# bfc.net
KiCad netlist of a schematic drawn in EAGLE
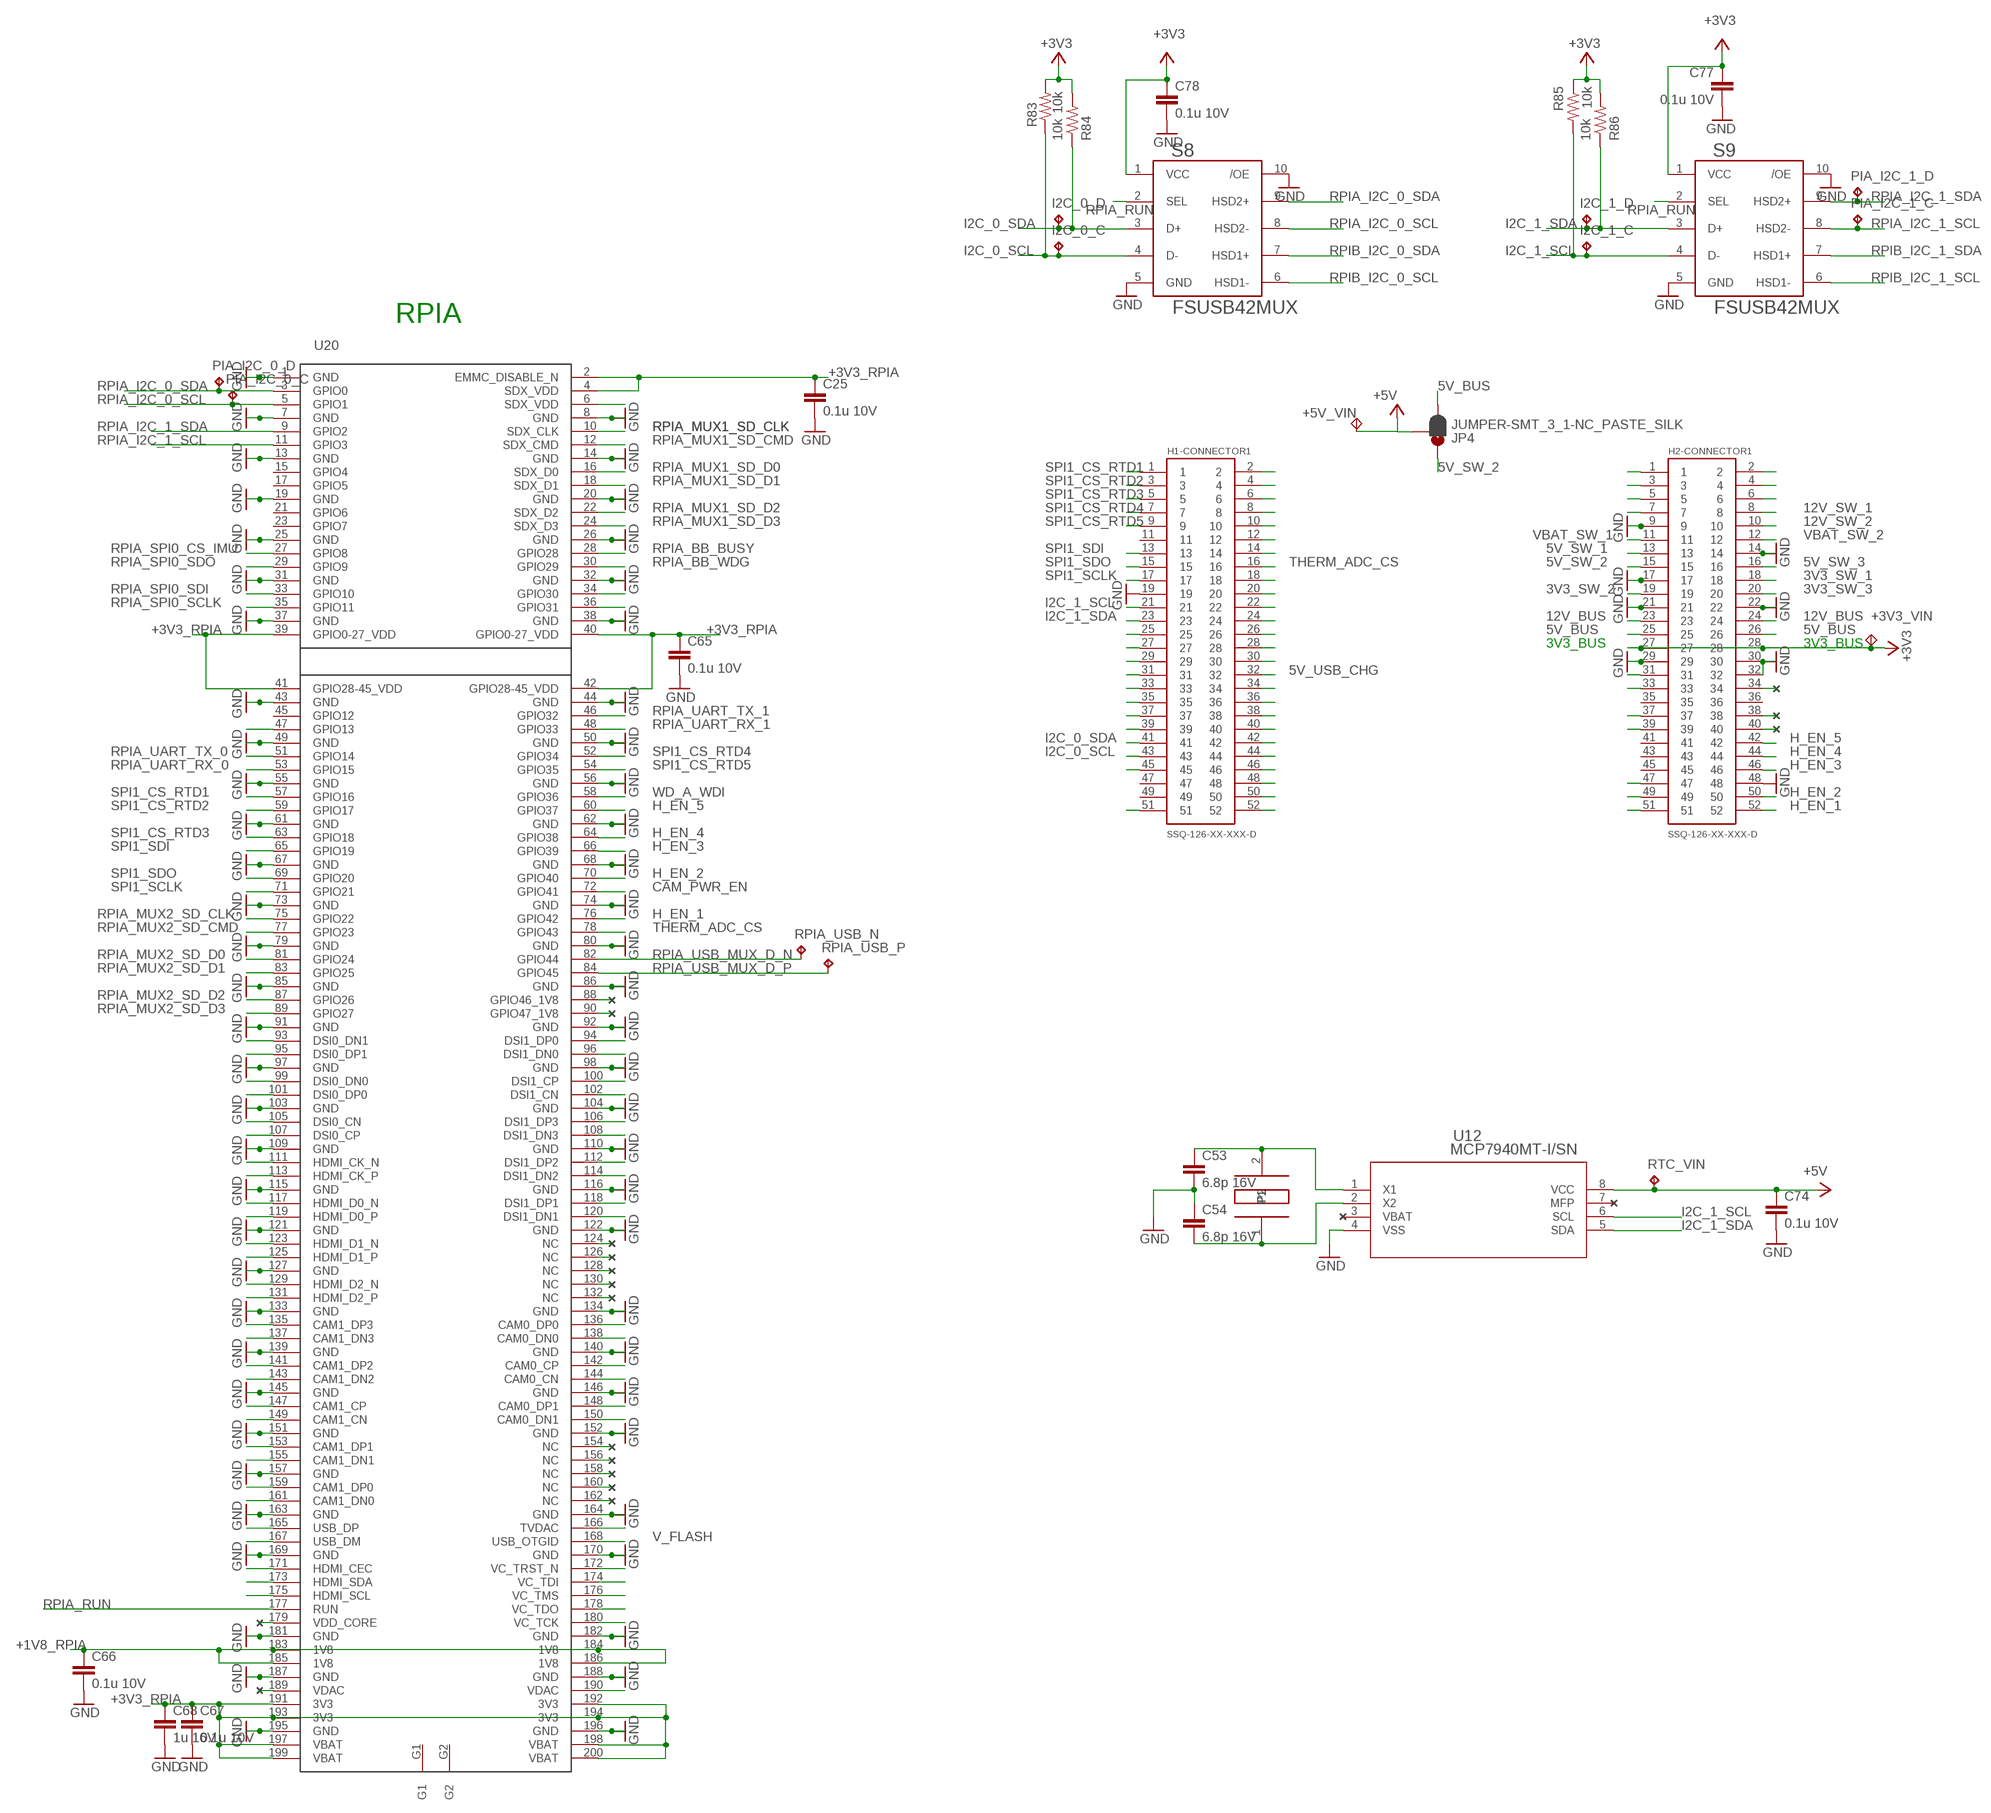
[diagram p0: schematic, sheet 1, part 1 of 2]
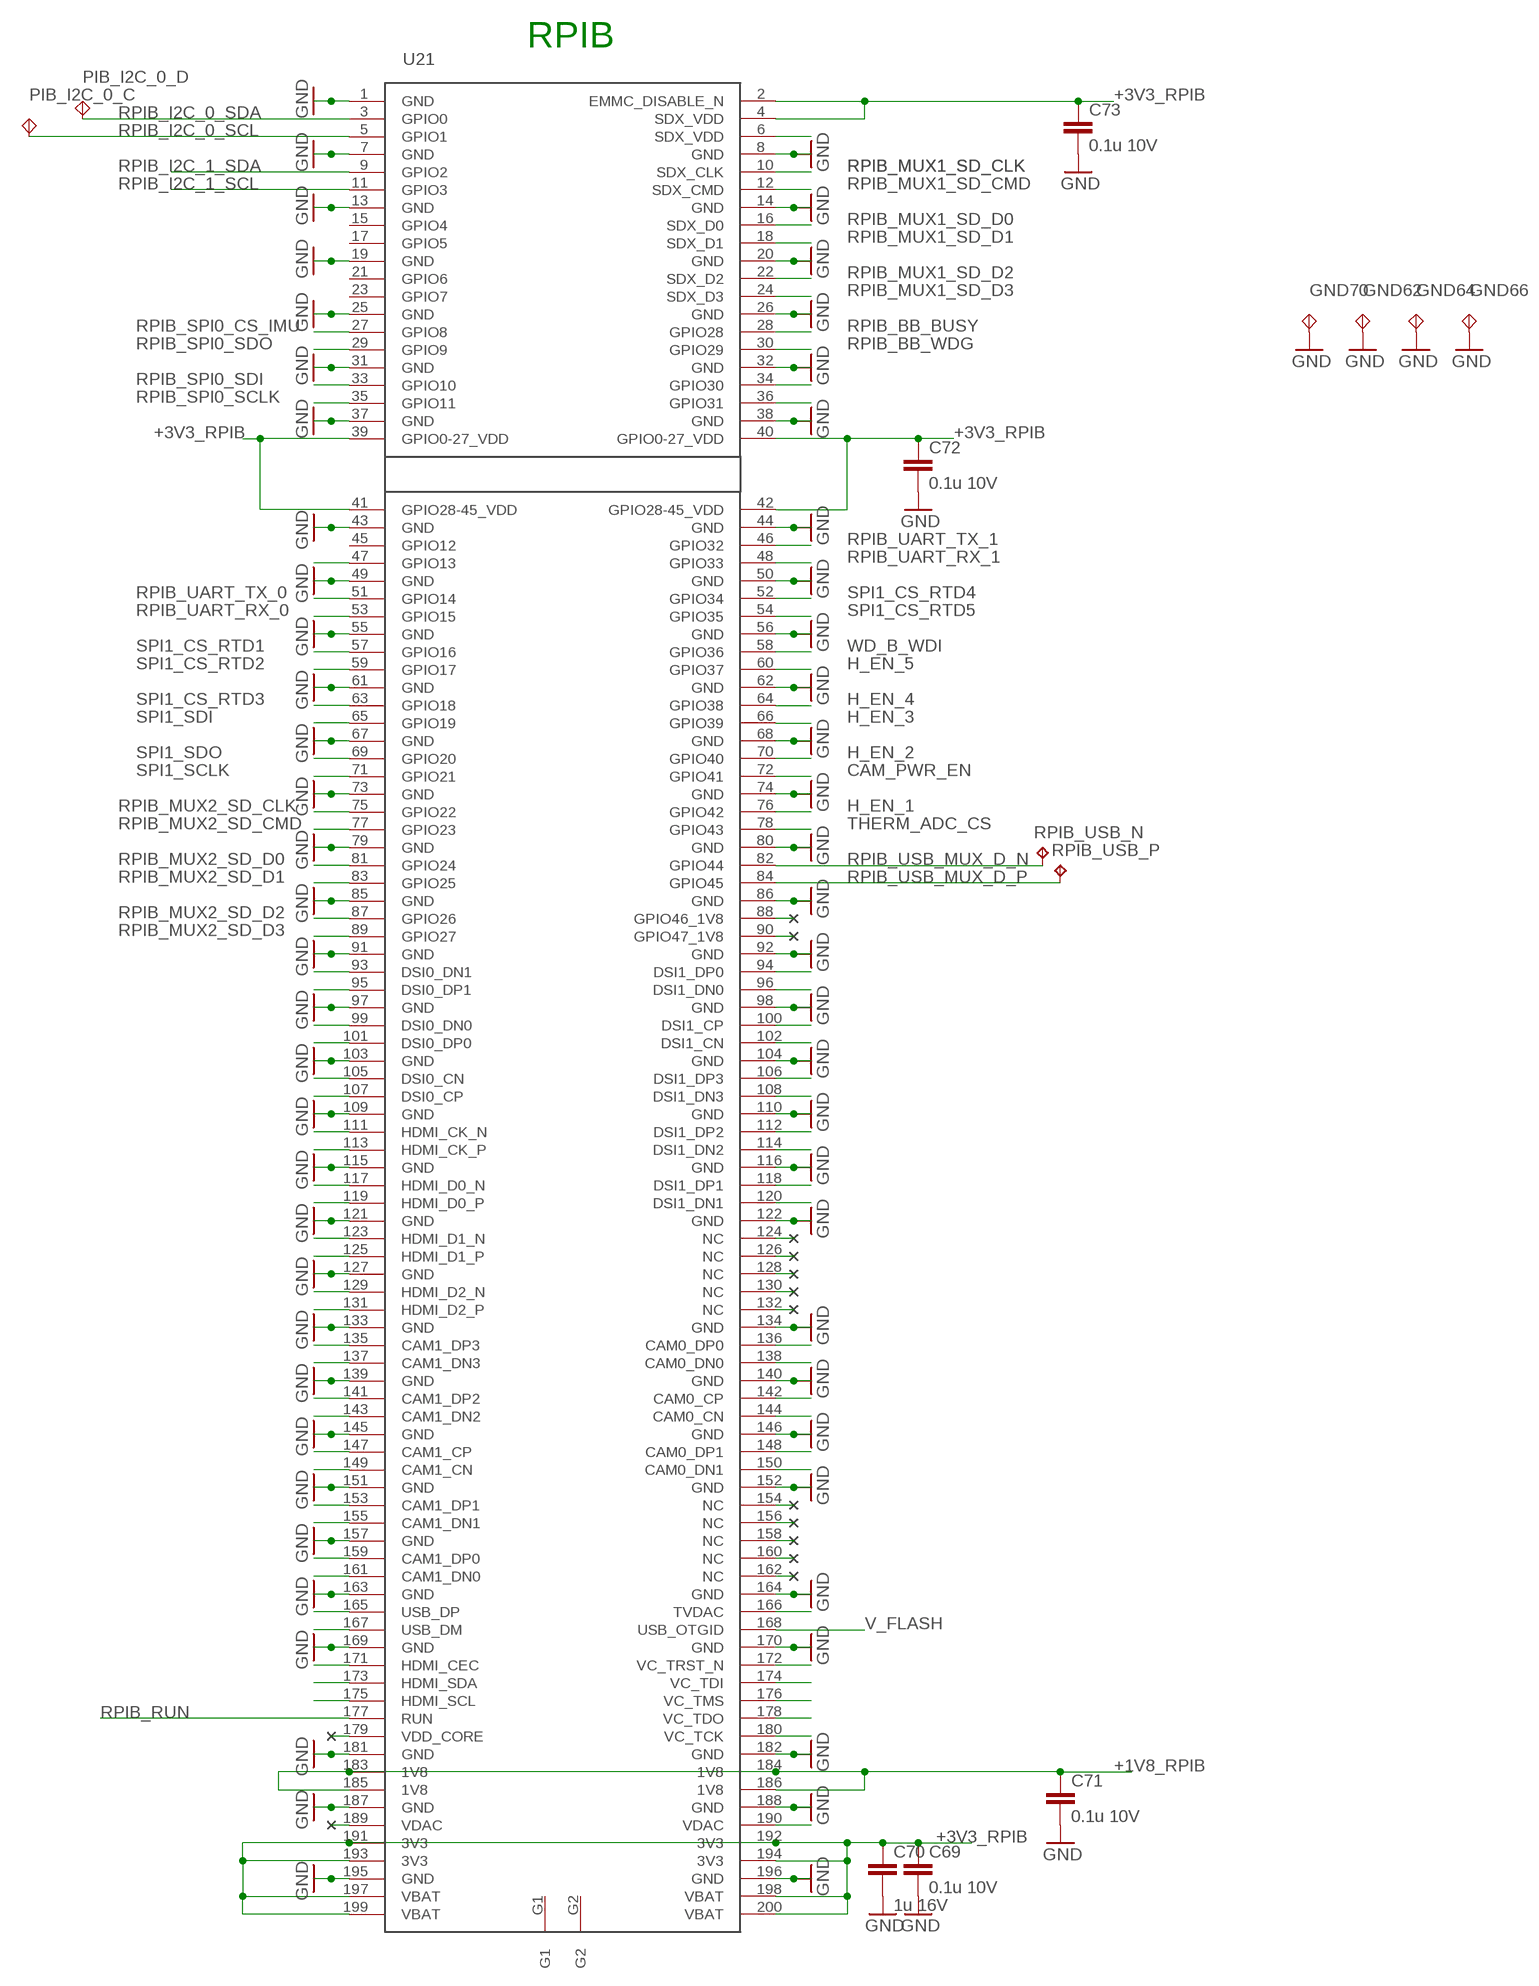
[diagram p1: schematic, sheet 1, part 2 of 2]
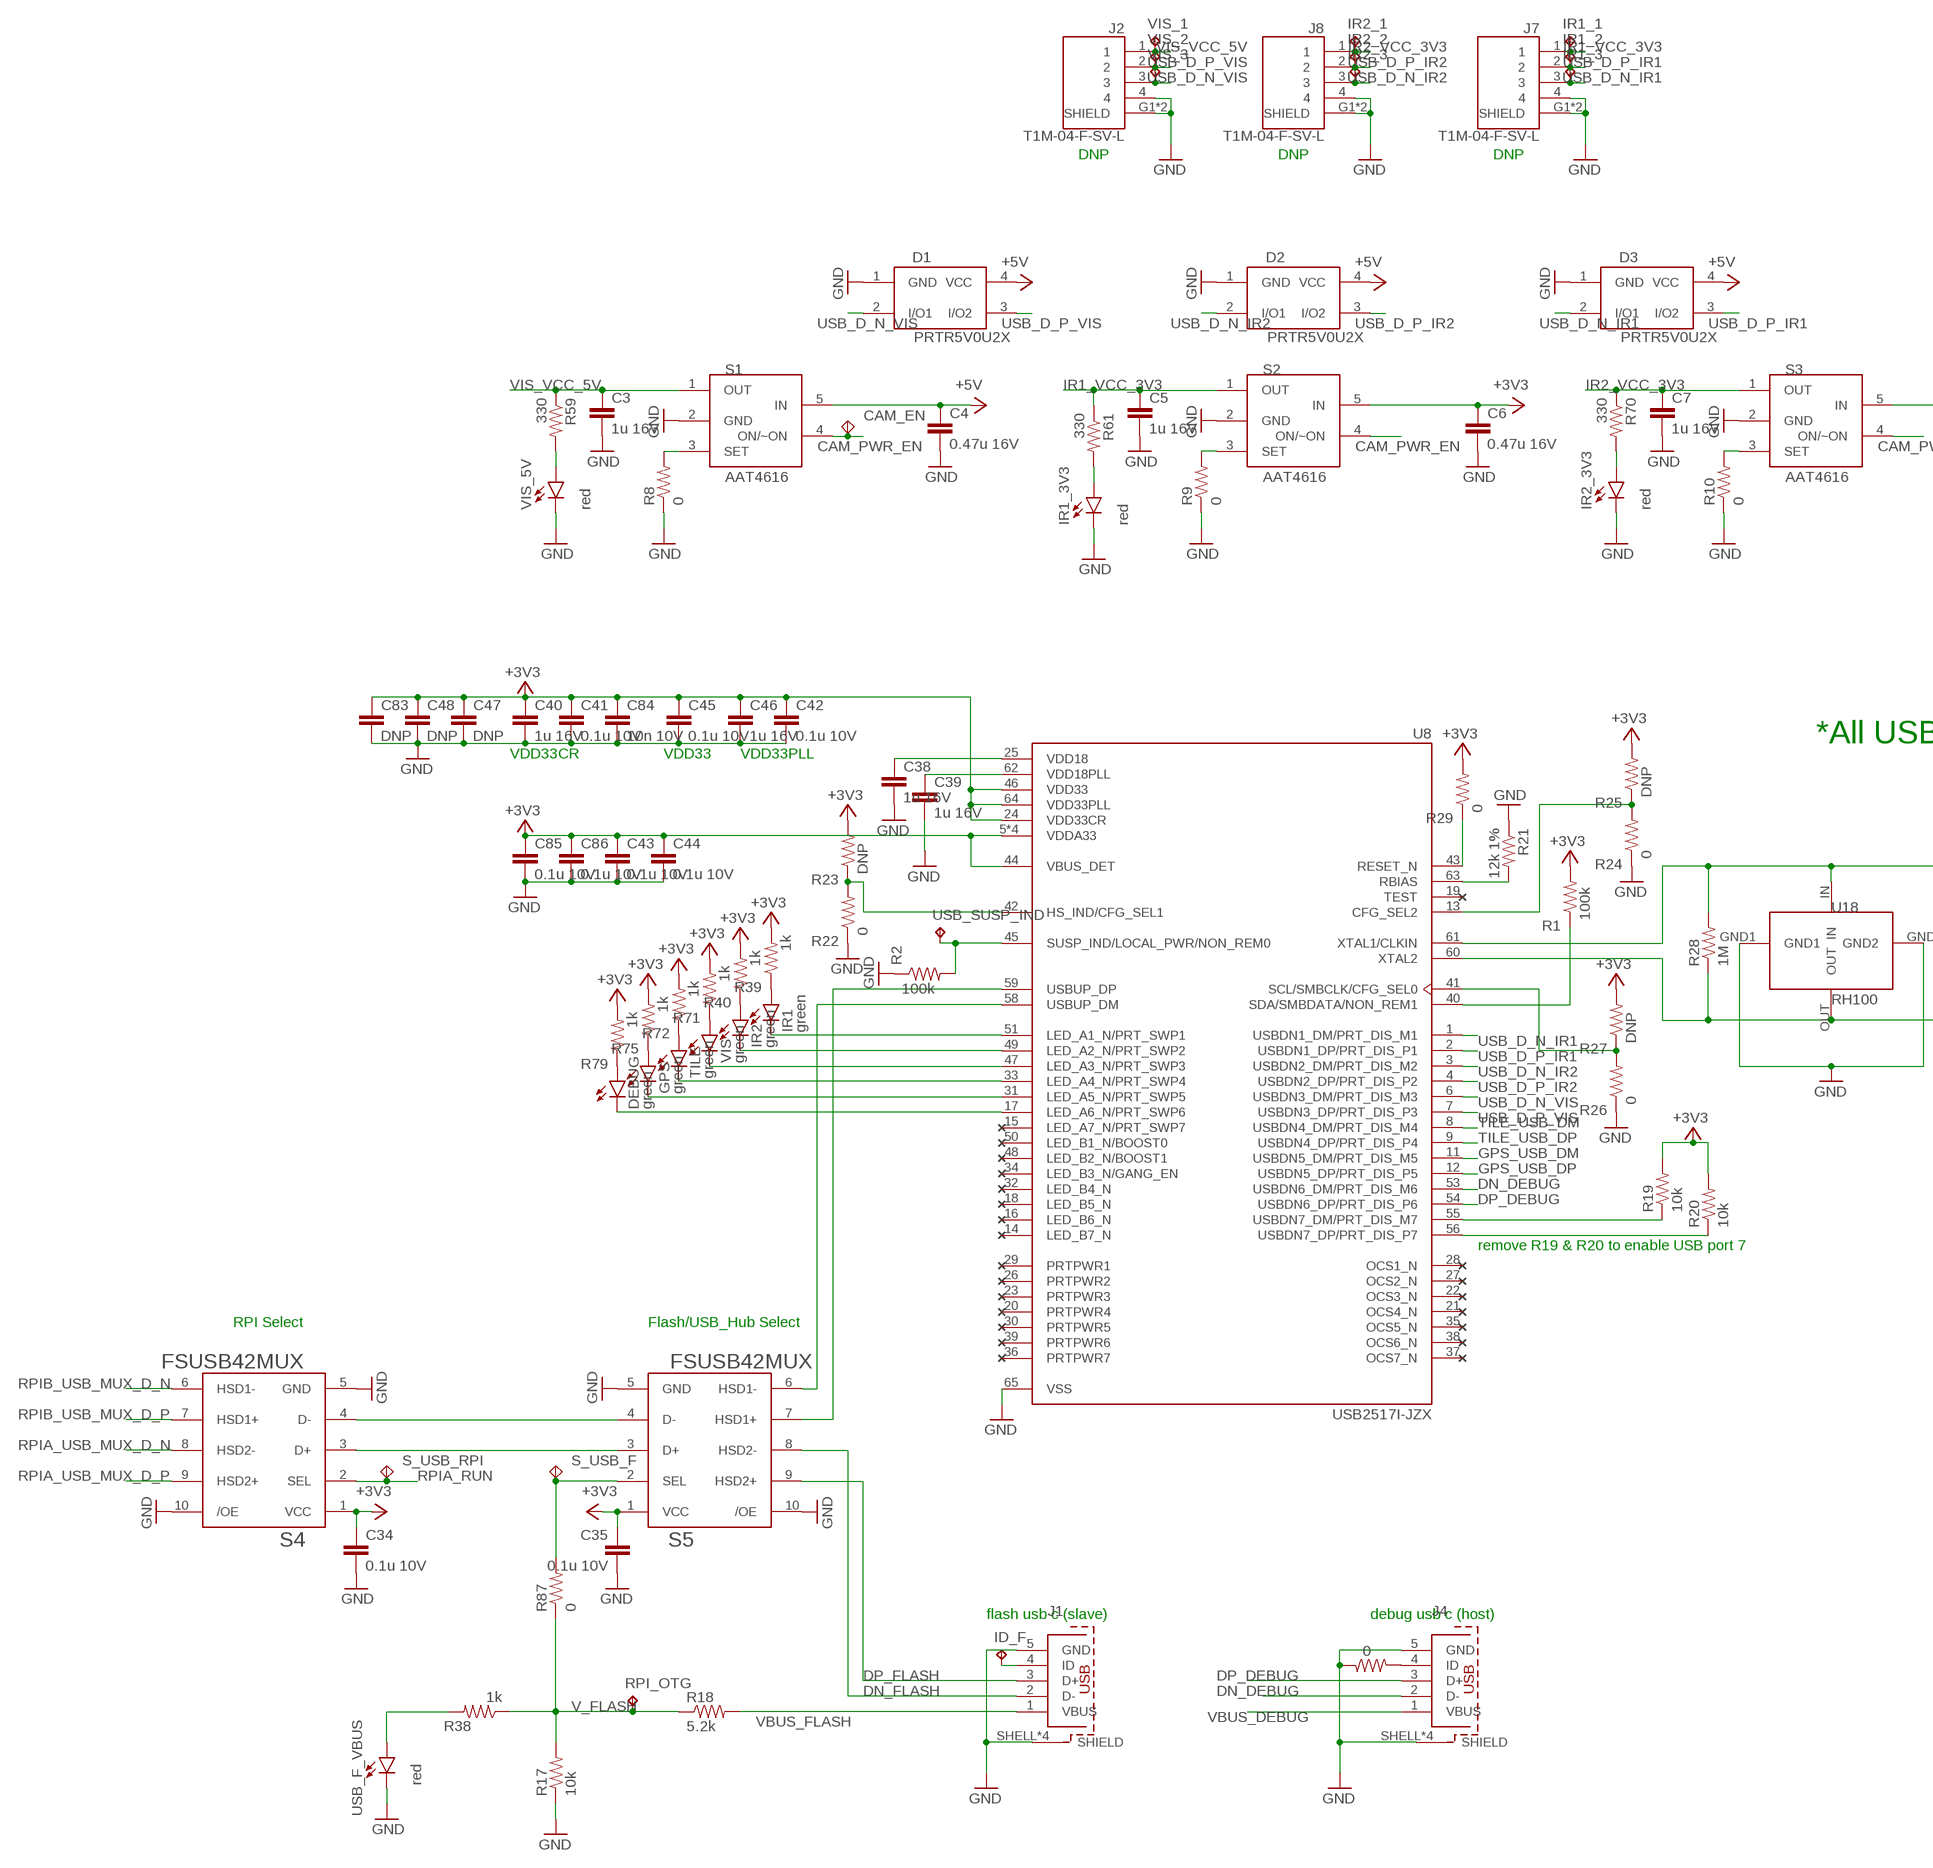
[diagram p2: schematic, sheet 2, part 1 of 2]
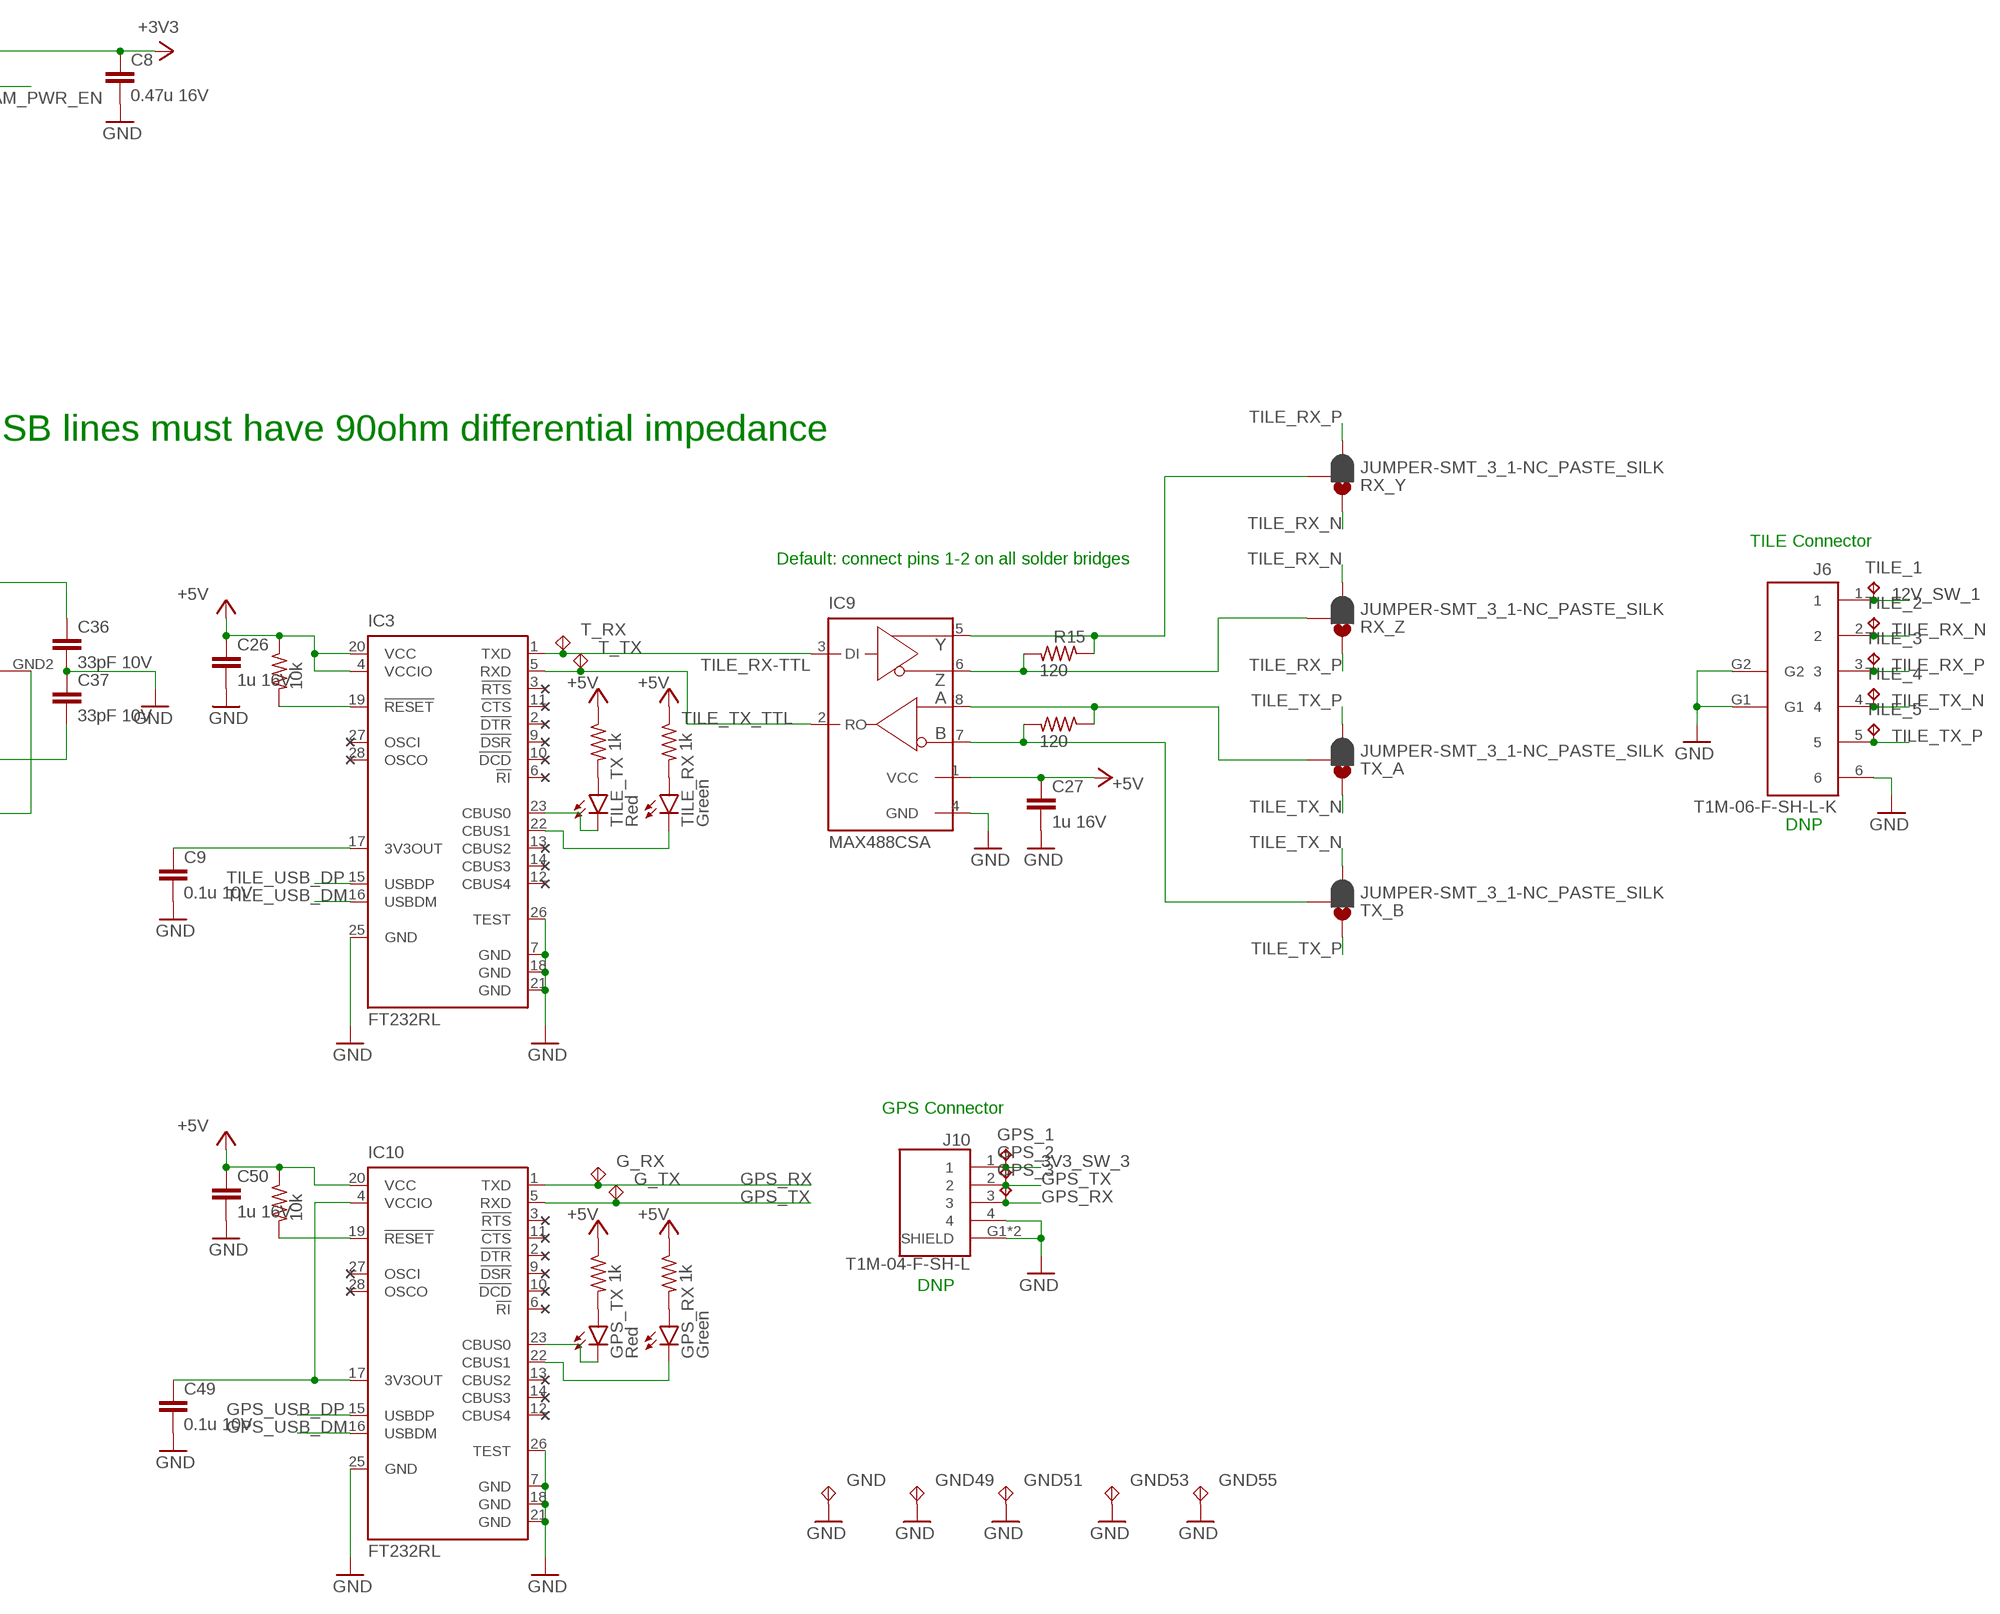
[diagram p3: schematic, sheet 2, part 2 of 2]
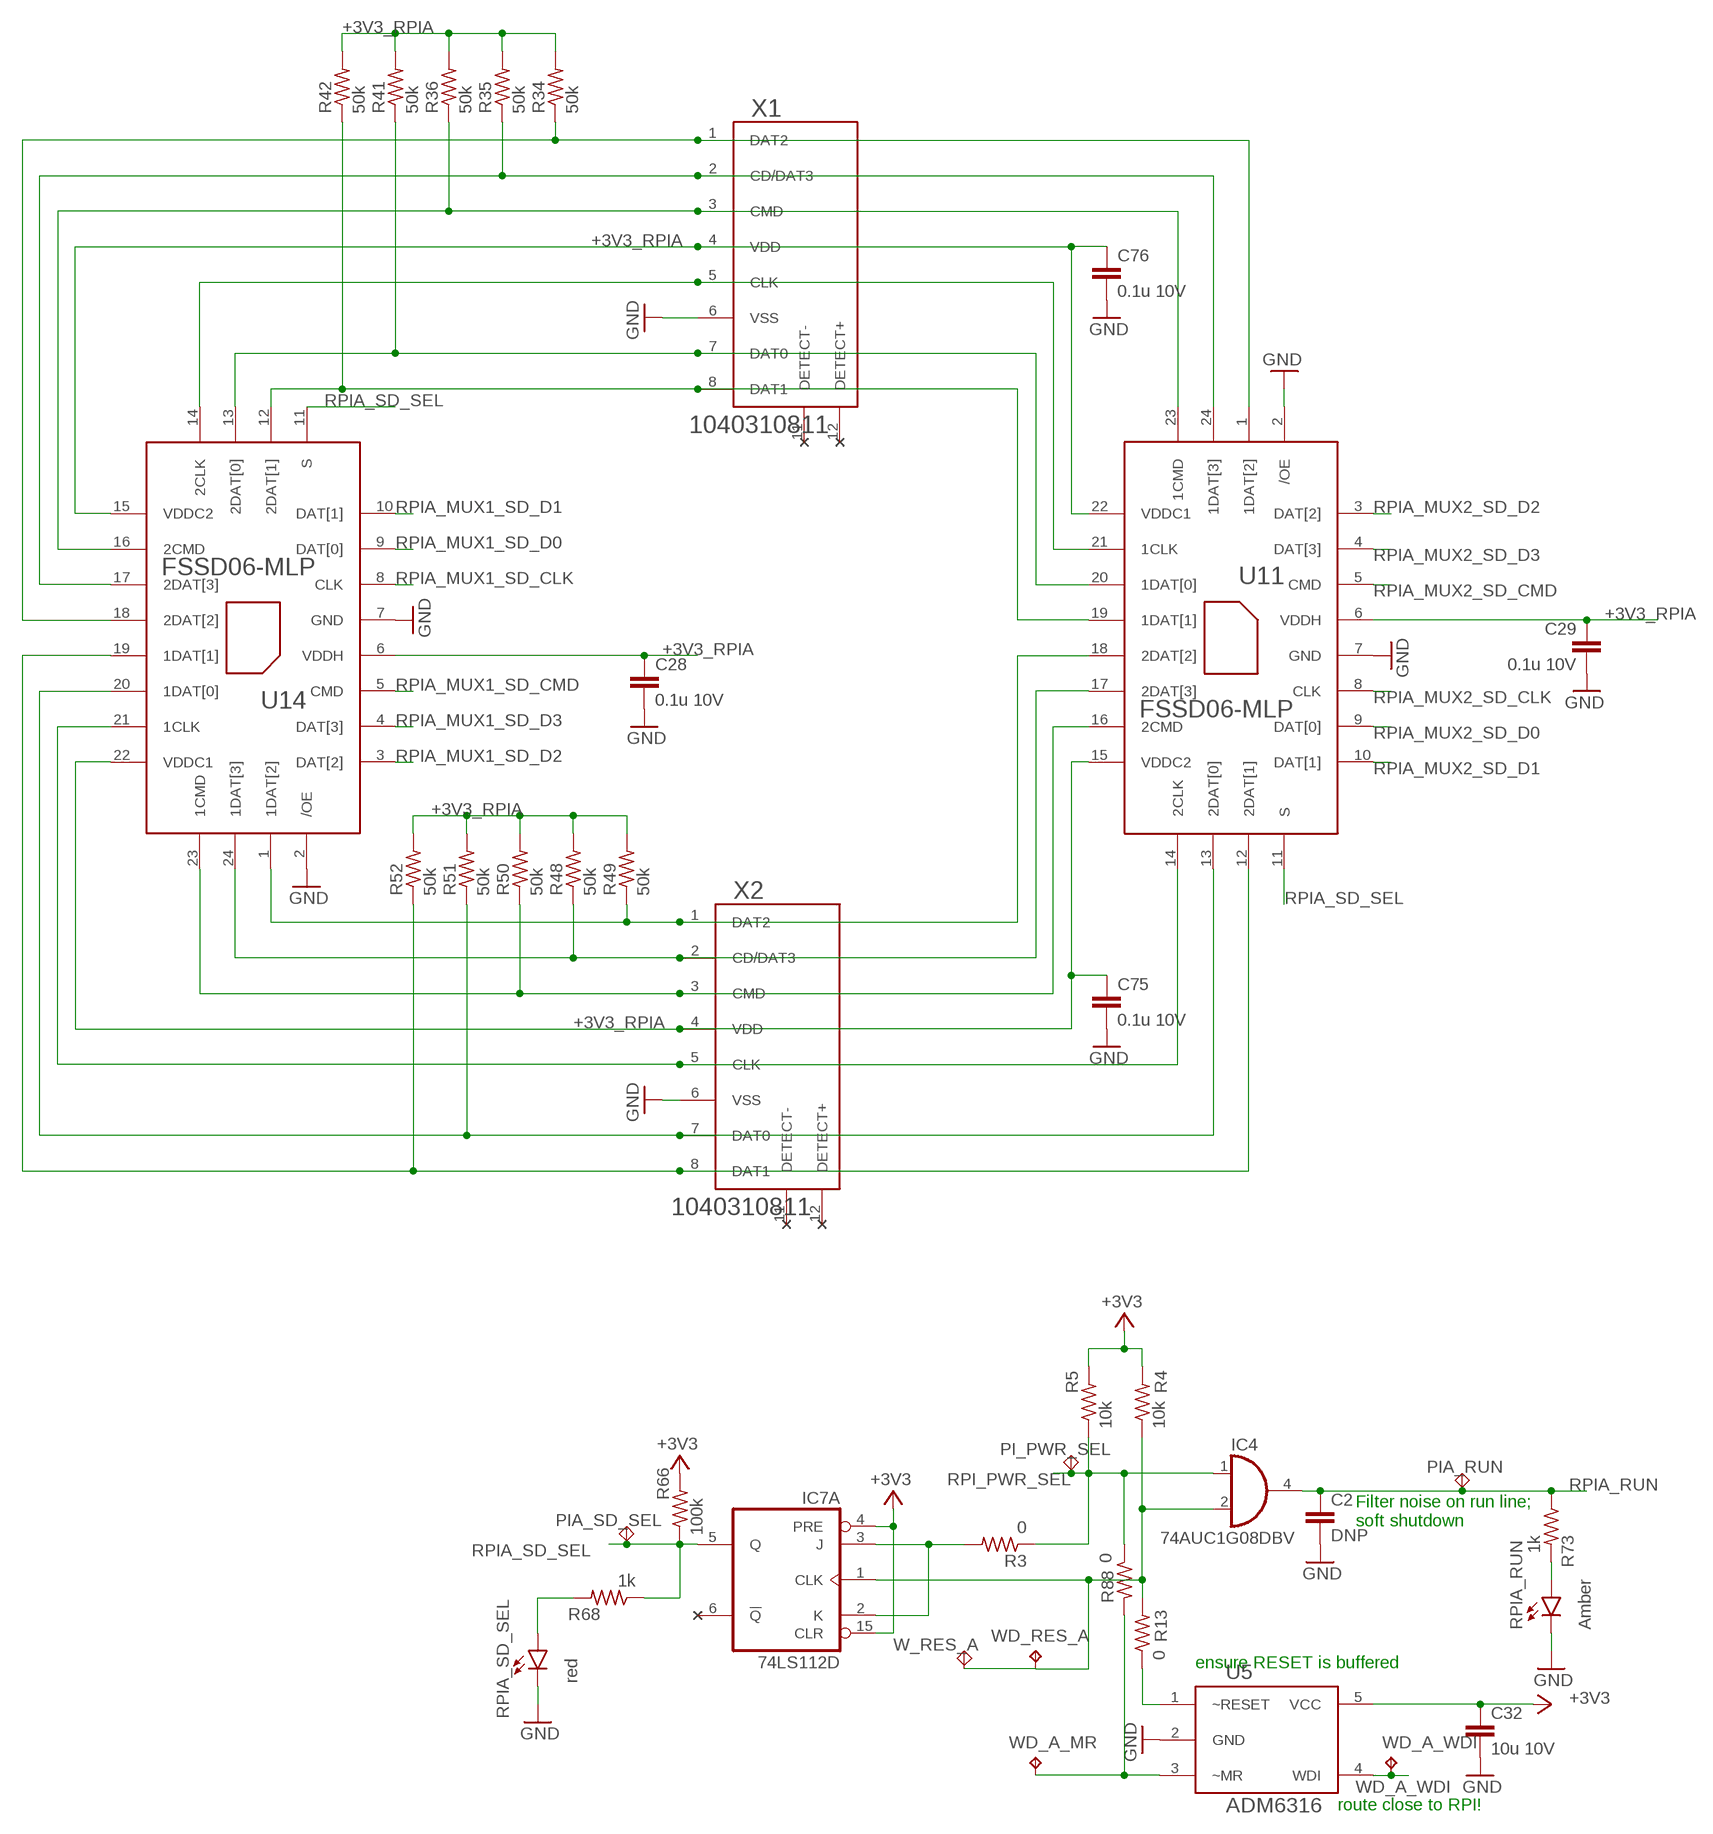
[diagram p4: schematic, sheet 3, part 1 of 2]
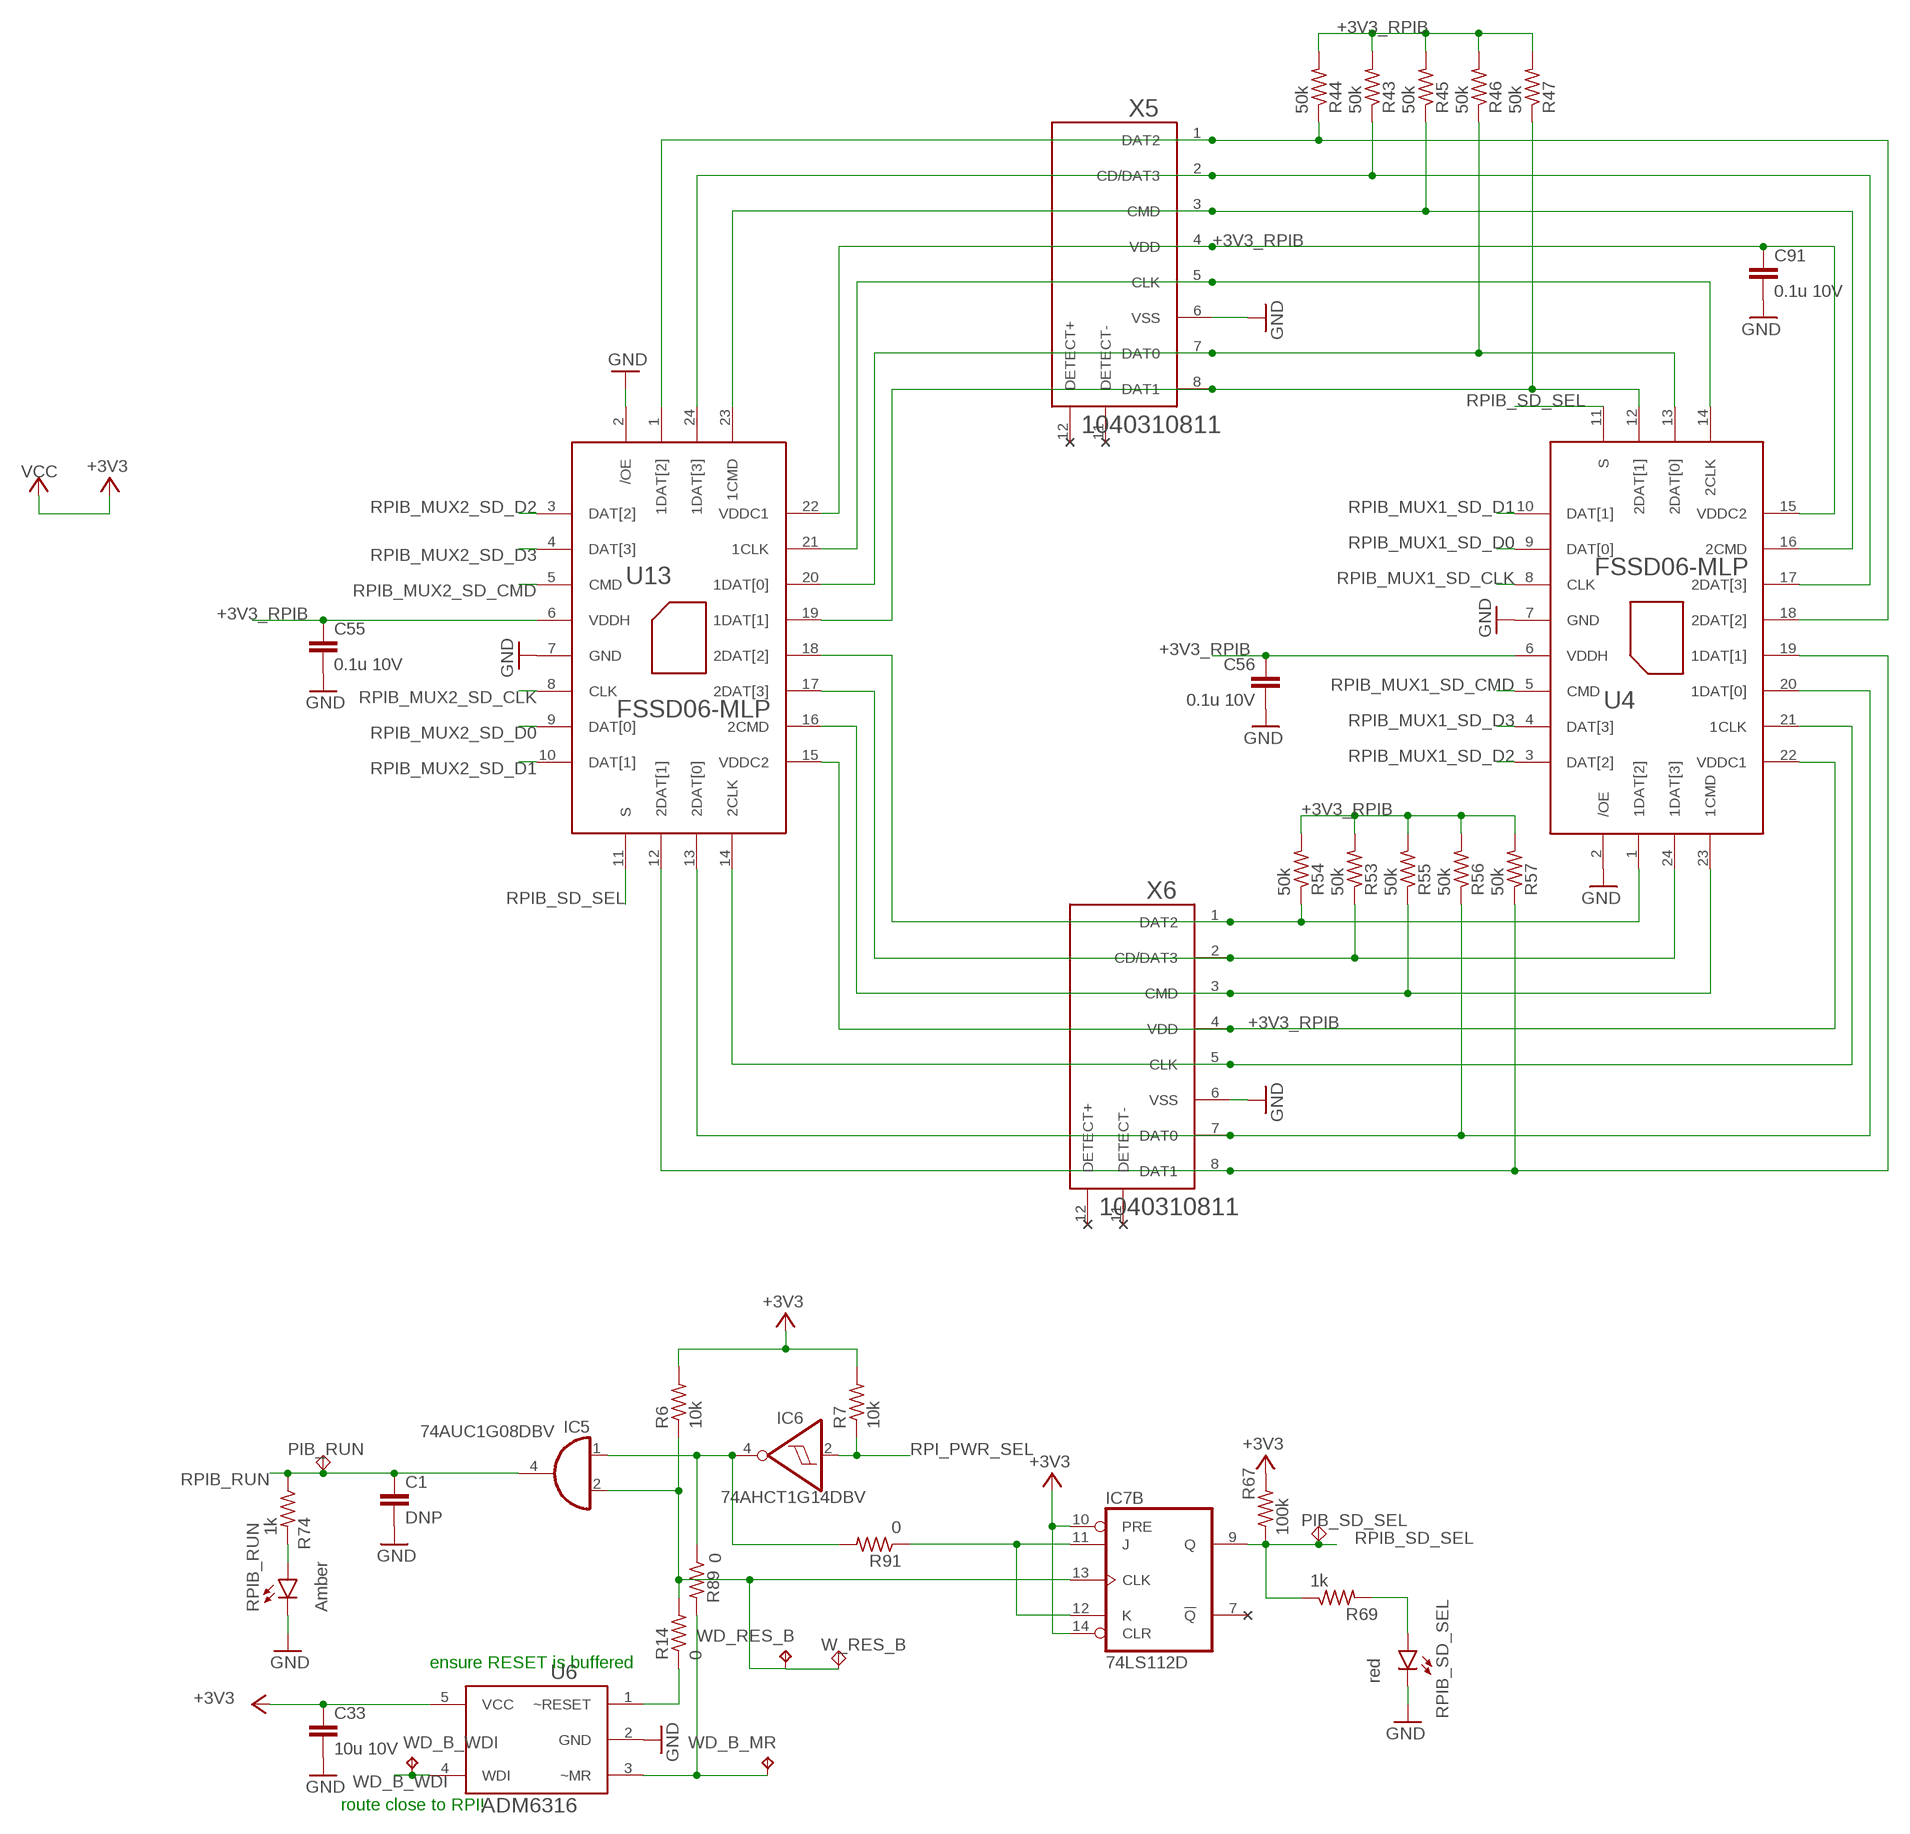
[diagram p5: schematic, sheet 3, part 2 of 2]
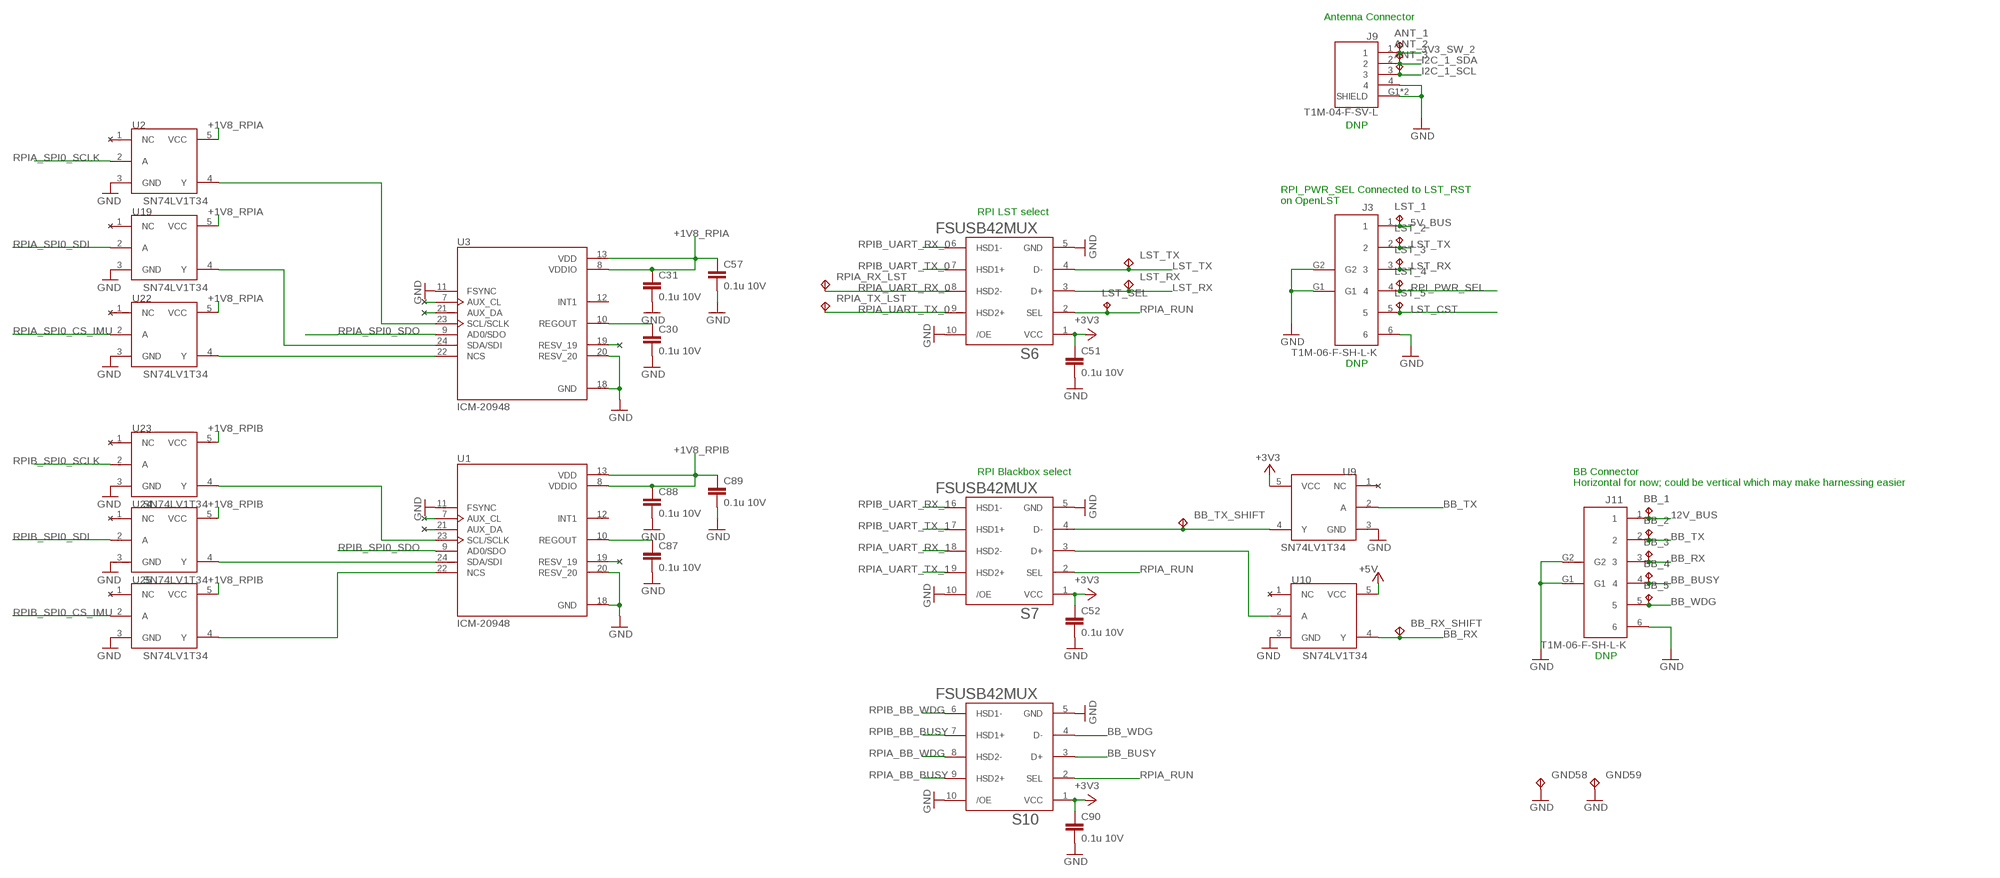
[diagram p6: schematic, sheet 4]
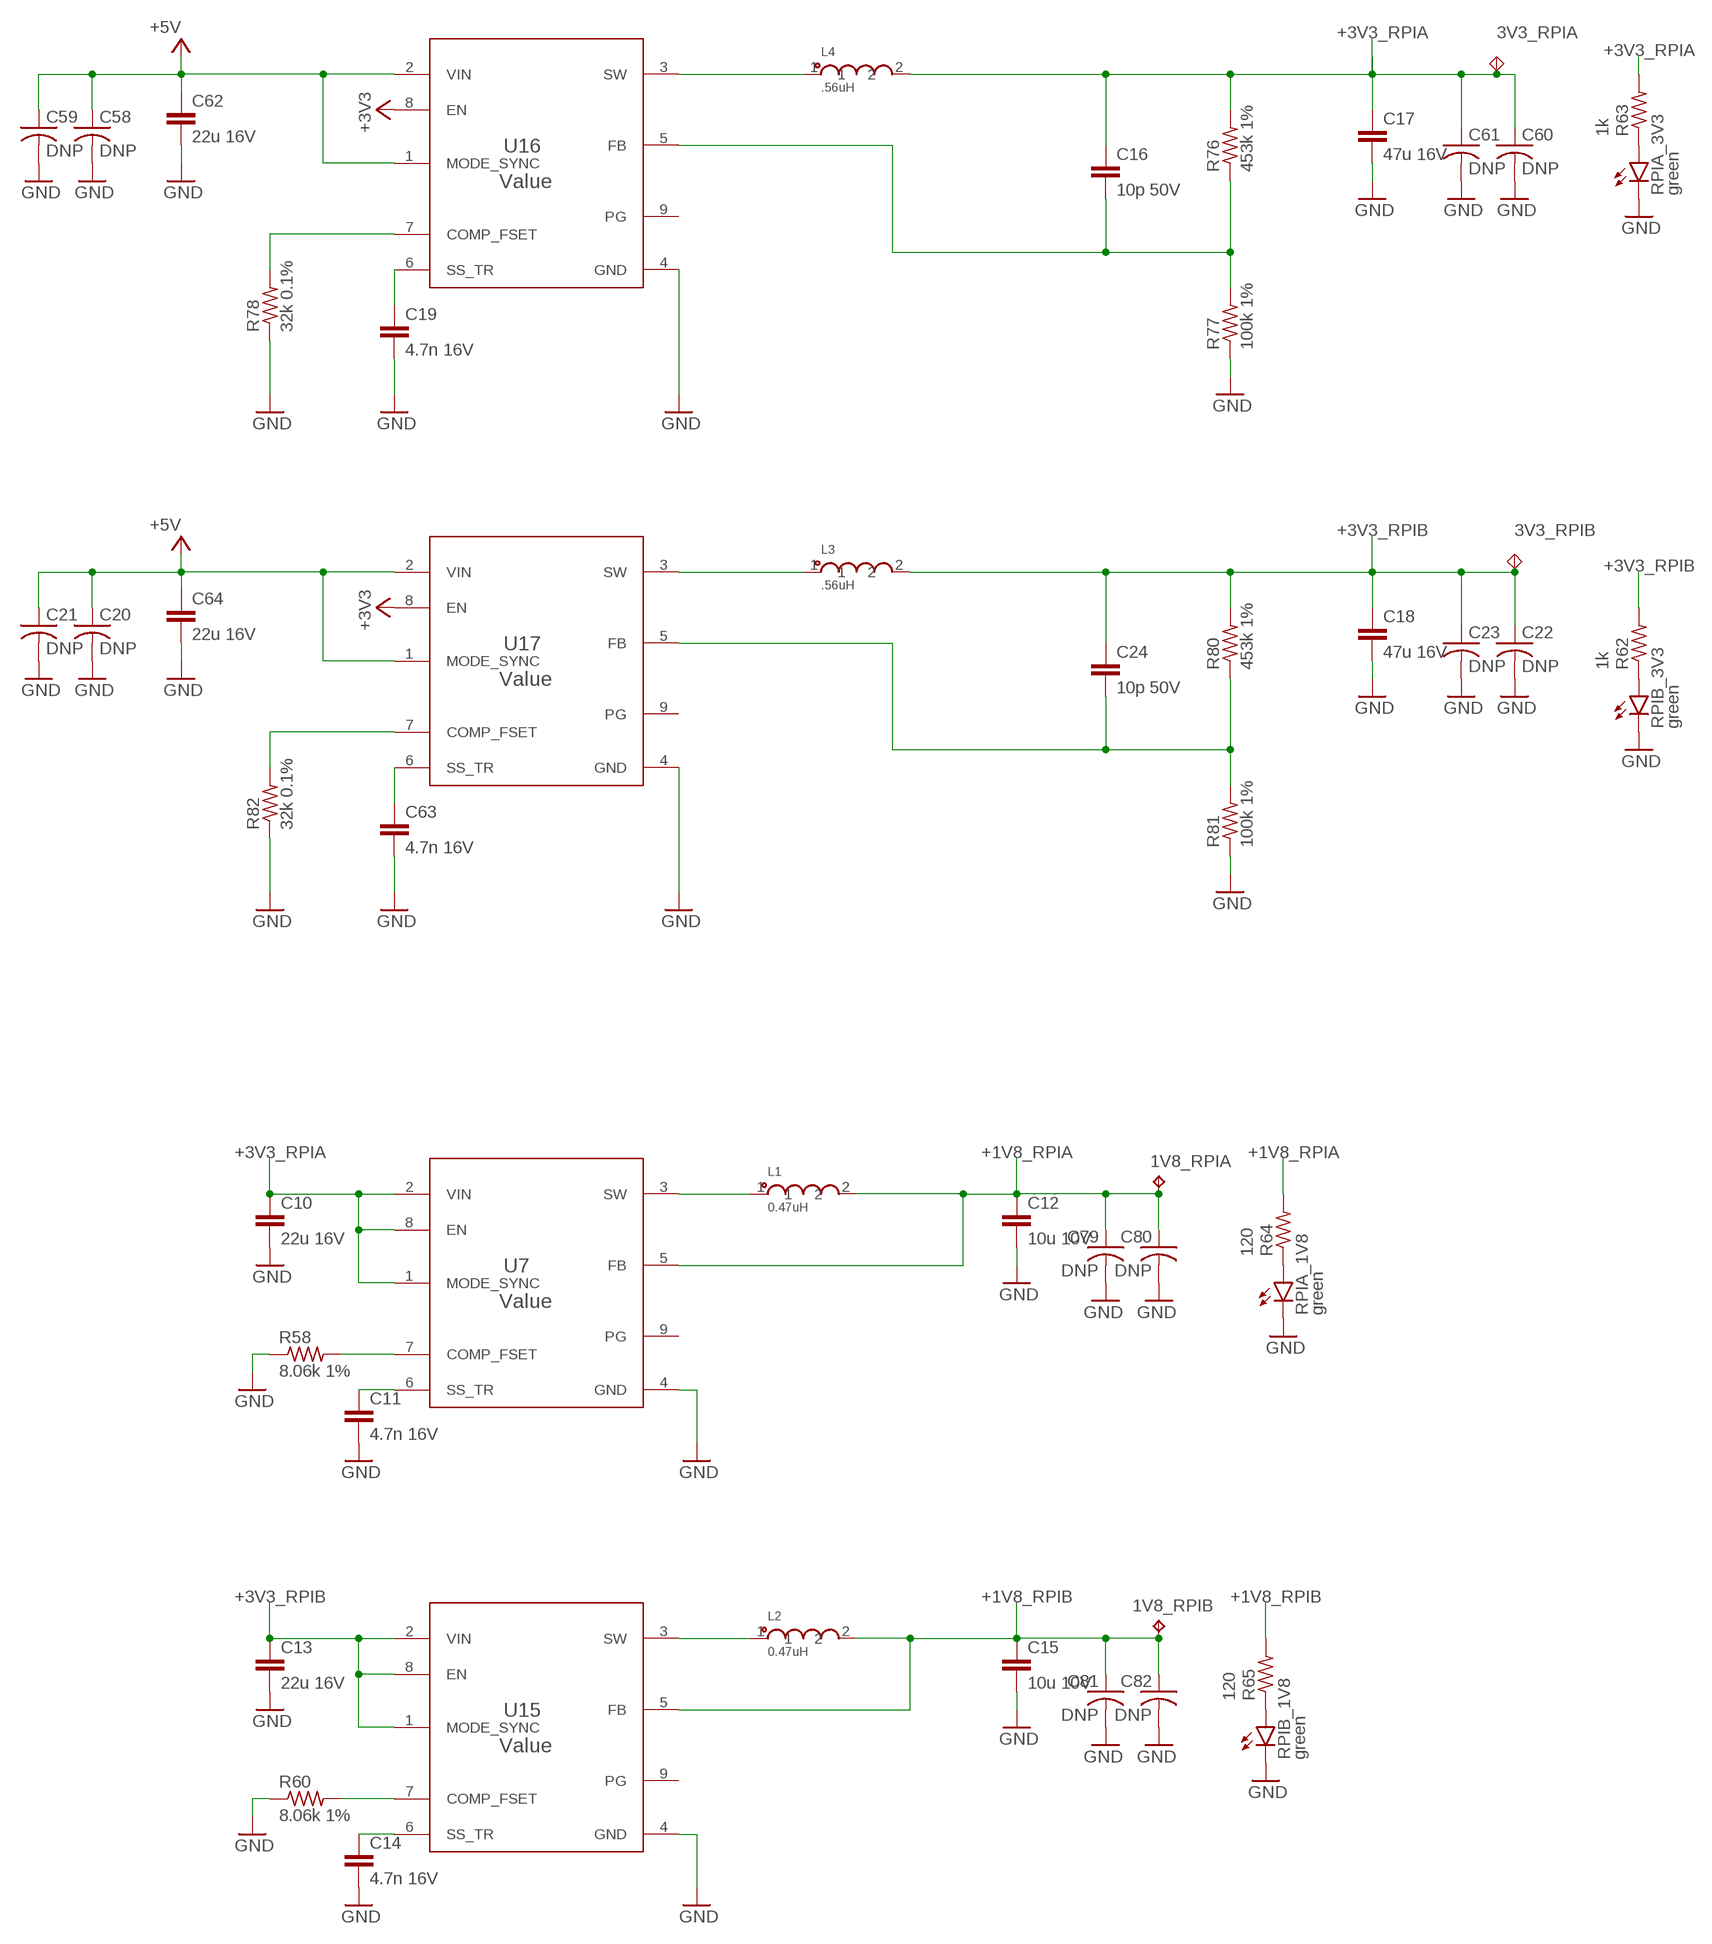
[diagram p7: schematic, sheet 5]

(export (version "E")
  (design (tool "Eeschema 10.0.6"))
  (components
    (comp (ref "C3")
      (value "1u 16V")
      (footprint "eagle-import:C0603")
      (libsource (lib "eagle-import") (part "C-EUC0603"))
    )
    (comp (ref "C4")
      (value "0.47u 16V")
      (footprint "eagle-import:C0603")
      (libsource (lib "eagle-import") (part "C-EUC0603"))
    )
    (comp (ref "C5")
      (value "1u 16V")
      (footprint "eagle-import:C0603")
      (libsource (lib "eagle-import") (part "C-EUC0603"))
    )
    (comp (ref "C6")
      (value "0.47u 16V")
      (footprint "eagle-import:C0603")
      (libsource (lib "eagle-import") (part "C-EUC0603"))
    )
    (comp (ref "C7")
      (value "1u 16V")
      (footprint "eagle-import:C0603")
      (libsource (lib "eagle-import") (part "C-EUC0603"))
    )
    (comp (ref "C8")
      (value "0.47u 16V")
      (footprint "eagle-import:C0603")
      (libsource (lib "eagle-import") (part "C-EUC0603"))
    )
    (comp (ref "C9")
      (value "0.1u 10V")
      (footprint "eagle-import:C0603")
      (libsource (lib "eagle-import") (part "C-EUC0603"))
    )
    (comp (ref "C26")
      (value "1u 16V")
      (footprint "eagle-import:C0603")
      (libsource (lib "eagle-import") (part "C-EUC0603"))
    )
    (comp (ref "C27")
      (value "1u 16V")
      (footprint "eagle-import:C0603")
      (libsource (lib "eagle-import") (part "C-EUC0603"))
    )
    (comp (ref "C34")
      (value "0.1u 10V")
      (footprint "eagle-import:C0603")
      (libsource (lib "eagle-import") (part "C-EUC0603"))
    )
    (comp (ref "C35")
      (value "0.1u 10V")
      (footprint "eagle-import:C0603")
      (libsource (lib "eagle-import") (part "C-EUC0603"))
    )
    (comp (ref "C36")
      (value "33pF 10V")
      (footprint "eagle-import:C0603")
      (libsource (lib "eagle-import") (part "C-EUC0603"))
    )
    (comp (ref "C37")
      (value "33pF 10V")
      (footprint "eagle-import:C0603")
      (libsource (lib "eagle-import") (part "C-EUC0603"))
    )
    (comp (ref "C38")
      (value "1u 16V")
      (footprint "eagle-import:C0603")
      (libsource (lib "eagle-import") (part "C-EUC0603"))
    )
    (comp (ref "C39")
      (value "1u 16V")
      (footprint "eagle-import:C0603")
      (libsource (lib "eagle-import") (part "C-EUC0603"))
    )
    (comp (ref "C40")
      (value "1u 16V")
      (footprint "eagle-import:C0603")
      (libsource (lib "eagle-import") (part "C-EUC0603"))
    )
    (comp (ref "C41")
      (value "0.1u 10V")
      (footprint "eagle-import:C0603")
      (libsource (lib "eagle-import") (part "C-EUC0603"))
    )
    (comp (ref "C42")
      (value "0.1u 10V")
      (footprint "eagle-import:C0603")
      (libsource (lib "eagle-import") (part "C-EUC0603"))
    )
    (comp (ref "C43")
      (value "0.1u 10V")
      (footprint "eagle-import:C0603")
      (libsource (lib "eagle-import") (part "C-EUC0603"))
    )
    (comp (ref "C44")
      (value "0.1u 10V")
      (footprint "eagle-import:C0603")
      (libsource (lib "eagle-import") (part "C-EUC0603"))
    )
    (comp (ref "C45")
      (value "0.1u 10V")
      (footprint "eagle-import:C0603")
      (libsource (lib "eagle-import") (part "C-EUC0603"))
    )
    (comp (ref "C46")
      (value "1u 16V")
      (footprint "eagle-import:C0603")
      (libsource (lib "eagle-import") (part "C-EUC0603"))
    )
    (comp (ref "C47")
      (value "DNP")
      (footprint "eagle-import:C0603")
      (libsource (lib "eagle-import") (part "C-EUC0603"))
    )
    (comp (ref "C48")
      (value "DNP")
      (footprint "eagle-import:C0603")
      (libsource (lib "eagle-import") (part "C-EUC0603"))
    )
    (comp (ref "C49")
      (value "0.1u 10V")
      (footprint "eagle-import:C0603")
      (libsource (lib "eagle-import") (part "C-EUC0603"))
    )
    (comp (ref "C50")
      (value "1u 16V")
      (footprint "eagle-import:C0603")
      (libsource (lib "eagle-import") (part "C-EUC0603"))
    )
    (comp (ref "C83")
      (value "DNP")
      (footprint "eagle-import:C0603")
      (libsource (lib "eagle-import") (part "C-EUC0603"))
    )
    (comp (ref "C84")
      (value "10n 10V")
      (footprint "eagle-import:C0603")
      (libsource (lib "eagle-import") (part "C-EUC0603"))
    )
    (comp (ref "C85")
      (value "0.1u 10V")
      (footprint "eagle-import:C0603")
      (libsource (lib "eagle-import") (part "C-EUC0603"))
    )
    (comp (ref "C86")
      (value "0.1u 10V")
      (footprint "eagle-import:C0603")
      (libsource (lib "eagle-import") (part "C-EUC0603"))
    )
    (comp (ref "CAM_EN")
      (value "TP_HRWN")
      (footprint "eagle-import:TP_HRWN")
      (fields (field (name "MPN") "S2751-46R"))
      (libsource (lib "eagle-import") (part "TP_HRWN"))
    )
    (comp (ref "D1")
      (value "PRTR5V0U2X")
      (footprint "eagle-import:PRTR5V0U2X")
      (fields (field (name "MPN") "PRTR5V0U2X,215"))
      (libsource (lib "eagle-import") (part "PRTR5V0U2X"))
    )
    (comp (ref "D2")
      (value "PRTR5V0U2X")
      (footprint "eagle-import:PRTR5V0U2X")
      (fields (field (name "MPN") "PRTR5V0U2X,215"))
      (libsource (lib "eagle-import") (part "PRTR5V0U2X"))
    )
    (comp (ref "D3")
      (value "PRTR5V0U2X")
      (footprint "eagle-import:PRTR5V0U2X")
      (fields (field (name "MPN") "PRTR5V0U2X,215"))
      (libsource (lib "eagle-import") (part "PRTR5V0U2X"))
    )
    (comp (ref "DEBUG")
      (value "green")
      (footprint "eagle-import:SML0603")
      (fields (field (name "MPN") "LG L29K-F2J1-24-Z"))
      (libsource (lib "eagle-import") (part "LEDSML0603"))
    )
    (comp (ref "GND")
      (value "TP_HRWN")
      (footprint "eagle-import:TP_HRWN")
      (fields (field (name "MPN") "S2751-46R"))
      (libsource (lib "eagle-import") (part "TP_HRWN"))
    )
    (comp (ref "GND49")
      (value "TP_HRWN")
      (footprint "eagle-import:TP_HRWN")
      (fields (field (name "MPN") "S2751-46R"))
      (libsource (lib "eagle-import") (part "TP_HRWN"))
    )
    (comp (ref "GND51")
      (value "TP_HRWN")
      (footprint "eagle-import:TP_HRWN")
      (fields (field (name "MPN") "S2751-46R"))
      (libsource (lib "eagle-import") (part "TP_HRWN"))
    )
    (comp (ref "GND53")
      (value "TP_HRWN")
      (footprint "eagle-import:TP_HRWN")
      (fields (field (name "MPN") "S2751-46R"))
      (libsource (lib "eagle-import") (part "TP_HRWN"))
    )
    (comp (ref "GND55")
      (value "TP_HRWN")
      (footprint "eagle-import:TP_HRWN")
      (fields (field (name "MPN") "S2751-46R"))
      (libsource (lib "eagle-import") (part "TP_HRWN"))
    )
    (comp (ref "GPS")
      (value "green")
      (footprint "eagle-import:SML0603")
      (fields (field (name "MPN") "LG L29K-F2J1-24-Z"))
      (libsource (lib "eagle-import") (part "LEDSML0603"))
    )
    (comp (ref "GPS_1")
      (value "TPTP15SQ")
      (footprint "eagle-import:TP15SQ")
      (libsource (lib "eagle-import") (part "TPTP15SQ"))
    )
    (comp (ref "GPS_2")
      (value "TPTP15SQ")
      (footprint "eagle-import:TP15SQ")
      (libsource (lib "eagle-import") (part "TPTP15SQ"))
    )
    (comp (ref "GPS_3")
      (value "TPTP15SQ")
      (footprint "eagle-import:TP15SQ")
      (libsource (lib "eagle-import") (part "TPTP15SQ"))
    )
    (comp (ref "GPS_RX")
      (value "Green")
      (footprint "eagle-import:SML0603")
      (fields (field (name "MPN") "150060VS75000"))
      (libsource (lib "eagle-import") (part "LEDSML0603"))
    )
    (comp (ref "GPS_TX")
      (value "Red")
      (footprint "eagle-import:SML0603")
      (fields (field (name "MPN") "LTST-C190CKT"))
      (libsource (lib "eagle-import") (part "LEDSML0603"))
    )
    (comp (ref "G_RX")
      (value "TP_HRWN")
      (footprint "eagle-import:TP_HRWN")
      (fields (field (name "MPN") "S2751-46R"))
      (libsource (lib "eagle-import") (part "TP_HRWN"))
    )
    (comp (ref "G_TX")
      (value "TP_HRWN")
      (footprint "eagle-import:TP_HRWN")
      (fields (field (name "MPN") "S2751-46R"))
      (libsource (lib "eagle-import") (part "TP_HRWN"))
    )
    (comp (ref "IC3")
      (value "FT232RL")
      (footprint "eagle-import:SSOP28")
      (libsource (lib "eagle-import") (part "FT232RL"))
    )
    (comp (ref "IC9")
      (value "MAX488CSA")
      (footprint "eagle-import:SO08")
      (fields (field (name "MF") "MAXIM") (field (name "MPN") "MAX488ESA+"))
      (libsource (lib "eagle-import") (part "MAX488CSA"))
    )
    (comp (ref "IC10")
      (value "FT232RL")
      (footprint "eagle-import:SSOP28")
      (libsource (lib "eagle-import") (part "FT232RL"))
    )
    (comp (ref "ID_F")
      (value "TPTP18SQ")
      (footprint "eagle-import:TP18SQ")
      (libsource (lib "eagle-import") (part "TPTP18SQ"))
    )
    (comp (ref "IR1")
      (value "green")
      (footprint "eagle-import:SML0603")
      (fields (field (name "MPN") "LG L29K-F2J1-24-Z"))
      (libsource (lib "eagle-import") (part "LEDSML0603"))
    )
    (comp (ref "IR1_1")
      (value "TPTP15SQ")
      (footprint "eagle-import:TP15SQ")
      (libsource (lib "eagle-import") (part "TPTP15SQ"))
    )
    (comp (ref "IR1_2")
      (value "TPTP15SQ")
      (footprint "eagle-import:TP15SQ")
      (libsource (lib "eagle-import") (part "TPTP15SQ"))
    )
    (comp (ref "IR1_3")
      (value "TPTP15SQ")
      (footprint "eagle-import:TP15SQ")
      (libsource (lib "eagle-import") (part "TPTP15SQ"))
    )
    (comp (ref "IR1_3V3")
      (value "red")
      (footprint "eagle-import:SML0603")
      (fields (field (name "MPN") "LTST-C190CKT"))
      (libsource (lib "eagle-import") (part "LEDSML0603"))
    )
    (comp (ref "IR2")
      (value "green")
      (footprint "eagle-import:SML0603")
      (fields (field (name "MPN") "LG L29K-F2J1-24-Z"))
      (libsource (lib "eagle-import") (part "LEDSML0603"))
    )
    (comp (ref "IR2_1")
      (value "TPTP15SQ")
      (footprint "eagle-import:TP15SQ")
      (libsource (lib "eagle-import") (part "TPTP15SQ"))
    )
    (comp (ref "IR2_2")
      (value "TPTP15SQ")
      (footprint "eagle-import:TP15SQ")
      (libsource (lib "eagle-import") (part "TPTP15SQ"))
    )
    (comp (ref "IR2_3")
      (value "TPTP15SQ")
      (footprint "eagle-import:TP15SQ")
      (libsource (lib "eagle-import") (part "TPTP15SQ"))
    )
    (comp (ref "IR2_3V3")
      (value "red")
      (footprint "eagle-import:SML0603")
      (fields (field (name "MPN") "LTST-C190CKT"))
      (libsource (lib "eagle-import") (part "LEDSML0603"))
    )
    (comp (ref "J1")
      (value "629105150521")
      (footprint "eagle-import:629105150521")
      (libsource (lib "eagle-import") (part "629105150521"))
    )
    (comp (ref "J2")
      (value "T1M-04-F-SV-L")
      (footprint "eagle-import:SAMTEC_T1M-04-F-SV-L")
      (fields (field (name "MF") "Samtec Inc."))
      (libsource (lib "eagle-import") (part "T1M-04-F-SV-L"))
    )
    (comp (ref "J4")
      (value "629105150521")
      (footprint "eagle-import:629105150521")
      (libsource (lib "eagle-import") (part "629105150521"))
    )
    (comp (ref "J6")
      (value "T1M-06-F-SH-L-K")
      (footprint "eagle-import:T1M-06-F-SH-L-K")
      (fields (field (name "MPN") "T1M-06-F-SH-L"))
      (libsource (lib "eagle-import") (part "T1M-06-F-SH-L-K"))
    )
    (comp (ref "J7")
      (value "T1M-04-F-SV-L")
      (footprint "eagle-import:SAMTEC_T1M-04-F-SV-L")
      (fields (field (name "MF") "Samtec Inc."))
      (libsource (lib "eagle-import") (part "T1M-04-F-SV-L"))
    )
    (comp (ref "J8")
      (value "T1M-04-F-SV-L")
      (footprint "eagle-import:SAMTEC_T1M-04-F-SV-L")
      (fields (field (name "MF") "Samtec Inc."))
      (libsource (lib "eagle-import") (part "T1M-04-F-SV-L"))
    )
    (comp (ref "J10")
      (value "T1M-04-F-SH-L")
      (footprint "eagle-import:SAMTEC_T1M-04-F-SH-L")
      (libsource (lib "eagle-import") (part "T1M-04-F-SH-L"))
    )
    (comp (ref "R1")
      (value "100k")
      (footprint "eagle-import:R0603")
      (libsource (lib "eagle-import") (part "R-US_R0603"))
    )
    (comp (ref "R2")
      (value "100k")
      (footprint "eagle-import:R0603")
      (libsource (lib "eagle-import") (part "R-US_R0603"))
    )
    (comp (ref "R8")
      (value "0")
      (footprint "eagle-import:R0603")
      (libsource (lib "eagle-import") (part "R-US_R0603"))
    )
    (comp (ref "R9")
      (value "0")
      (footprint "eagle-import:R0603")
      (libsource (lib "eagle-import") (part "R-US_R0603"))
    )
    (comp (ref "R10")
      (value "0")
      (footprint "eagle-import:R0603")
      (libsource (lib "eagle-import") (part "R-US_R0603"))
    )
    (comp (ref "R11")
      (value "10k")
      (footprint "eagle-import:R0603")
      (libsource (lib "eagle-import") (part "R-US_R0603"))
    )
    (comp (ref "R12")
      (value "1k")
      (footprint "eagle-import:R0603")
      (libsource (lib "eagle-import") (part "R-US_R0603"))
    )
    (comp (ref "R15")
      (value "120")
      (footprint "eagle-import:R0603")
      (libsource (lib "eagle-import") (part "R-US_R0603"))
    )
    (comp (ref "R16")
      (value "120")
      (footprint "eagle-import:R0603")
      (libsource (lib "eagle-import") (part "R-US_R0603"))
    )
    (comp (ref "R17")
      (value "10k")
      (footprint "eagle-import:R0603")
      (libsource (lib "eagle-import") (part "R-US_R0603"))
    )
    (comp (ref "R18")
      (value "5.2k")
      (footprint "eagle-import:R0805")
      (libsource (lib "eagle-import") (part "R-US_R0805"))
    )
    (comp (ref "R19")
      (value "10k")
      (footprint "eagle-import:R0603")
      (libsource (lib "eagle-import") (part "R-US_R0603"))
    )
    (comp (ref "R20")
      (value "10k")
      (footprint "eagle-import:R0603")
      (libsource (lib "eagle-import") (part "R-US_R0603"))
    )
    (comp (ref "R21")
      (value "12k 1%")
      (footprint "eagle-import:R0603")
      (libsource (lib "eagle-import") (part "R-US_R0603"))
    )
    (comp (ref "R22")
      (value "0")
      (footprint "eagle-import:R0805")
      (libsource (lib "eagle-import") (part "R-US_R0805"))
    )
    (comp (ref "R23")
      (value "DNP")
      (footprint "eagle-import:R0805")
      (libsource (lib "eagle-import") (part "R-US_R0805"))
    )
    (comp (ref "R24")
      (value "0")
      (footprint "eagle-import:R0603")
      (libsource (lib "eagle-import") (part "R-US_R0603"))
    )
    (comp (ref "R25")
      (value "DNP")
      (footprint "eagle-import:R0603")
      (libsource (lib "eagle-import") (part "R-US_R0603"))
    )
    (comp (ref "R26")
      (value "0")
      (footprint "eagle-import:R0603")
      (libsource (lib "eagle-import") (part "R-US_R0603"))
    )
    (comp (ref "R27")
      (value "DNP")
      (footprint "eagle-import:R0603")
      (libsource (lib "eagle-import") (part "R-US_R0603"))
    )
    (comp (ref "R28")
      (value "1M")
      (footprint "eagle-import:R0603")
      (libsource (lib "eagle-import") (part "R-US_R0603"))
    )
    (comp (ref "R29")
      (value "0")
      (footprint "eagle-import:R0805")
      (libsource (lib "eagle-import") (part "R-US_R0805"))
    )
    (comp (ref "R30")
      (value "1k")
      (footprint "eagle-import:R0603")
      (libsource (lib "eagle-import") (part "R-US_R0603"))
    )
    (comp (ref "R31")
      (value "10k")
      (footprint "eagle-import:R0603")
      (libsource (lib "eagle-import") (part "R-US_R0603"))
    )
    (comp (ref "R32")
      (value "1k")
      (footprint "eagle-import:R0603")
      (libsource (lib "eagle-import") (part "R-US_R0603"))
    )
    (comp (ref "R33")
      (value "1k")
      (footprint "eagle-import:R0603")
      (libsource (lib "eagle-import") (part "R-US_R0603"))
    )
    (comp (ref "R37")
      (value "0")
      (footprint "eagle-import:R0603")
      (libsource (lib "eagle-import") (part "R-US_R0603"))
    )
    (comp (ref "R38")
      (value "1k")
      (footprint "eagle-import:R0603")
      (libsource (lib "eagle-import") (part "R-US_R0603"))
    )
    (comp (ref "R39")
      (value "1k")
      (footprint "eagle-import:R0603")
      (libsource (lib "eagle-import") (part "R-US_R0603"))
    )
    (comp (ref "R40")
      (value "1k")
      (footprint "eagle-import:R0603")
      (libsource (lib "eagle-import") (part "R-US_R0603"))
    )
    (comp (ref "R59")
      (value "330")
      (footprint "eagle-import:R0603")
      (libsource (lib "eagle-import") (part "R-US_R0603"))
    )
    (comp (ref "R61")
      (value "330")
      (footprint "eagle-import:R0603")
      (libsource (lib "eagle-import") (part "R-US_R0603"))
    )
    (comp (ref "R70")
      (value "330")
      (footprint "eagle-import:R0603")
      (libsource (lib "eagle-import") (part "R-US_R0603"))
    )
    (comp (ref "R71")
      (value "1k")
      (footprint "eagle-import:R0603")
      (libsource (lib "eagle-import") (part "R-US_R0603"))
    )
    (comp (ref "R72")
      (value "1k")
      (footprint "eagle-import:R0603")
      (libsource (lib "eagle-import") (part "R-US_R0603"))
    )
    (comp (ref "R75")
      (value "1k")
      (footprint "eagle-import:R0603")
      (libsource (lib "eagle-import") (part "R-US_R0603"))
    )
    (comp (ref "R79")
      (value "1k")
      (footprint "eagle-import:R0603")
      (libsource (lib "eagle-import") (part "R-US_R0603"))
    )
    (comp (ref "R87")
      (value "0")
      (footprint "eagle-import:R0805")
      (libsource (lib "eagle-import") (part "R-US_R0805"))
    )
    (comp (ref "RPI_OTG")
      (value "TPB1,27")
      (footprint "eagle-import:B1,27")
      (libsource (lib "eagle-import") (part "TPB1,27"))
    )
    (comp (ref "RX_Y")
      (value "JUMPER-SMT_3_1-NC_PASTE_SILK")
      (footprint "eagle-import:SMT-JUMPER_3_1-NC_PASTE_SILK")
      (libsource (lib "eagle-import") (part "JUMPER-SMT_3_1-NC_PASTE_SILK"))
    )
    (comp (ref "RX_Z")
      (value "JUMPER-SMT_3_1-NC_PASTE_SILK")
      (footprint "eagle-import:SMT-JUMPER_3_1-NC_PASTE_SILK")
      (libsource (lib "eagle-import") (part "JUMPER-SMT_3_1-NC_PASTE_SILK"))
    )
    (comp (ref "S1")
      (value "AAT4616")
      (footprint "eagle-import:AAT4616")
      (fields (field (name "MPN") "AAT4616IGV-T1"))
      (libsource (lib "eagle-import") (part "AAT4616"))
    )
    (comp (ref "S2")
      (value "AAT4616")
      (footprint "eagle-import:AAT4616")
      (fields (field (name "MPN") "AAT4616IGV-T1"))
      (libsource (lib "eagle-import") (part "AAT4616"))
    )
    (comp (ref "S3")
      (value "AAT4616")
      (footprint "eagle-import:AAT4616")
      (fields (field (name "MPN") "AAT4616IGV-T1"))
      (libsource (lib "eagle-import") (part "AAT4616"))
    )
    (comp (ref "S4")
      (value "FSUSB42MUX")
      (footprint "eagle-import:FSUSB42MUX")
      (libsource (lib "eagle-import") (part "FSUSB42MUX"))
    )
    (comp (ref "S5")
      (value "FSUSB42MUX")
      (footprint "eagle-import:FSUSB42MUX")
      (libsource (lib "eagle-import") (part "FSUSB42MUX"))
    )
    (comp (ref "S_USB_F")
      (value "TP_HRWN")
      (footprint "eagle-import:TP_HRWN")
      (fields (field (name "MPN") "S2751-46R"))
      (libsource (lib "eagle-import") (part "TP_HRWN"))
    )
    (comp (ref "S_USB_RPI")
      (value "TP_HRWN")
      (footprint "eagle-import:TP_HRWN")
      (fields (field (name "MPN") "S2751-46R"))
      (libsource (lib "eagle-import") (part "TP_HRWN"))
    )
    (comp (ref "TILE")
      (value "green")
      (footprint "eagle-import:SML0603")
      (fields (field (name "MPN") "LG L29K-F2J1-24-Z"))
      (libsource (lib "eagle-import") (part "LEDSML0603"))
    )
    (comp (ref "TILE_1")
      (value "TPTP15SQ")
      (footprint "eagle-import:TP15SQ")
      (libsource (lib "eagle-import") (part "TPTP15SQ"))
    )
    (comp (ref "TILE_2")
      (value "TPTP15SQ")
      (footprint "eagle-import:TP15SQ")
      (libsource (lib "eagle-import") (part "TPTP15SQ"))
    )
    (comp (ref "TILE_3")
      (value "TPTP15SQ")
      (footprint "eagle-import:TP15SQ")
      (libsource (lib "eagle-import") (part "TPTP15SQ"))
    )
    (comp (ref "TILE_4")
      (value "TPTP15SQ")
      (footprint "eagle-import:TP15SQ")
      (libsource (lib "eagle-import") (part "TPTP15SQ"))
    )
    (comp (ref "TILE_5")
      (value "TPTP15SQ")
      (footprint "eagle-import:TP15SQ")
      (libsource (lib "eagle-import") (part "TPTP15SQ"))
    )
    (comp (ref "TILE_RX")
      (value "Green")
      (footprint "eagle-import:SML0603")
      (fields (field (name "MPN") "150060VS75000"))
      (libsource (lib "eagle-import") (part "LEDSML0603"))
    )
    (comp (ref "TILE_TX")
      (value "Red")
      (footprint "eagle-import:SML0603")
      (fields (field (name "MPN") "LTST-C190CKT"))
      (libsource (lib "eagle-import") (part "LEDSML0603"))
    )
    (comp (ref "TX_A")
      (value "JUMPER-SMT_3_1-NC_PASTE_SILK")
      (footprint "eagle-import:SMT-JUMPER_3_1-NC_PASTE_SILK")
      (libsource (lib "eagle-import") (part "JUMPER-SMT_3_1-NC_PASTE_SILK"))
    )
    (comp (ref "TX_B")
      (value "JUMPER-SMT_3_1-NC_PASTE_SILK")
      (footprint "eagle-import:SMT-JUMPER_3_1-NC_PASTE_SILK")
      (libsource (lib "eagle-import") (part "JUMPER-SMT_3_1-NC_PASTE_SILK"))
    )
    (comp (ref "T_RX")
      (value "TP_HRWN")
      (footprint "eagle-import:TP_HRWN")
      (fields (field (name "MPN") "S2751-46R"))
      (libsource (lib "eagle-import") (part "TP_HRWN"))
    )
    (comp (ref "T_TX")
      (value "TP_HRWN")
      (footprint "eagle-import:TP_HRWN")
      (fields (field (name "MPN") "S2751-46R"))
      (libsource (lib "eagle-import") (part "TP_HRWN"))
    )
    (comp (ref "U8")
      (value "USB2517I-JZX")
      (footprint "eagle-import:QFN50P900X900X100-65N")
      (fields (field (name "MF") "Microchip") (field (name "MPN") "USB2517I-JZX-TR"))
      (libsource (lib "eagle-import") (part "USB2517I-JZX"))
    )
    (comp (ref "U18")
      (value "RH100")
      (footprint "eagle-import:RH100")
      (fields (field (name "MPN") "RH100-24.000-20-3050-EXT-TR"))
      (libsource (lib "eagle-import") (part "RH100"))
    )
    (comp (ref "USB_F_VBUS")
      (value "red")
      (footprint "eagle-import:SML0603")
      (fields (field (name "MPN") "LTST-C190CKT"))
      (libsource (lib "eagle-import") (part "LEDSML0603"))
    )
    (comp (ref "USB_SUSP_IND")
      (value "TPTP18SQ")
      (footprint "eagle-import:TP18SQ")
      (libsource (lib "eagle-import") (part "TPTP18SQ"))
    )
    (comp (ref "VIS")
      (value "green")
      (footprint "eagle-import:SML0603")
      (fields (field (name "MPN") "LG L29K-F2J1-24-Z"))
      (libsource (lib "eagle-import") (part "LEDSML0603"))
    )
    (comp (ref "VIS_1")
      (value "TPTP15SQ")
      (footprint "eagle-import:TP15SQ")
      (libsource (lib "eagle-import") (part "TPTP15SQ"))
    )
    (comp (ref "VIS_2")
      (value "TPTP15SQ")
      (footprint "eagle-import:TP15SQ")
      (libsource (lib "eagle-import") (part "TPTP15SQ"))
    )
    (comp (ref "VIS_3")
      (value "TPTP15SQ")
      (footprint "eagle-import:TP15SQ")
      (libsource (lib "eagle-import") (part "TPTP15SQ"))
    )
    (comp (ref "VIS_5V")
      (value "red")
      (footprint "eagle-import:SML0603")
      (fields (field (name "MPN") "LTST-C190CKT"))
      (libsource (lib "eagle-import") (part "LEDSML0603"))
    )
    (comp (ref "ANT_1")
      (value "TPTP18SQ")
      (footprint "eagle-import:TP18SQ")
      (libsource (lib "eagle-import") (part "TPTP18SQ"))
    )
    (comp (ref "ANT_2")
      (value "TPTP18SQ")
      (footprint "eagle-import:TP18SQ")
      (libsource (lib "eagle-import") (part "TPTP18SQ"))
    )
    (comp (ref "ANT_3")
      (value "TPTP18SQ")
      (footprint "eagle-import:TP18SQ")
      (libsource (lib "eagle-import") (part "TPTP18SQ"))
    )
    (comp (ref "BB_1")
      (value "TPTP18SQ")
      (footprint "eagle-import:TP18SQ")
      (libsource (lib "eagle-import") (part "TPTP18SQ"))
    )
    (comp (ref "BB_2")
      (value "TPTP18SQ")
      (footprint "eagle-import:TP18SQ")
      (libsource (lib "eagle-import") (part "TPTP18SQ"))
    )
    (comp (ref "BB_3")
      (value "TPTP18SQ")
      (footprint "eagle-import:TP18SQ")
      (libsource (lib "eagle-import") (part "TPTP18SQ"))
    )
    (comp (ref "BB_4")
      (value "TPTP18SQ")
      (footprint "eagle-import:TP18SQ")
      (libsource (lib "eagle-import") (part "TPTP18SQ"))
    )
    (comp (ref "BB_5")
      (value "TPTP18SQ")
      (footprint "eagle-import:TP18SQ")
      (libsource (lib "eagle-import") (part "TPTP18SQ"))
    )
    (comp (ref "BB_RX_SHIFT")
      (value "TP_HRWN")
      (footprint "eagle-import:TP_HRWN")
      (fields (field (name "MPN") "S2751-46R"))
      (libsource (lib "eagle-import") (part "TP_HRWN"))
    )
    (comp (ref "BB_TX_SHIFT")
      (value "TP_HRWN")
      (footprint "eagle-import:TP_HRWN")
      (fields (field (name "MPN") "S2751-46R") (field (name "MPN_1") "S2751-46R"))
      (libsource (lib "eagle-import") (part "TP_HRWN"))
    )
    (comp (ref "C30")
      (value "0.1u 10V")
      (footprint "eagle-import:C0603")
      (libsource (lib "eagle-import") (part "C-EUC0603"))
    )
    (comp (ref "C31")
      (value "0.1u 10V")
      (footprint "eagle-import:C0603")
      (libsource (lib "eagle-import") (part "C-EUC0603"))
    )
    (comp (ref "C51")
      (value "0.1u 10V")
      (footprint "eagle-import:C0603")
      (libsource (lib "eagle-import") (part "C-EUC0603"))
    )
    (comp (ref "C52")
      (value "0.1u 10V")
      (footprint "eagle-import:C0603")
      (libsource (lib "eagle-import") (part "C-EUC0603"))
    )
    (comp (ref "C57")
      (value "0.1u 10V")
      (footprint "eagle-import:C0603")
      (libsource (lib "eagle-import") (part "C-EUC0603"))
    )
    (comp (ref "C87")
      (value "0.1u 10V")
      (footprint "eagle-import:C0603")
      (libsource (lib "eagle-import") (part "C-EUC0603"))
    )
    (comp (ref "C88")
      (value "0.1u 10V")
      (footprint "eagle-import:C0603")
      (libsource (lib "eagle-import") (part "C-EUC0603"))
    )
    (comp (ref "C89")
      (value "0.1u 10V")
      (footprint "eagle-import:C0603")
      (libsource (lib "eagle-import") (part "C-EUC0603"))
    )
    (comp (ref "C90")
      (value "0.1u 10V")
      (footprint "eagle-import:C0603")
      (libsource (lib "eagle-import") (part "C-EUC0603"))
    )
    (comp (ref "GND58")
      (value "TP_HRWN")
      (footprint "eagle-import:TP_HRWN")
      (fields (field (name "MPN") "S2751-46R") (field (name "MPN_1") "S2751-46R"))
      (libsource (lib "eagle-import") (part "TP_HRWN"))
    )
    (comp (ref "GND59")
      (value "TP_HRWN")
      (footprint "eagle-import:TP_HRWN")
      (fields (field (name "MPN") "S2751-46R") (field (name "MPN_1") "S2751-46R"))
      (libsource (lib "eagle-import") (part "TP_HRWN"))
    )
    (comp (ref "J3")
      (value "T1M-06-F-SH-L-K")
      (footprint "eagle-import:T1M-06-F-SH-L-K")
      (fields (field (name "MPN") "T1M-06-F-SH-L"))
      (libsource (lib "eagle-import") (part "T1M-06-F-SH-L-K"))
    )
    (comp (ref "J9")
      (value "T1M-04-F-SV-L")
      (footprint "eagle-import:SAMTEC_T1M-04-F-SV-L")
      (fields (field (name "MF") "Samtec Inc."))
      (libsource (lib "eagle-import") (part "T1M-04-F-SV-L"))
    )
    (comp (ref "J11")
      (value "T1M-06-F-SH-L-K")
      (footprint "eagle-import:T1M-06-F-SH-L-K")
      (fields (field (name "MPN") "T1M-06-F-SH-L"))
      (libsource (lib "eagle-import") (part "T1M-06-F-SH-L-K"))
    )
    (comp (ref "LST_1")
      (value "TPTP15SQ")
      (footprint "eagle-import:TP15SQ")
      (libsource (lib "eagle-import") (part "TPTP15SQ"))
    )
    (comp (ref "LST_2")
      (value "TPTP15SQ")
      (footprint "eagle-import:TP15SQ")
      (libsource (lib "eagle-import") (part "TPTP15SQ"))
    )
    (comp (ref "LST_3")
      (value "TPTP15SQ")
      (footprint "eagle-import:TP15SQ")
      (libsource (lib "eagle-import") (part "TPTP15SQ"))
    )
    (comp (ref "LST_4")
      (value "TPTP15SQ")
      (footprint "eagle-import:TP15SQ")
      (libsource (lib "eagle-import") (part "TPTP15SQ"))
    )
    (comp (ref "LST_5")
      (value "TPTP15SQ")
      (footprint "eagle-import:TP15SQ")
      (libsource (lib "eagle-import") (part "TPTP15SQ"))
    )
    (comp (ref "LST_RX")
      (value "TP_HRWN")
      (footprint "eagle-import:TP_HRWN")
      (fields (field (name "MPN") "S2751-46R") (field (name "MPN_1") "S2751-46R"))
      (libsource (lib "eagle-import") (part "TP_HRWN"))
    )
    (comp (ref "LST_SEL")
      (value "TPB1,27")
      (footprint "eagle-import:B1,27")
      (libsource (lib "eagle-import") (part "TPB1,27"))
    )
    (comp (ref "LST_TX")
      (value "TP_HRWN")
      (footprint "eagle-import:TP_HRWN")
      (fields (field (name "MPN") "S2751-46R") (field (name "MPN_1") "S2751-46R"))
      (libsource (lib "eagle-import") (part "TP_HRWN"))
    )
    (comp (ref "RPIA_RX_LST")
      (value "TP_HRWN")
      (footprint "eagle-import:TP_HRWN")
      (fields (field (name "MPN") "S2751-46R") (field (name "MPN_1") "S2751-46R"))
      (libsource (lib "eagle-import") (part "TP_HRWN"))
    )
    (comp (ref "RPIA_TX_LST")
      (value "TP_HRWN")
      (footprint "eagle-import:TP_HRWN")
      (fields (field (name "MPN") "S2751-46R") (field (name "MPN_1") "S2751-46R"))
      (libsource (lib "eagle-import") (part "TP_HRWN"))
    )
    (comp (ref "S6")
      (value "FSUSB42MUX")
      (footprint "eagle-import:FSUSB42MUX")
      (libsource (lib "eagle-import") (part "FSUSB42MUX"))
    )
    (comp (ref "S7")
      (value "FSUSB42MUX")
      (footprint "eagle-import:FSUSB42MUX")
      (libsource (lib "eagle-import") (part "FSUSB42MUX"))
    )
    (comp (ref "S10")
      (value "FSUSB42MUX")
      (footprint "eagle-import:FSUSB42MUX")
      (libsource (lib "eagle-import") (part "FSUSB42MUX"))
    )
    (comp (ref "U1")
      (value "ICM-20948")
      (footprint "eagle-import:QFN40P300X300X105-24N")
      (fields (field (name "MF") "TDK InvenSense"))
      (libsource (lib "eagle-import") (part "ICM-20948"))
    )
    (comp (ref "U2")
      (value "SN74LV1T34")
      (footprint "eagle-import:SOT23-5")
      (fields (field (name "MPN") "SN74LV1T34DBVR"))
      (libsource (lib "eagle-import") (part "SN74LV1T34"))
    )
    (comp (ref "U3")
      (value "ICM-20948")
      (footprint "eagle-import:QFN40P300X300X105-24N")
      (fields (field (name "MF") "TDK InvenSense"))
      (libsource (lib "eagle-import") (part "ICM-20948"))
    )
    (comp (ref "U9")
      (value "SN74LV1T34")
      (footprint "eagle-import:SOT23-5")
      (fields (field (name "MPN") "SN74LV1T34DBVR"))
      (libsource (lib "eagle-import") (part "SN74LV1T34"))
    )
    (comp (ref "U10")
      (value "SN74LV1T34")
      (footprint "eagle-import:SOT23-5")
      (fields (field (name "MPN") "SN74LV1T34DBVR"))
      (libsource (lib "eagle-import") (part "SN74LV1T34"))
    )
    (comp (ref "U19")
      (value "SN74LV1T34")
      (footprint "eagle-import:SOT23-5")
      (fields (field (name "MPN") "SN74LV1T34DBVR"))
      (libsource (lib "eagle-import") (part "SN74LV1T34"))
    )
    (comp (ref "U22")
      (value "SN74LV1T34")
      (footprint "eagle-import:SOT23-5")
      (fields (field (name "MPN") "SN74LV1T34DBVR"))
      (libsource (lib "eagle-import") (part "SN74LV1T34"))
    )
    (comp (ref "U23")
      (value "SN74LV1T34")
      (footprint "eagle-import:SOT23-5")
      (fields (field (name "MPN") "SN74LV1T34DBVR"))
      (libsource (lib "eagle-import") (part "SN74LV1T34"))
    )
    (comp (ref "U24")
      (value "SN74LV1T34")
      (footprint "eagle-import:SOT23-5")
      (fields (field (name "MPN") "SN74LV1T34DBVR"))
      (libsource (lib "eagle-import") (part "SN74LV1T34"))
    )
    (comp (ref "U25")
      (value "SN74LV1T34")
      (footprint "eagle-import:SOT23-5")
      (fields (field (name "MPN") "SN74LV1T34DBVR"))
      (libsource (lib "eagle-import") (part "SN74LV1T34"))
    )
    (comp (ref "1V8_RPIA")
      (value "TPB1,27")
      (footprint "eagle-import:B1,27")
      (libsource (lib "eagle-import") (part "TPB1,27"))
    )
    (comp (ref "1V8_RPIB")
      (value "TPB1,27")
      (footprint "eagle-import:B1,27")
      (libsource (lib "eagle-import") (part "TPB1,27"))
    )
    (comp (ref "3V3_RPIA")
      (value "TP_HRWN")
      (footprint "eagle-import:TP_HRWN")
      (fields (field (name "MPN") "S2751-46R") (field (name "MPN_1") "S2751-46R"))
      (libsource (lib "eagle-import") (part "TP_HRWN"))
    )
    (comp (ref "3V3_RPIB")
      (value "TP_HRWN")
      (footprint "eagle-import:TP_HRWN")
      (fields (field (name "MPN") "S2751-46R") (field (name "MPN_1") "S2751-46R"))
      (libsource (lib "eagle-import") (part "TP_HRWN"))
    )
    (comp (ref "C10")
      (value "22u 16V")
      (footprint "eagle-import:C1206")
      (libsource (lib "eagle-import") (part "C-EUC1206"))
    )
    (comp (ref "C11")
      (value "4.7n 16V")
      (footprint "eagle-import:C0603")
      (libsource (lib "eagle-import") (part "C-EUC0603"))
    )
    (comp (ref "C12")
      (value "10u 10V")
      (footprint "eagle-import:C1206")
      (libsource (lib "eagle-import") (part "C-EUC1206"))
    )
    (comp (ref "C13")
      (value "22u 16V")
      (footprint "eagle-import:C1206")
      (libsource (lib "eagle-import") (part "C-EUC1206"))
    )
    (comp (ref "C14")
      (value "4.7n 16V")
      (footprint "eagle-import:C0603")
      (libsource (lib "eagle-import") (part "C-EUC0603"))
    )
    (comp (ref "C15")
      (value "10u 10V")
      (footprint "eagle-import:C1206")
      (libsource (lib "eagle-import") (part "C-EUC1206"))
    )
    (comp (ref "C16")
      (value "10p 50V")
      (footprint "eagle-import:C0603")
      (libsource (lib "eagle-import") (part "C-EUC0603"))
    )
    (comp (ref "C17")
      (value "47u 16V")
      (footprint "eagle-import:C1210")
      (libsource (lib "eagle-import") (part "C-EUC1210"))
    )
    (comp (ref "C18")
      (value "47u 16V")
      (footprint "eagle-import:C1210")
      (libsource (lib "eagle-import") (part "C-EUC1210"))
    )
    (comp (ref "C19")
      (value "4.7n 16V")
      (footprint "eagle-import:C0603")
      (libsource (lib "eagle-import") (part "C-EUC0603"))
    )
    (comp (ref "C20")
      (value "DNP")
      (footprint "eagle-import:C0805")
      (libsource (lib "eagle-import") (part "C-USC0805"))
    )
    (comp (ref "C21")
      (value "DNP")
      (footprint "eagle-import:C0805")
      (libsource (lib "eagle-import") (part "C-USC0805"))
    )
    (comp (ref "C22")
      (value "DNP")
      (footprint "eagle-import:C0805")
      (libsource (lib "eagle-import") (part "C-USC0805"))
    )
    (comp (ref "C23")
      (value "DNP")
      (footprint "eagle-import:C0805")
      (libsource (lib "eagle-import") (part "C-USC0805"))
    )
    (comp (ref "C24")
      (value "10p 50V")
      (footprint "eagle-import:C0603")
      (libsource (lib "eagle-import") (part "C-EUC0603"))
    )
    (comp (ref "C58")
      (value "DNP")
      (footprint "eagle-import:C0805")
      (libsource (lib "eagle-import") (part "C-USC0805"))
    )
    (comp (ref "C59")
      (value "DNP")
      (footprint "eagle-import:C0805")
      (libsource (lib "eagle-import") (part "C-USC0805"))
    )
    (comp (ref "C60")
      (value "DNP")
      (footprint "eagle-import:C0805")
      (libsource (lib "eagle-import") (part "C-USC0805"))
    )
    (comp (ref "C61")
      (value "DNP")
      (footprint "eagle-import:C0805")
      (libsource (lib "eagle-import") (part "C-USC0805"))
    )
    (comp (ref "C62")
      (value "22u 16V")
      (footprint "eagle-import:C1206")
      (libsource (lib "eagle-import") (part "C-EUC1206"))
    )
    (comp (ref "C63")
      (value "4.7n 16V")
      (footprint "eagle-import:C0603")
      (libsource (lib "eagle-import") (part "C-EUC0603"))
    )
    (comp (ref "C64")
      (value "22u 16V")
      (footprint "eagle-import:C1206")
      (libsource (lib "eagle-import") (part "C-EUC1206"))
    )
    (comp (ref "C79")
      (value "DNP")
      (footprint "eagle-import:C0805")
      (libsource (lib "eagle-import") (part "C-USC0805"))
    )
    (comp (ref "C80")
      (value "DNP")
      (footprint "eagle-import:C0805")
      (libsource (lib "eagle-import") (part "C-USC0805"))
    )
    (comp (ref "C81")
      (value "DNP")
      (footprint "eagle-import:C0805")
      (libsource (lib "eagle-import") (part "C-USC0805"))
    )
    (comp (ref "C82")
      (value "DNP")
      (footprint "eagle-import:C0805")
      (libsource (lib "eagle-import") (part "C-USC0805"))
    )
    (comp (ref "L1")
      (value "0.47uH")
      (footprint "eagle-import:LPS3010")
      (fields (field (name "MPN") "LPS3010-471MRC"))
      (libsource (lib "eagle-import") (part "LPS3010"))
    )
    (comp (ref "L2")
      (value "0.47uH")
      (footprint "eagle-import:LPS3010")
      (fields (field (name "MPN") "LPS3010-471MRC"))
      (libsource (lib "eagle-import") (part "LPS3010"))
    )
    (comp (ref "L3")
      (value ".56uH")
      (footprint "eagle-import:INDP_LPS4018-472MRB")
      (fields
        (field (name "MF") "Coilcraft")
        (field (name "MP") "LPS4018-472MRB")
        (field (name "MPN") "LPS4018-561MRC ")
      )
      (libsource (lib "eagle-import") (part "LPS4018-472MRB"))
    )
    (comp (ref "L4")
      (value ".56uH")
      (footprint "eagle-import:INDP_LPS4018-472MRB")
      (fields
        (field (name "MF") "Coilcraft")
        (field (name "MP") "LPS4018-472MRB")
        (field (name "MPN") "LPS4018-561MRC ")
      )
      (libsource (lib "eagle-import") (part "LPS4018-472MRB"))
    )
    (comp (ref "R58")
      (value "8.06k 1%")
      (footprint "eagle-import:R0603")
      (libsource (lib "eagle-import") (part "R-US_R0603"))
    )
    (comp (ref "R60")
      (value "8.06k 1%")
      (footprint "eagle-import:R0603")
      (libsource (lib "eagle-import") (part "R-US_R0603"))
    )
    (comp (ref "R62")
      (value "1k")
      (footprint "eagle-import:R0603")
      (libsource (lib "eagle-import") (part "R-US_R0603"))
    )
    (comp (ref "R63")
      (value "1k")
      (footprint "eagle-import:R0603")
      (libsource (lib "eagle-import") (part "R-US_R0603"))
    )
    (comp (ref "R64")
      (value "120")
      (footprint "eagle-import:R0603")
      (libsource (lib "eagle-import") (part "R-US_R0603"))
    )
    (comp (ref "R65")
      (value "120")
      (footprint "eagle-import:R0603")
      (libsource (lib "eagle-import") (part "R-US_R0603"))
    )
    (comp (ref "R76")
      (value "453k 1%")
      (footprint "eagle-import:R0603")
      (libsource (lib "eagle-import") (part "R-US_R0603"))
    )
    (comp (ref "R77")
      (value "100k 1%")
      (footprint "eagle-import:R0603")
      (libsource (lib "eagle-import") (part "R-US_R0603"))
    )
    (comp (ref "R78")
      (value "32k 0.1%")
      (footprint "eagle-import:R0603")
      (libsource (lib "eagle-import") (part "R-US_R0603"))
    )
    (comp (ref "R80")
      (value "453k 1%")
      (footprint "eagle-import:R0603")
      (libsource (lib "eagle-import") (part "R-US_R0603"))
    )
    (comp (ref "R81")
      (value "100k 1%")
      (footprint "eagle-import:R0603")
      (libsource (lib "eagle-import") (part "R-US_R0603"))
    )
    (comp (ref "R82")
      (value "32k 0.1%")
      (footprint "eagle-import:R0603")
      (libsource (lib "eagle-import") (part "R-US_R0603"))
    )
    (comp (ref "RPIA_1V8")
      (value "green")
      (footprint "eagle-import:SML0603")
      (fields (field (name "MPN") "LG L29K-F2J1-24-Z"))
      (libsource (lib "eagle-import") (part "LEDSML0603"))
    )
    (comp (ref "RPIA_3V3")
      (value "green")
      (footprint "eagle-import:SML0603")
      (fields (field (name "MPN") "150060VS75000"))
      (libsource (lib "eagle-import") (part "LEDSML0603"))
    )
    (comp (ref "RPIB_1V8")
      (value "green")
      (footprint "eagle-import:SML0603")
      (fields (field (name "MPN") "LG L29K-F2J1-24-Z"))
      (libsource (lib "eagle-import") (part "LEDSML0603"))
    )
    (comp (ref "RPIB_3V3")
      (value "green")
      (footprint "eagle-import:SML0603")
      (fields (field (name "MPN") "150060VS75000"))
      (libsource (lib "eagle-import") (part "LEDSML0603"))
    )
    (comp (ref "U7")
      (value "Value")
      (footprint "eagle-import:RWY0009A")
      (fields
        (field (name "MANUFACTURER") "Texas Instruments")
        (field (name "PARTNUMBER") "TPS628112AQWRWYRQ1")
        (field (name "MPN") "TPS628112MQWRWYRQ1")
        (field (name "PARTNUMBER_1") "TPS628112MQWRWYRQ1")
      )
      (libsource (lib "eagle-import") (part "TPS628112AQWRWYRQ1"))
    )
    (comp (ref "U15")
      (value "Value")
      (footprint "eagle-import:RWY0009A")
      (fields
        (field (name "MANUFACTURER") "Texas Instruments")
        (field (name "PARTNUMBER") "TPS628112AQWRWYRQ1")
        (field (name "MPN") "TPS628112MQWRWYRQ1")
        (field (name "PARTNUMBER_1") "TPS628112MQWRWYRQ1")
      )
      (libsource (lib "eagle-import") (part "TPS628112AQWRWYRQ1"))
    )
    (comp (ref "U16")
      (value "Value")
      (footprint "eagle-import:RWY0009A")
      (fields
        (field (name "MANUFACTURER") "Texas Instruments")
        (field (name "PARTNUMBER") "TPS628112AQWRWYRQ1")
        (field (name "MPN") "TPS62812QWRWYRQ1 ")
        (field (name "PARTNUMBER_1") "TPS62812QWRWYRQ1 ")
      )
      (libsource (lib "eagle-import") (part "TPS628112AQWRWYRQ1"))
    )
    (comp (ref "U17")
      (value "Value")
      (footprint "eagle-import:RWY0009A")
      (fields
        (field (name "MANUFACTURER") "Texas Instruments")
        (field (name "PARTNUMBER") "TPS628112AQWRWYRQ1")
        (field (name "MPN") "TPS62812QWRWYRQ1 ")
        (field (name "PARTNUMBER_1") "TPS62812QWRWYRQ1 ")
      )
      (libsource (lib "eagle-import") (part "TPS628112AQWRWYRQ1"))
    )
    (comp (ref "+3V3_VIN")
      (value "TP_HRWN")
      (footprint "eagle-import:TP_HRWN")
      (fields (field (name "MPN") "S2751-46R") (field (name "MPN_1") "S2751-46R"))
      (libsource (lib "eagle-import") (part "TP_HRWN"))
    )
    (comp (ref "+5V_VIN")
      (value "TP_HRWN")
      (footprint "eagle-import:TP_HRWN")
      (fields (field (name "MPN") "S2751-46R") (field (name "MPN_1") "S2751-46R"))
      (libsource (lib "eagle-import") (part "TP_HRWN"))
    )
    (comp (ref "C25")
      (value "0.1u 10V")
      (footprint "eagle-import:C0603")
      (libsource (lib "eagle-import") (part "C-EUC0603"))
    )
    (comp (ref "C53")
      (value "6.8p 16V")
      (footprint "eagle-import:C0603")
      (libsource (lib "eagle-import") (part "C-EUC0603"))
    )
    (comp (ref "C54")
      (value "6.8p 16V")
      (footprint "eagle-import:C0603")
      (libsource (lib "eagle-import") (part "C-EUC0603"))
    )
    (comp (ref "C65")
      (value "0.1u 10V")
      (footprint "eagle-import:C0603")
      (libsource (lib "eagle-import") (part "C-EUC0603"))
    )
    (comp (ref "C66")
      (value "0.1u 10V")
      (footprint "eagle-import:C0603")
      (libsource (lib "eagle-import") (part "C-EUC0603"))
    )
    (comp (ref "C67")
      (value "0.1u 10V")
      (footprint "eagle-import:C0603")
      (libsource (lib "eagle-import") (part "C-EUC0603"))
    )
    (comp (ref "C68")
      (value "1u 16V")
      (footprint "eagle-import:C0603")
      (libsource (lib "eagle-import") (part "C-EUC0603"))
    )
    (comp (ref "C69")
      (value "0.1u 10V")
      (footprint "eagle-import:C0603")
      (libsource (lib "eagle-import") (part "C-EUC0603"))
    )
    (comp (ref "C70")
      (value "1u 16V")
      (footprint "eagle-import:C0603")
      (libsource (lib "eagle-import") (part "C-EUC0603"))
    )
    (comp (ref "C71")
      (value "0.1u 10V")
      (footprint "eagle-import:C0603")
      (libsource (lib "eagle-import") (part "C-EUC0603"))
    )
    (comp (ref "C72")
      (value "0.1u 10V")
      (footprint "eagle-import:C0603")
      (libsource (lib "eagle-import") (part "C-EUC0603"))
    )
    (comp (ref "C73")
      (value "0.1u 10V")
      (footprint "eagle-import:C0603")
      (libsource (lib "eagle-import") (part "C-EUC0603"))
    )
    (comp (ref "C74")
      (value "0.1u 10V")
      (footprint "eagle-import:C0603")
      (libsource (lib "eagle-import") (part "C-EUC0603"))
    )
    (comp (ref "C77")
      (value "0.1u 10V")
      (footprint "eagle-import:C0603")
      (libsource (lib "eagle-import") (part "C-EUC0603"))
    )
    (comp (ref "C78")
      (value "0.1u 10V")
      (footprint "eagle-import:C0603")
      (libsource (lib "eagle-import") (part "C-EUC0603"))
    )
    (comp (ref "GND62")
      (value "TP_HRWN")
      (footprint "eagle-import:TP_HRWN")
      (fields (field (name "MPN") "S2751-46R") (field (name "MPN_1") "S2751-46R"))
      (libsource (lib "eagle-import") (part "TP_HRWN"))
    )
    (comp (ref "GND64")
      (value "TP_HRWN")
      (footprint "eagle-import:TP_HRWN")
      (fields (field (name "MPN") "S2751-46R") (field (name "MPN_1") "S2751-46R"))
      (libsource (lib "eagle-import") (part "TP_HRWN"))
    )
    (comp (ref "GND66")
      (value "TP_HRWN")
      (footprint "eagle-import:TP_HRWN")
      (fields (field (name "MPN") "S2751-46R") (field (name "MPN_1") "S2751-46R"))
      (libsource (lib "eagle-import") (part "TP_HRWN"))
    )
    (comp (ref "GND70")
      (value "TP_HRWN")
      (footprint "eagle-import:TP_HRWN")
      (fields (field (name "MPN") "S2751-46R") (field (name "MPN_1") "S2751-46R"))
      (libsource (lib "eagle-import") (part "TP_HRWN"))
    )
    (comp (ref "H1-CONNECTOR1")
      (value "SSQ-126-XX-XXX-D")
      (footprint "eagle-import:SSQ-126-XX-XXX-D")
      (fields (field (name "MPN") "SSQ-126-23-G-D"))
      (libsource (lib "eagle-import") (part "SSQ-126-XX-XXX-D"))
    )
    (comp (ref "H2-CONNECTOR1")
      (value "SSQ-126-XX-XXX-D")
      (footprint "eagle-import:SSQ-126-XX-XXX-D")
      (fields (field (name "MPN") "SSQ-126-23-G-D"))
      (libsource (lib "eagle-import") (part "SSQ-126-XX-XXX-D"))
    )
    (comp (ref "I2C_0_C")
      (value "TPB1,27")
      (footprint "eagle-import:B1,27")
      (libsource (lib "eagle-import") (part "TPB1,27"))
    )
    (comp (ref "I2C_0_D")
      (value "TPB1,27")
      (footprint "eagle-import:B1,27")
      (libsource (lib "eagle-import") (part "TPB1,27"))
    )
    (comp (ref "I2C_1_C")
      (value "TPB1,27")
      (footprint "eagle-import:B1,27")
      (libsource (lib "eagle-import") (part "TPB1,27"))
    )
    (comp (ref "I2C_1_D")
      (value "TPB1,27")
      (footprint "eagle-import:B1,27")
      (libsource (lib "eagle-import") (part "TPB1,27"))
    )
    (comp (ref "JP4")
      (value "JUMPER-SMT_3_1-NC_PASTE_SILK")
      (footprint "eagle-import:SMT-JUMPER_3_1-NC_PASTE_SILK")
      (libsource (lib "eagle-import") (part "JUMPER-SMT_3_1-NC_PASTE_SILK"))
    )
    (comp (ref "PIA_I2C_0_C")
      (value "TPB1,27")
      (footprint "eagle-import:B1,27")
      (libsource (lib "eagle-import") (part "TPB1,27"))
    )
    (comp (ref "PIA_I2C_0_D")
      (value "TPB1,27")
      (footprint "eagle-import:B1,27")
      (libsource (lib "eagle-import") (part "TPB1,27"))
    )
    (comp (ref "PIA_I2C_1_C")
      (value "TPB1,27")
      (footprint "eagle-import:B1,27")
      (libsource (lib "eagle-import") (part "TPB1,27"))
    )
    (comp (ref "PIA_I2C_1_D")
      (value "TPB1,27")
      (footprint "eagle-import:B1,27")
      (libsource (lib "eagle-import") (part "TPB1,27"))
    )
    (comp (ref "PIB_I2C_0_C")
      (value "TP_HRWN")
      (footprint "eagle-import:TP_HRWN")
      (fields (field (name "MPN") "S2751-46R") (field (name "MPN_1") "S2751-46R"))
      (libsource (lib "eagle-import") (part "TP_HRWN"))
    )
    (comp (ref "PIB_I2C_0_D")
      (value "TP_HRWN")
      (footprint "eagle-import:TP_HRWN")
      (fields (field (name "MPN") "S2751-46R") (field (name "MPN_1") "S2751-46R"))
      (libsource (lib "eagle-import") (part "TP_HRWN"))
    )
    (comp (ref "R83")
      (value "10k")
      (footprint "eagle-import:R0603")
      (libsource (lib "eagle-import") (part "resistor_348_R-US_R0603"))
    )
    (comp (ref "R84")
      (value "10k")
      (footprint "eagle-import:R0603")
      (libsource (lib "eagle-import") (part "resistor_348_R-US_R0603"))
    )
    (comp (ref "R85")
      (value "10k")
      (footprint "eagle-import:R0603")
      (libsource (lib "eagle-import") (part "resistor_348_R-US_R0603"))
    )
    (comp (ref "R86")
      (value "10k")
      (footprint "eagle-import:R0603")
      (libsource (lib "eagle-import") (part "resistor_348_R-US_R0603"))
    )
    (comp (ref "RPIA_USB_N")
      (value "TPB1,27")
      (footprint "eagle-import:B1,27")
      (libsource (lib "eagle-import") (part "TPB1,27"))
    )
    (comp (ref "RPIA_USB_P")
      (value "TPB1,27")
      (footprint "eagle-import:B1,27")
      (libsource (lib "eagle-import") (part "TPB1,27"))
    )
    (comp (ref "RPIB_USB_N")
      (value "TPB1,27")
      (footprint "eagle-import:B1,27")
      (libsource (lib "eagle-import") (part "TPB1,27"))
    )
    (comp (ref "RPIB_USB_P")
      (value "TPB1,27")
      (footprint "eagle-import:B1,27")
      (libsource (lib "eagle-import") (part "TPB1,27"))
    )
    (comp (ref "RTC_VIN")
      (value "TPB1,27")
      (footprint "eagle-import:B1,27")
      (libsource (lib "eagle-import") (part "TPB1,27"))
    )
    (comp (ref "S8")
      (value "FSUSB42MUX")
      (footprint "eagle-import:FSUSB42MUX")
      (libsource (lib "eagle-import") (part "FSUSB42MUX"))
    )
    (comp (ref "S9")
      (value "FSUSB42MUX")
      (footprint "eagle-import:FSUSB42MUX")
      (libsource (lib "eagle-import") (part "FSUSB42MUX"))
    )
    (comp (ref "U12")
      (value "MCP7940MT-I/SN")
      (footprint "eagle-import:SOIC8-N_MC")
      (fields (field (name "COPYRIGHT") "Copyright (C) 2018 Accelerated Designs. All rights reserved"))
      (libsource (lib "eagle-import") (part "MCP7940MT-I/SN"))
    )
    (comp (ref "U20")
      (value "COMPUTE_MODULE")
      (footprint "eagle-import:SO-DIMM")
      (fields (field (name "MPN") "1473005-4"))
      (libsource (lib "eagle-import") (part "COMPUTE_MODULE"))
    )
    (comp (ref "U21")
      (value "COMPUTE_MODULE")
      (footprint "eagle-import:SO-DIMM")
      (fields (field (name "MPN") "1473005-4"))
      (libsource (lib "eagle-import") (part "COMPUTE_MODULE"))
    )
    (comp (ref "X4")
      (value "TC-135")
      (footprint "eagle-import:TC-135")
      (fields (field (name "MPN") "FC-135 32.768KA-AG0 "))
      (libsource (lib "eagle-import") (part "TC-135"))
    )
    (comp (ref "C1")
      (value "DNP")
      (footprint "eagle-import:C0603")
      (libsource (lib "eagle-import") (part "C-EUC0603"))
    )
    (comp (ref "C2")
      (value "DNP")
      (footprint "eagle-import:C0603")
      (libsource (lib "eagle-import") (part "C-EUC0603"))
    )
    (comp (ref "C28")
      (value "0.1u 10V")
      (footprint "eagle-import:C0603")
      (libsource (lib "eagle-import") (part "C-EUC0603"))
    )
    (comp (ref "C29")
      (value "0.1u 10V")
      (footprint "eagle-import:C0603")
      (libsource (lib "eagle-import") (part "C-EUC0603"))
    )
    (comp (ref "C32")
      (value "10u 10V")
      (footprint "eagle-import:C0805")
      (libsource (lib "eagle-import") (part "C-EUC0805"))
    )
    (comp (ref "C33")
      (value "10u 10V")
      (footprint "eagle-import:C0805")
      (libsource (lib "eagle-import") (part "C-EUC0805"))
    )
    (comp (ref "C55")
      (value "0.1u 10V")
      (footprint "eagle-import:C0603")
      (libsource (lib "eagle-import") (part "C-EUC0603"))
    )
    (comp (ref "C56")
      (value "0.1u 10V")
      (footprint "eagle-import:C0603")
      (libsource (lib "eagle-import") (part "C-EUC0603"))
    )
    (comp (ref "C75")
      (value "0.1u 10V")
      (footprint "eagle-import:C0603")
      (libsource (lib "eagle-import") (part "C-EUC0603"))
    )
    (comp (ref "C76")
      (value "0.1u 10V")
      (footprint "eagle-import:C0603")
      (libsource (lib "eagle-import") (part "C-EUC0603"))
    )
    (comp (ref "C91")
      (value "0.1u 10V")
      (footprint "eagle-import:C0603")
      (libsource (lib "eagle-import") (part "C-EUC0603"))
    )
    (comp (ref "IC4")
      (value "74AUC1G08DBV")
      (footprint "eagle-import:SOT23-5")
      (fields (field (name "MPN") "SN74LVC1G08MDBVREP"))
      (libsource (lib "eagle-import") (part "741G08DBVAUC"))
    )
    (comp (ref "IC5")
      (value "74AUC1G08DBV")
      (footprint "eagle-import:SOT23-5")
      (fields (field (name "MPN") "SN74LVC1G08MDBVREP"))
      (libsource (lib "eagle-import") (part "741G08DBVAUC"))
    )
    (comp (ref "IC6")
      (value "74AHCT1G14DBV")
      (footprint "eagle-import:SOT23-5")
      (fields (field (name "MPN") "SN74LVC1G14MDBVREP"))
      (libsource (lib "eagle-import") (part "741G14DBVAHCT"))
    )
    (comp (ref "IC7")
      (value "74LS112D")
      (footprint "eagle-import:SO16")
      (fields (field (name "MPN") "SN74LVC112ADR"))
      (libsource (lib "eagle-import") (part "74112DLS"))
    )
    (comp (ref "PIA_RUN")
      (value "TP_HRWN")
      (footprint "eagle-import:TP_HRWN")
      (fields (field (name "MPN") "S2751-46R") (field (name "MPN_1") "S2751-46R"))
      (libsource (lib "eagle-import") (part "TP_HRWN"))
    )
    (comp (ref "PIA_SD_SEL")
      (value "TP_HRWN")
      (footprint "eagle-import:TP_HRWN")
      (fields (field (name "MPN") "S2751-46R") (field (name "MPN_1") "S2751-46R"))
      (libsource (lib "eagle-import") (part "TP_HRWN"))
    )
    (comp (ref "PIB_RUN")
      (value "TP_HRWN")
      (footprint "eagle-import:TP_HRWN")
      (fields (field (name "MPN") "S2751-46R") (field (name "MPN_1") "S2751-46R"))
      (libsource (lib "eagle-import") (part "TP_HRWN"))
    )
    (comp (ref "PIB_SD_SEL")
      (value "TP_HRWN")
      (footprint "eagle-import:TP_HRWN")
      (fields (field (name "MPN") "S2751-46R") (field (name "MPN_1") "S2751-46R"))
      (libsource (lib "eagle-import") (part "TP_HRWN"))
    )
    (comp (ref "PI_PWR_SEL")
      (value "TP_HRWN")
      (footprint "eagle-import:TP_HRWN")
      (fields (field (name "MPN") "S2751-46R") (field (name "MPN_1") "S2751-46R"))
      (libsource (lib "eagle-import") (part "TP_HRWN"))
    )
    (comp (ref "R3")
      (value "0")
      (footprint "eagle-import:R0603")
      (libsource (lib "eagle-import") (part "R-US_R0603"))
    )
    (comp (ref "R4")
      (value "10k")
      (footprint "eagle-import:R0603")
      (libsource (lib "eagle-import") (part "R-US_R0603"))
    )
    (comp (ref "R5")
      (value "10k")
      (footprint "eagle-import:R0603")
      (libsource (lib "eagle-import") (part "R-US_R0603"))
    )
    (comp (ref "R6")
      (value "10k")
      (footprint "eagle-import:R0603")
      (libsource (lib "eagle-import") (part "R-US_R0603"))
    )
    (comp (ref "R7")
      (value "10k")
      (footprint "eagle-import:R0603")
      (libsource (lib "eagle-import") (part "R-US_R0603"))
    )
    (comp (ref "R13")
      (value "0")
      (footprint "eagle-import:R0603")
      (libsource (lib "eagle-import") (part "R-US_R0603"))
    )
    (comp (ref "R14")
      (value "0")
      (footprint "eagle-import:R0603")
      (libsource (lib "eagle-import") (part "R-US_R0603"))
    )
    (comp (ref "R34")
      (value "50k")
      (footprint "eagle-import:R0603")
      (libsource (lib "eagle-import") (part "R-US_R0603"))
    )
    (comp (ref "R35")
      (value "50k")
      (footprint "eagle-import:R0603")
      (libsource (lib "eagle-import") (part "R-US_R0603"))
    )
    (comp (ref "R36")
      (value "50k")
      (footprint "eagle-import:R0603")
      (libsource (lib "eagle-import") (part "R-US_R0603"))
    )
    (comp (ref "R41")
      (value "50k")
      (footprint "eagle-import:R0603")
      (libsource (lib "eagle-import") (part "R-US_R0603"))
    )
    (comp (ref "R42")
      (value "50k")
      (footprint "eagle-import:R0603")
      (libsource (lib "eagle-import") (part "R-US_R0603"))
    )
    (comp (ref "R43")
      (value "50k")
      (footprint "eagle-import:R0603")
      (libsource (lib "eagle-import") (part "R-US_R0603"))
    )
    (comp (ref "R44")
      (value "50k")
      (footprint "eagle-import:R0603")
      (libsource (lib "eagle-import") (part "R-US_R0603"))
    )
    (comp (ref "R45")
      (value "50k")
      (footprint "eagle-import:R0603")
      (libsource (lib "eagle-import") (part "R-US_R0603"))
    )
    (comp (ref "R46")
      (value "50k")
      (footprint "eagle-import:R0603")
      (libsource (lib "eagle-import") (part "R-US_R0603"))
    )
    (comp (ref "R47")
      (value "50k")
      (footprint "eagle-import:R0603")
      (libsource (lib "eagle-import") (part "R-US_R0603"))
    )
    (comp (ref "R48")
      (value "50k")
      (footprint "eagle-import:R0603")
      (libsource (lib "eagle-import") (part "R-US_R0603"))
    )
    (comp (ref "R49")
      (value "50k")
      (footprint "eagle-import:R0603")
      (libsource (lib "eagle-import") (part "R-US_R0603"))
    )
    (comp (ref "R50")
      (value "50k")
      (footprint "eagle-import:R0603")
      (libsource (lib "eagle-import") (part "R-US_R0603"))
    )
    (comp (ref "R51")
      (value "50k")
      (footprint "eagle-import:R0603")
      (libsource (lib "eagle-import") (part "R-US_R0603"))
    )
    (comp (ref "R52")
      (value "50k")
      (footprint "eagle-import:R0603")
      (libsource (lib "eagle-import") (part "R-US_R0603"))
    )
    (comp (ref "R53")
      (value "50k")
      (footprint "eagle-import:R0603")
      (libsource (lib "eagle-import") (part "R-US_R0603"))
    )
    (comp (ref "R54")
      (value "50k")
      (footprint "eagle-import:R0603")
      (libsource (lib "eagle-import") (part "R-US_R0603"))
    )
    (comp (ref "R55")
      (value "50k")
      (footprint "eagle-import:R0603")
      (libsource (lib "eagle-import") (part "R-US_R0603"))
    )
    (comp (ref "R56")
      (value "50k")
      (footprint "eagle-import:R0603")
      (libsource (lib "eagle-import") (part "R-US_R0603"))
    )
    (comp (ref "R57")
      (value "50k")
      (footprint "eagle-import:R0603")
      (libsource (lib "eagle-import") (part "R-US_R0603"))
    )
    (comp (ref "R66")
      (value "100k")
      (footprint "eagle-import:R0603")
      (libsource (lib "eagle-import") (part "R-US_R0603"))
    )
    (comp (ref "R67")
      (value "100k")
      (footprint "eagle-import:R0603")
      (libsource (lib "eagle-import") (part "R-US_R0603"))
    )
    (comp (ref "R68")
      (value "1k")
      (footprint "eagle-import:R0603")
      (libsource (lib "eagle-import") (part "R-US_R0603"))
    )
    (comp (ref "R69")
      (value "1k")
      (footprint "eagle-import:R0603")
      (libsource (lib "eagle-import") (part "R-US_R0603"))
    )
    (comp (ref "R73")
      (value "1k")
      (footprint "eagle-import:R0603")
      (libsource (lib "eagle-import") (part "R-US_R0603"))
    )
    (comp (ref "R74")
      (value "1k")
      (footprint "eagle-import:R0603")
      (libsource (lib "eagle-import") (part "R-US_R0603"))
    )
    (comp (ref "R88")
      (value "0")
      (footprint "eagle-import:R0603")
      (libsource (lib "eagle-import") (part "R-US_R0603"))
    )
    (comp (ref "R89")
      (value "0")
      (footprint "eagle-import:R0603")
      (libsource (lib "eagle-import") (part "R-US_R0603"))
    )
    (comp (ref "R91")
      (value "0")
      (footprint "eagle-import:R0603")
      (libsource (lib "eagle-import") (part "R-US_R0603"))
    )
    (comp (ref "RPIA_RUN")
      (value "Amber")
      (footprint "eagle-import:SML0603")
      (fields (field (name "MPN") "SM0805AC"))
      (libsource (lib "eagle-import") (part "LEDSML0603"))
    )
    (comp (ref "RPIA_SD_SEL")
      (value "red")
      (footprint "eagle-import:SML0603")
      (fields (field (name "MPN") "LTST-C190CKT"))
      (libsource (lib "eagle-import") (part "LEDSML0603"))
    )
    (comp (ref "RPIB_RUN")
      (value "Amber")
      (footprint "eagle-import:SML0603")
      (fields (field (name "MPN") "SM0805AC"))
      (libsource (lib "eagle-import") (part "LEDSML0603"))
    )
    (comp (ref "RPIB_SD_SEL")
      (value "red")
      (footprint "eagle-import:SML0603")
      (fields (field (name "MPN") "LTST-C190CKT"))
      (libsource (lib "eagle-import") (part "LEDSML0603"))
    )
    (comp (ref "U4")
      (value "FSSD06-MLP")
      (footprint "eagle-import:FSSD06-MLP")
      (fields (field (name "MPN") "FSSD06BQX"))
      (libsource (lib "eagle-import") (part "FSSD06-MLP"))
    )
    (comp (ref "U5")
      (value "ADM6316")
      (footprint "eagle-import:AMD6316")
      (fields (field (name "MPN") "ADM6320CZ29ARJZ-R7"))
      (libsource (lib "eagle-import") (part "AMD6316"))
    )
    (comp (ref "U6")
      (value "ADM6316")
      (footprint "eagle-import:AMD6316")
      (fields (field (name "MPN") "ADM6320CZ29ARJZ-R7"))
      (libsource (lib "eagle-import") (part "AMD6316"))
    )
    (comp (ref "U11")
      (value "FSSD06-MLP")
      (footprint "eagle-import:FSSD06-MLP")
      (fields (field (name "MPN") "FSSD06BQX"))
      (libsource (lib "eagle-import") (part "FSSD06-MLP"))
    )
    (comp (ref "U13")
      (value "FSSD06-MLP")
      (footprint "eagle-import:FSSD06-MLP")
      (fields (field (name "MPN") "FSSD06BQX"))
      (libsource (lib "eagle-import") (part "FSSD06-MLP"))
    )
    (comp (ref "U14")
      (value "FSSD06-MLP")
      (footprint "eagle-import:FSSD06-MLP")
      (fields (field (name "MPN") "FSSD06BQX"))
      (libsource (lib "eagle-import") (part "FSSD06-MLP"))
    )
    (comp (ref "WD_A_MR")
      (value "TPTP18SQ")
      (footprint "eagle-import:TP18SQ")
      (libsource (lib "eagle-import") (part "TPTP18SQ"))
    )
    (comp (ref "WD_A_WDI")
      (value "TPB1,27")
      (footprint "eagle-import:B1,27")
      (libsource (lib "eagle-import") (part "TPB1,27"))
    )
    (comp (ref "WD_B_MR")
      (value "TPTP18SQ")
      (footprint "eagle-import:TP18SQ")
      (libsource (lib "eagle-import") (part "TPTP18SQ"))
    )
    (comp (ref "WD_B_WDI")
      (value "TPB1,27")
      (footprint "eagle-import:B1,27")
      (libsource (lib "eagle-import") (part "TPB1,27"))
    )
    (comp (ref "WD_RES_A")
      (value "TPTP18SQ")
      (footprint "eagle-import:TP18SQ")
      (libsource (lib "eagle-import") (part "TPTP18SQ"))
    )
    (comp (ref "WD_RES_B")
      (value "TPTP18SQ")
      (footprint "eagle-import:TP18SQ")
      (libsource (lib "eagle-import") (part "TPTP18SQ"))
    )
    (comp (ref "W_RES_A")
      (value "TP_HRWN")
      (footprint "eagle-import:TP_HRWN")
      (fields (field (name "MPN") "S2751-46R") (field (name "MPN_1") "S2751-46R"))
      (libsource (lib "eagle-import") (part "TP_HRWN"))
    )
    (comp (ref "W_RES_B")
      (value "TP_HRWN")
      (footprint "eagle-import:TP_HRWN")
      (fields (field (name "MPN") "S2751-46R") (field (name "MPN_1") "S2751-46R"))
      (libsource (lib "eagle-import") (part "TP_HRWN"))
    )
    (comp (ref "X1")
      (value "1040310811")
      (footprint "eagle-import:1040310811")
      (libsource (lib "eagle-import") (part "1040310811"))
    )
    (comp (ref "X2")
      (value "1040310811")
      (footprint "eagle-import:1040310811")
      (libsource (lib "eagle-import") (part "1040310811"))
    )
    (comp (ref "X5")
      (value "1040310811")
      (footprint "eagle-import:1040310811")
      (libsource (lib "eagle-import") (part "1040310811"))
    )
    (comp (ref "X6")
      (value "1040310811")
      (footprint "eagle-import:1040310811")
      (libsource (lib "eagle-import") (part "1040310811"))
    )
  )
  (nets
    (net (code "1") (name "+1V8_RPIA") (class "Default")
      (node (ref "1V8_RPIA") (pin "TP") (pinfunction "TP_TP") (pintype "input"))
      (node (ref "C12") (pin "1") (pinfunction "1_1") (pintype "passive"))
      (node (ref "C31") (pin "1") (pinfunction "1_1") (pintype "passive"))
      (node (ref "C57") (pin "1") (pinfunction "1_1") (pintype "passive"))
      (node (ref "C66") (pin "1") (pinfunction "1_1") (pintype "passive"))
      (node (ref "C79") (pin "1") (pinfunction "1_1") (pintype "passive"))
      (node (ref "C80") (pin "1") (pinfunction "1_1") (pintype "passive"))
      (node (ref "L1") (pin "2") (pinfunction "2_2") (pintype "passive"))
      (node (ref "R64") (pin "2") (pinfunction "2_2") (pintype "passive"))
      (node (ref "U19") (pin "5") (pinfunction "VCC_5") (pintype "bidirectional"))
      (node (ref "U2") (pin "5") (pinfunction "VCC_5") (pintype "bidirectional"))
      (node (ref "U20") (pin "183") (pinfunction "1V8_183") (pintype "bidirectional"))
      (node (ref "U20") (pin "184") (pinfunction "1V8_184") (pintype "bidirectional"))
      (node (ref "U20") (pin "185") (pinfunction "1V8_185") (pintype "bidirectional"))
      (node (ref "U20") (pin "186") (pinfunction "1V8_186") (pintype "bidirectional"))
      (node (ref "U22") (pin "5") (pinfunction "VCC_5") (pintype "bidirectional"))
      (node (ref "U3") (pin "13") (pinfunction "VDD_13") (pintype "power_in"))
      (node (ref "U3") (pin "8") (pinfunction "VDDIO_8") (pintype "power_in"))
      (node (ref "U7") (pin "5") (pinfunction "FB_5") (pintype "input"))
    )
    (net (code "2") (name "+1V8_RPIB") (class "Default")
      (node (ref "1V8_RPIB") (pin "TP") (pinfunction "TP_TP") (pintype "input"))
      (node (ref "C15") (pin "1") (pinfunction "1_1") (pintype "passive"))
      (node (ref "C71") (pin "1") (pinfunction "1_1") (pintype "passive"))
      (node (ref "C81") (pin "1") (pinfunction "1_1") (pintype "passive"))
      (node (ref "C82") (pin "1") (pinfunction "1_1") (pintype "passive"))
      (node (ref "C88") (pin "1") (pinfunction "1_1") (pintype "passive"))
      (node (ref "C89") (pin "1") (pinfunction "1_1") (pintype "passive"))
      (node (ref "L2") (pin "2") (pinfunction "2_2") (pintype "passive"))
      (node (ref "R65") (pin "2") (pinfunction "2_2") (pintype "passive"))
      (node (ref "U1") (pin "13") (pinfunction "VDD_13") (pintype "power_in"))
      (node (ref "U1") (pin "8") (pinfunction "VDDIO_8") (pintype "power_in"))
      (node (ref "U15") (pin "5") (pinfunction "FB_5") (pintype "input"))
      (node (ref "U21") (pin "183") (pinfunction "1V8_183") (pintype "bidirectional"))
      (node (ref "U21") (pin "184") (pinfunction "1V8_184") (pintype "bidirectional"))
      (node (ref "U21") (pin "185") (pinfunction "1V8_185") (pintype "bidirectional"))
      (node (ref "U21") (pin "186") (pinfunction "1V8_186") (pintype "bidirectional"))
      (node (ref "U23") (pin "5") (pinfunction "VCC_5") (pintype "bidirectional"))
      (node (ref "U24") (pin "5") (pinfunction "VCC_5") (pintype "bidirectional"))
      (node (ref "U25") (pin "5") (pinfunction "VCC_5") (pintype "bidirectional"))
    )
    (net (code "3") (name "+3V3") (class "Default")
      (node (ref "+3V3_VIN") (pin "P$1") (pinfunction "P1_P$1") (pintype "bidirectional"))
      (node (ref "C32") (pin "1") (pinfunction "1_1") (pintype "passive"))
      (node (ref "C33") (pin "1") (pinfunction "1_1") (pintype "passive"))
      (node (ref "C34") (pin "1") (pinfunction "1_1") (pintype "passive"))
      (node (ref "C35") (pin "1") (pinfunction "1_1") (pintype "passive"))
      (node (ref "C40") (pin "1") (pinfunction "1_1") (pintype "passive"))
      (node (ref "C41") (pin "1") (pinfunction "1_1") (pintype "passive"))
      (node (ref "C42") (pin "1") (pinfunction "1_1") (pintype "passive"))
      (node (ref "C43") (pin "1") (pinfunction "1_1") (pintype "passive"))
      (node (ref "C44") (pin "1") (pinfunction "1_1") (pintype "passive"))
      (node (ref "C45") (pin "1") (pinfunction "1_1") (pintype "passive"))
      (node (ref "C46") (pin "1") (pinfunction "1_1") (pintype "passive"))
      (node (ref "C47") (pin "1") (pinfunction "1_1") (pintype "passive"))
      (node (ref "C48") (pin "1") (pinfunction "1_1") (pintype "passive"))
      (node (ref "C51") (pin "1") (pinfunction "1_1") (pintype "passive"))
      (node (ref "C52") (pin "1") (pinfunction "1_1") (pintype "passive"))
      (node (ref "C6") (pin "1") (pinfunction "1_1") (pintype "passive"))
      (node (ref "C77") (pin "1") (pinfunction "1_1") (pintype "passive"))
      (node (ref "C78") (pin "1") (pinfunction "1_1") (pintype "passive"))
      (node (ref "C8") (pin "1") (pinfunction "1_1") (pintype "passive"))
      (node (ref "C83") (pin "1") (pinfunction "1_1") (pintype "passive"))
      (node (ref "C84") (pin "1") (pinfunction "1_1") (pintype "passive"))
      (node (ref "C85") (pin "1") (pinfunction "1_1") (pintype "passive"))
      (node (ref "C86") (pin "1") (pinfunction "1_1") (pintype "passive"))
      (node (ref "C90") (pin "1") (pinfunction "1_1") (pintype "passive"))
      (node (ref "H2-CONNECTOR1") (pin "27") (pinfunction "27_27") (pintype "bidirectional"))
      (node (ref "H2-CONNECTOR1") (pin "28") (pinfunction "28_28") (pintype "bidirectional"))
      (node (ref "IC7") (pin "10") (pinfunction "PRE_10") (pintype "input"))
      (node (ref "IC7") (pin "14") (pinfunction "CLR_14") (pintype "input"))
      (node (ref "IC7") (pin "15") (pinfunction "CLR_15") (pintype "input"))
      (node (ref "IC7") (pin "4") (pinfunction "PRE_4") (pintype "input"))
      (node (ref "R1") (pin "2") (pinfunction "2_2") (pintype "passive"))
      (node (ref "R19") (pin "2") (pinfunction "2_2") (pintype "passive"))
      (node (ref "R20") (pin "2") (pinfunction "2_2") (pintype "passive"))
      (node (ref "R23") (pin "2") (pinfunction "2_2") (pintype "passive"))
      (node (ref "R25") (pin "2") (pinfunction "2_2") (pintype "passive"))
      (node (ref "R27") (pin "2") (pinfunction "2_2") (pintype "passive"))
      (node (ref "R29") (pin "2") (pinfunction "2_2") (pintype "passive"))
      (node (ref "R39") (pin "2") (pinfunction "2_2") (pintype "passive"))
      (node (ref "R4") (pin "2") (pinfunction "2_2") (pintype "passive"))
      (node (ref "R40") (pin "2") (pinfunction "2_2") (pintype "passive"))
      (node (ref "R5") (pin "2") (pinfunction "2_2") (pintype "passive"))
      (node (ref "R6") (pin "2") (pinfunction "2_2") (pintype "passive"))
      (node (ref "R66") (pin "2") (pinfunction "2_2") (pintype "passive"))
      (node (ref "R67") (pin "2") (pinfunction "2_2") (pintype "passive"))
      (node (ref "R7") (pin "2") (pinfunction "2_2") (pintype "passive"))
      (node (ref "R71") (pin "2") (pinfunction "2_2") (pintype "passive"))
      (node (ref "R72") (pin "2") (pinfunction "2_2") (pintype "passive"))
      (node (ref "R75") (pin "2") (pinfunction "2_2") (pintype "passive"))
      (node (ref "R79") (pin "2") (pinfunction "2_2") (pintype "passive"))
      (node (ref "R83") (pin "2") (pinfunction "2_2") (pintype "passive"))
      (node (ref "R84") (pin "2") (pinfunction "2_2") (pintype "passive"))
      (node (ref "R85") (pin "1") (pinfunction "1_1") (pintype "passive"))
      (node (ref "R86") (pin "2") (pinfunction "2_2") (pintype "passive"))
      (node (ref "S10") (pin "1") (pinfunction "VCC_1") (pintype "bidirectional"))
      (node (ref "S2") (pin "5") (pinfunction "IN_5") (pintype "bidirectional"))
      (node (ref "S3") (pin "5") (pinfunction "IN_5") (pintype "bidirectional"))
      (node (ref "S4") (pin "1") (pinfunction "VCC_1") (pintype "bidirectional"))
      (node (ref "S5") (pin "1") (pinfunction "VCC_1") (pintype "bidirectional"))
      (node (ref "S6") (pin "1") (pinfunction "VCC_1") (pintype "bidirectional"))
      (node (ref "S7") (pin "1") (pinfunction "VCC_1") (pintype "bidirectional"))
      (node (ref "S8") (pin "1") (pinfunction "VCC_1") (pintype "bidirectional"))
      (node (ref "S9") (pin "1") (pinfunction "VCC_1") (pintype "bidirectional"))
      (node (ref "U16") (pin "8") (pinfunction "EN_8") (pintype "input"))
      (node (ref "U17") (pin "8") (pinfunction "EN_8") (pintype "input"))
      (node (ref "U5") (pin "5") (pinfunction "VCC_5") (pintype "bidirectional"))
      (node (ref "U6") (pin "5") (pinfunction "VCC_5") (pintype "bidirectional"))
      (node (ref "U8") (pin "10") (pinfunction "VDDA33_10") (pintype "power_in"))
      (node (ref "U8") (pin "24") (pinfunction "VDD33CR_24") (pintype "power_in"))
      (node (ref "U8") (pin "44") (pinfunction "VBUS_DET_44") (pintype "bidirectional"))
      (node (ref "U8") (pin "46") (pinfunction "VDD33_46") (pintype "power_in"))
      (node (ref "U8") (pin "5") (pinfunction "VDDA33_5") (pintype "power_in"))
      (node (ref "U8") (pin "52") (pinfunction "VDDA33_52") (pintype "power_in"))
      (node (ref "U8") (pin "57") (pinfunction "VDDA33_57") (pintype "power_in"))
      (node (ref "U8") (pin "64") (pinfunction "VDD33PLL_64") (pintype "power_in"))
      (node (ref "U9") (pin "5") (pinfunction "VCC_5") (pintype "bidirectional"))
    )
    (net (code "4") (name "+3V3_RPIA") (class "Default")
      (node (ref "3V3_RPIA") (pin "P$1") (pinfunction "P1_P$1") (pintype "bidirectional"))
      (node (ref "C10") (pin "1") (pinfunction "1_1") (pintype "passive"))
      (node (ref "C16") (pin "1") (pinfunction "1_1") (pintype "passive"))
      (node (ref "C17") (pin "1") (pinfunction "1_1") (pintype "passive"))
      (node (ref "C25") (pin "1") (pinfunction "1_1") (pintype "passive"))
      (node (ref "C28") (pin "1") (pinfunction "1_1") (pintype "passive"))
      (node (ref "C29") (pin "1") (pinfunction "1_1") (pintype "passive"))
      (node (ref "C60") (pin "1") (pinfunction "1_1") (pintype "passive"))
      (node (ref "C61") (pin "1") (pinfunction "1_1") (pintype "passive"))
      (node (ref "C65") (pin "1") (pinfunction "1_1") (pintype "passive"))
      (node (ref "C67") (pin "1") (pinfunction "1_1") (pintype "passive"))
      (node (ref "C68") (pin "1") (pinfunction "1_1") (pintype "passive"))
      (node (ref "C75") (pin "1") (pinfunction "1_1") (pintype "passive"))
      (node (ref "C76") (pin "1") (pinfunction "1_1") (pintype "passive"))
      (node (ref "L4") (pin "2") (pinfunction "2_2") (pintype "passive"))
      (node (ref "R34") (pin "2") (pinfunction "2_2") (pintype "passive"))
      (node (ref "R35") (pin "2") (pinfunction "2_2") (pintype "passive"))
      (node (ref "R36") (pin "2") (pinfunction "2_2") (pintype "passive"))
      (node (ref "R41") (pin "2") (pinfunction "2_2") (pintype "passive"))
      (node (ref "R42") (pin "2") (pinfunction "2_2") (pintype "passive"))
      (node (ref "R48") (pin "2") (pinfunction "2_2") (pintype "passive"))
      (node (ref "R49") (pin "2") (pinfunction "2_2") (pintype "passive"))
      (node (ref "R50") (pin "2") (pinfunction "2_2") (pintype "passive"))
      (node (ref "R51") (pin "2") (pinfunction "2_2") (pintype "passive"))
      (node (ref "R52") (pin "2") (pinfunction "2_2") (pintype "passive"))
      (node (ref "R63") (pin "2") (pinfunction "2_2") (pintype "passive"))
      (node (ref "R76") (pin "2") (pinfunction "2_2") (pintype "passive"))
      (node (ref "U11") (pin "15") (pinfunction "VDDC2_15") (pintype "bidirectional"))
      (node (ref "U11") (pin "22") (pinfunction "VDDC1_22") (pintype "bidirectional"))
      (node (ref "U11") (pin "6") (pinfunction "VDDH_6") (pintype "bidirectional"))
      (node (ref "U14") (pin "15") (pinfunction "VDDC2_15") (pintype "bidirectional"))
      (node (ref "U14") (pin "22") (pinfunction "VDDC1_22") (pintype "bidirectional"))
      (node (ref "U14") (pin "6") (pinfunction "VDDH_6") (pintype "bidirectional"))
      (node (ref "U20") (pin "191") (pinfunction "3V3_191") (pintype "bidirectional"))
      (node (ref "U20") (pin "192") (pinfunction "3V3_192") (pintype "bidirectional"))
      (node (ref "U20") (pin "193") (pinfunction "3V3_193") (pintype "bidirectional"))
      (node (ref "U20") (pin "194") (pinfunction "3V3_194") (pintype "bidirectional"))
      (node (ref "U20") (pin "197") (pinfunction "VBAT_197") (pintype "bidirectional"))
      (node (ref "U20") (pin "198") (pinfunction "VBAT_198") (pintype "bidirectional"))
      (node (ref "U20") (pin "199") (pinfunction "VBAT_199") (pintype "bidirectional"))
      (node (ref "U20") (pin "2") (pinfunction "EMMC_DISABLE_N_2") (pintype "bidirectional"))
      (node (ref "U20") (pin "200") (pinfunction "VBAT_200") (pintype "bidirectional"))
      (node (ref "U20") (pin "39") (pinfunction "GPIO0-27_VDD_39") (pintype "bidirectional"))
      (node (ref "U20") (pin "4") (pinfunction "SDX_VDD_4") (pintype "bidirectional"))
      (node (ref "U20") (pin "40") (pinfunction "GPIO0-27_VDD_40") (pintype "bidirectional"))
      (node (ref "U20") (pin "41") (pinfunction "GPIO28-45_VDD_41") (pintype "bidirectional"))
      (node (ref "U20") (pin "42") (pinfunction "GPIO28-45_VDD_42") (pintype "bidirectional"))
      (node (ref "U7") (pin "1") (pinfunction "MODE_SYNC_1") (pintype "input"))
      (node (ref "U7") (pin "2") (pinfunction "VIN_2") (pintype "power_in"))
      (node (ref "U7") (pin "8") (pinfunction "EN_8") (pintype "input"))
      (node (ref "X1") (pin "4") (pinfunction "VDD_4") (pintype "bidirectional"))
      (node (ref "X2") (pin "4") (pinfunction "VDD_4") (pintype "bidirectional"))
    )
    (net (code "5") (name "+3V3_RPIB") (class "Default")
      (node (ref "3V3_RPIB") (pin "P$1") (pinfunction "P1_P$1") (pintype "bidirectional"))
      (node (ref "C13") (pin "1") (pinfunction "1_1") (pintype "passive"))
      (node (ref "C18") (pin "1") (pinfunction "1_1") (pintype "passive"))
      (node (ref "C22") (pin "1") (pinfunction "1_1") (pintype "passive"))
      (node (ref "C23") (pin "1") (pinfunction "1_1") (pintype "passive"))
      (node (ref "C24") (pin "1") (pinfunction "1_1") (pintype "passive"))
      (node (ref "C55") (pin "1") (pinfunction "1_1") (pintype "passive"))
      (node (ref "C56") (pin "1") (pinfunction "1_1") (pintype "passive"))
      (node (ref "C69") (pin "1") (pinfunction "1_1") (pintype "passive"))
      (node (ref "C70") (pin "1") (pinfunction "1_1") (pintype "passive"))
      (node (ref "C72") (pin "1") (pinfunction "1_1") (pintype "passive"))
      (node (ref "C73") (pin "1") (pinfunction "1_1") (pintype "passive"))
      (node (ref "C91") (pin "1") (pinfunction "1_1") (pintype "passive"))
      (node (ref "L3") (pin "2") (pinfunction "2_2") (pintype "passive"))
      (node (ref "R43") (pin "2") (pinfunction "2_2") (pintype "passive"))
      (node (ref "R44") (pin "2") (pinfunction "2_2") (pintype "passive"))
      (node (ref "R45") (pin "2") (pinfunction "2_2") (pintype "passive"))
      (node (ref "R46") (pin "2") (pinfunction "2_2") (pintype "passive"))
      (node (ref "R47") (pin "2") (pinfunction "2_2") (pintype "passive"))
      (node (ref "R53") (pin "2") (pinfunction "2_2") (pintype "passive"))
      (node (ref "R54") (pin "2") (pinfunction "2_2") (pintype "passive"))
      (node (ref "R55") (pin "2") (pinfunction "2_2") (pintype "passive"))
      (node (ref "R56") (pin "2") (pinfunction "2_2") (pintype "passive"))
      (node (ref "R57") (pin "2") (pinfunction "2_2") (pintype "passive"))
      (node (ref "R62") (pin "2") (pinfunction "2_2") (pintype "passive"))
      (node (ref "R80") (pin "2") (pinfunction "2_2") (pintype "passive"))
      (node (ref "U13") (pin "15") (pinfunction "VDDC2_15") (pintype "bidirectional"))
      (node (ref "U13") (pin "22") (pinfunction "VDDC1_22") (pintype "bidirectional"))
      (node (ref "U13") (pin "6") (pinfunction "VDDH_6") (pintype "bidirectional"))
      (node (ref "U15") (pin "1") (pinfunction "MODE_SYNC_1") (pintype "input"))
      (node (ref "U15") (pin "2") (pinfunction "VIN_2") (pintype "power_in"))
      (node (ref "U15") (pin "8") (pinfunction "EN_8") (pintype "input"))
      (node (ref "U21") (pin "191") (pinfunction "3V3_191") (pintype "bidirectional"))
      (node (ref "U21") (pin "192") (pinfunction "3V3_192") (pintype "bidirectional"))
      (node (ref "U21") (pin "193") (pinfunction "3V3_193") (pintype "bidirectional"))
      (node (ref "U21") (pin "194") (pinfunction "3V3_194") (pintype "bidirectional"))
      (node (ref "U21") (pin "197") (pinfunction "VBAT_197") (pintype "bidirectional"))
      (node (ref "U21") (pin "198") (pinfunction "VBAT_198") (pintype "bidirectional"))
      (node (ref "U21") (pin "199") (pinfunction "VBAT_199") (pintype "bidirectional"))
      (node (ref "U21") (pin "2") (pinfunction "EMMC_DISABLE_N_2") (pintype "bidirectional"))
      (node (ref "U21") (pin "200") (pinfunction "VBAT_200") (pintype "bidirectional"))
      (node (ref "U21") (pin "39") (pinfunction "GPIO0-27_VDD_39") (pintype "bidirectional"))
      (node (ref "U21") (pin "4") (pinfunction "SDX_VDD_4") (pintype "bidirectional"))
      (node (ref "U21") (pin "40") (pinfunction "GPIO0-27_VDD_40") (pintype "bidirectional"))
      (node (ref "U21") (pin "41") (pinfunction "GPIO28-45_VDD_41") (pintype "bidirectional"))
      (node (ref "U21") (pin "42") (pinfunction "GPIO28-45_VDD_42") (pintype "bidirectional"))
      (node (ref "U4") (pin "15") (pinfunction "VDDC2_15") (pintype "bidirectional"))
      (node (ref "U4") (pin "22") (pinfunction "VDDC1_22") (pintype "bidirectional"))
      (node (ref "U4") (pin "6") (pinfunction "VDDH_6") (pintype "bidirectional"))
      (node (ref "X5") (pin "4") (pinfunction "VDD_4") (pintype "bidirectional"))
      (node (ref "X6") (pin "4") (pinfunction "VDD_4") (pintype "bidirectional"))
    )
    (net (code "6") (name "+5V") (class "Default")
      (node (ref "+5V_VIN") (pin "P$1") (pinfunction "P1_P$1") (pintype "bidirectional"))
      (node (ref "C20") (pin "1") (pinfunction "1_1") (pintype "passive"))
      (node (ref "C21") (pin "1") (pinfunction "1_1") (pintype "passive"))
      (node (ref "C26") (pin "1") (pinfunction "1_1") (pintype "passive"))
      (node (ref "C27") (pin "1") (pinfunction "1_1") (pintype "passive"))
      (node (ref "C4") (pin "1") (pinfunction "1_1") (pintype "passive"))
      (node (ref "C50") (pin "1") (pinfunction "1_1") (pintype "passive"))
      (node (ref "C58") (pin "1") (pinfunction "1_1") (pintype "passive"))
      (node (ref "C59") (pin "1") (pinfunction "1_1") (pintype "passive"))
      (node (ref "C62") (pin "1") (pinfunction "1_1") (pintype "passive"))
      (node (ref "C64") (pin "1") (pinfunction "1_1") (pintype "passive"))
      (node (ref "C74") (pin "1") (pinfunction "1_1") (pintype "passive"))
      (node (ref "D1") (pin "4") (pinfunction "VCC_4") (pintype "bidirectional"))
      (node (ref "D2") (pin "4") (pinfunction "VCC_4") (pintype "bidirectional"))
      (node (ref "D3") (pin "4") (pinfunction "VCC_4") (pintype "bidirectional"))
      (node (ref "IC10") (pin "20") (pinfunction "VCC_20") (pintype "power_in"))
      (node (ref "IC3") (pin "20") (pinfunction "VCC_20") (pintype "power_in"))
      (node (ref "IC3") (pin "4") (pinfunction "VCCIO_4") (pintype "power_in"))
      (node (ref "IC9") (pin "1") (pinfunction "VCC_1") (pintype "bidirectional"))
      (node (ref "JP4") (pin "2") (pinfunction "2_2") (pintype "passive"))
      (node (ref "R11") (pin "1") (pinfunction "1_1") (pintype "passive"))
      (node (ref "R12") (pin "1") (pinfunction "1_1") (pintype "passive"))
      (node (ref "R30") (pin "1") (pinfunction "1_1") (pintype "passive"))
      (node (ref "R31") (pin "1") (pinfunction "1_1") (pintype "passive"))
      (node (ref "R32") (pin "1") (pinfunction "1_1") (pintype "passive"))
      (node (ref "R33") (pin "1") (pinfunction "1_1") (pintype "passive"))
      (node (ref "RTC_VIN") (pin "TP") (pinfunction "TP_TP") (pintype "input"))
      (node (ref "S1") (pin "5") (pinfunction "IN_5") (pintype "bidirectional"))
      (node (ref "U10") (pin "5") (pinfunction "VCC_5") (pintype "bidirectional"))
      (node (ref "U12") (pin "8") (pinfunction "VCC_8") (pintype "power_in"))
      (node (ref "U16") (pin "1") (pinfunction "MODE_SYNC_1") (pintype "input"))
      (node (ref "U16") (pin "2") (pinfunction "VIN_2") (pintype "power_in"))
      (node (ref "U17") (pin "1") (pinfunction "MODE_SYNC_1") (pintype "input"))
      (node (ref "U17") (pin "2") (pinfunction "VIN_2") (pintype "power_in"))
    )
    (net (code "7") (name "3V3_SW_1") (class "Default")
      (node (ref "H2-CONNECTOR1") (pin "18") (pinfunction "18_18") (pintype "bidirectional"))
    )
    (net (code "8") (name "3V3_SW_2") (class "Default")
      (node (ref "ANT_1") (pin "TP") (pinfunction "TP_TP") (pintype "input"))
      (node (ref "H2-CONNECTOR1") (pin "19") (pinfunction "19_19") (pintype "bidirectional"))
      (node (ref "J9") (pin "1") (pinfunction "1_1") (pintype "passive"))
    )
    (net (code "9") (name "3V3_SW_3") (class "Default")
      (node (ref "GPS_1") (pin "TP") (pinfunction "TP_TP") (pintype "input"))
      (node (ref "H2-CONNECTOR1") (pin "20") (pinfunction "20_20") (pintype "bidirectional"))
      (node (ref "J10") (pin "1") (pinfunction "1_1") (pintype "passive"))
    )
    (net (code "10") (name "5V_BUS") (class "Default")
      (node (ref "H2-CONNECTOR1") (pin "25") (pinfunction "25_25") (pintype "bidirectional"))
      (node (ref "H2-CONNECTOR1") (pin "26") (pinfunction "26_26") (pintype "bidirectional"))
      (node (ref "J3") (pin "1") (pinfunction "1_1") (pintype "bidirectional"))
      (node (ref "JP4") (pin "3") (pinfunction "3_3") (pintype "passive"))
      (node (ref "LST_1") (pin "TP") (pinfunction "TP_TP") (pintype "input"))
    )
    (net (code "11") (name "5V_SW_1") (class "Default")
      (node (ref "H2-CONNECTOR1") (pin "13") (pinfunction "13_13") (pintype "bidirectional"))
    )
    (net (code "12") (name "5V_SW_2") (class "Default")
      (node (ref "H2-CONNECTOR1") (pin "15") (pinfunction "15_15") (pintype "bidirectional"))
      (node (ref "JP4") (pin "1") (pinfunction "1_1") (pintype "passive"))
    )
    (net (code "13") (name "5V_SW_3") (class "Default")
      (node (ref "H2-CONNECTOR1") (pin "16") (pinfunction "16_16") (pintype "bidirectional"))
    )
    (net (code "14") (name "5V_USB_CHG") (class "Default")
      (node (ref "H1-CONNECTOR1") (pin "32") (pinfunction "32_32") (pintype "bidirectional"))
    )
    (net (code "15") (name "12V_BUS") (class "Default")
      (node (ref "BB_1") (pin "TP") (pinfunction "TP_TP") (pintype "input"))
      (node (ref "H2-CONNECTOR1") (pin "23") (pinfunction "23_23") (pintype "bidirectional"))
      (node (ref "H2-CONNECTOR1") (pin "24") (pinfunction "24_24") (pintype "bidirectional"))
      (node (ref "J11") (pin "1") (pinfunction "1_1") (pintype "bidirectional"))
    )
    (net (code "16") (name "12V_SW_1") (class "Default")
      (node (ref "H2-CONNECTOR1") (pin "8") (pinfunction "8_8") (pintype "bidirectional"))
      (node (ref "J6") (pin "1") (pinfunction "1_1") (pintype "bidirectional"))
      (node (ref "TILE_1") (pin "TP") (pinfunction "TP_TP") (pintype "input"))
    )
    (net (code "17") (name "12V_SW_2") (class "Default")
      (node (ref "H2-CONNECTOR1") (pin "10") (pinfunction "10_10") (pintype "bidirectional"))
    )
    (net (code "18") (name "BB_BUSY") (class "Default")
      (node (ref "BB_4") (pin "TP") (pinfunction "TP_TP") (pintype "input"))
      (node (ref "J11") (pin "4") (pinfunction "4_4") (pintype "bidirectional"))
      (node (ref "S10") (pin "3") (pinfunction "D+_3") (pintype "bidirectional"))
    )
    (net (code "19") (name "BB_RX") (class "Default")
      (node (ref "BB_3") (pin "TP") (pinfunction "TP_TP") (pintype "input"))
      (node (ref "BB_RX_SHIFT") (pin "P$1") (pinfunction "P1_P$1") (pintype "bidirectional"))
      (node (ref "J11") (pin "3") (pinfunction "3_3") (pintype "bidirectional"))
      (node (ref "U10") (pin "4") (pinfunction "Y_4") (pintype "bidirectional"))
    )
    (net (code "20") (name "BB_TX") (class "Default")
      (node (ref "BB_2") (pin "TP") (pinfunction "TP_TP") (pintype "input"))
      (node (ref "J11") (pin "2") (pinfunction "2_2") (pintype "bidirectional"))
      (node (ref "U9") (pin "2") (pinfunction "A_2") (pintype "bidirectional"))
    )
    (net (code "21") (name "BB_WDG") (class "Default")
      (node (ref "BB_5") (pin "TP") (pinfunction "TP_TP") (pintype "input"))
      (node (ref "J11") (pin "5") (pinfunction "5_5") (pintype "bidirectional"))
      (node (ref "S10") (pin "4") (pinfunction "D-_4") (pintype "bidirectional"))
    )
    (net (code "22") (name "CAM_PWR_EN") (class "Default")
      (node (ref "CAM_EN") (pin "P$1") (pinfunction "P1_P$1") (pintype "bidirectional"))
      (node (ref "S1") (pin "4") (pinfunction "ON/~{ON}_4") (pintype "bidirectional"))
      (node (ref "S2") (pin "4") (pinfunction "ON/~{ON}_4") (pintype "bidirectional"))
      (node (ref "S3") (pin "4") (pinfunction "ON/~{ON}_4") (pintype "bidirectional"))
      (node (ref "U20") (pin "72") (pinfunction "GPIO41_72") (pintype "bidirectional"))
      (node (ref "U21") (pin "72") (pinfunction "GPIO41_72") (pintype "bidirectional"))
    )
    (net (code "23") (name "DN_DEBUG") (class "Default")
      (node (ref "J4") (pin "2") (pinfunction "D-_2") (pintype "passive"))
      (node (ref "U8") (pin "53") (pinfunction "USBDN6_DM/PRT_DIS_M6_53") (pintype "bidirectional"))
    )
    (net (code "24") (name "DN_FLASH") (class "Default")
      (node (ref "J1") (pin "2") (pinfunction "D-_2") (pintype "passive"))
      (node (ref "S5") (pin "8") (pinfunction "HSD2-_8") (pintype "bidirectional"))
    )
    (net (code "25") (name "DP_DEBUG") (class "Default")
      (node (ref "J4") (pin "3") (pinfunction "D+_3") (pintype "passive"))
      (node (ref "U8") (pin "54") (pinfunction "USBDN6_DP/PRT_DIS_P6_54") (pintype "bidirectional"))
    )
    (net (code "26") (name "DP_FLASH") (class "Default")
      (node (ref "J1") (pin "3") (pinfunction "D+_3") (pintype "passive"))
      (node (ref "S5") (pin "9") (pinfunction "HSD2+_9") (pintype "bidirectional"))
    )
    (net (code "27") (name "GND") (class "Default")
      (node (ref "C1") (pin "2") (pinfunction "2_2") (pintype "passive"))
      (node (ref "C10") (pin "2") (pinfunction "2_2") (pintype "passive"))
      (node (ref "C11") (pin "2") (pinfunction "2_2") (pintype "passive"))
      (node (ref "C12") (pin "2") (pinfunction "2_2") (pintype "passive"))
      (node (ref "C13") (pin "2") (pinfunction "2_2") (pintype "passive"))
      (node (ref "C14") (pin "2") (pinfunction "2_2") (pintype "passive"))
      (node (ref "C15") (pin "2") (pinfunction "2_2") (pintype "passive"))
      (node (ref "C17") (pin "2") (pinfunction "2_2") (pintype "passive"))
      (node (ref "C18") (pin "2") (pinfunction "2_2") (pintype "passive"))
      (node (ref "C19") (pin "2") (pinfunction "2_2") (pintype "passive"))
      (node (ref "C2") (pin "2") (pinfunction "2_2") (pintype "passive"))
      (node (ref "C20") (pin "2") (pinfunction "2_2") (pintype "passive"))
      (node (ref "C21") (pin "2") (pinfunction "2_2") (pintype "passive"))
      (node (ref "C22") (pin "2") (pinfunction "2_2") (pintype "passive"))
      (node (ref "C23") (pin "2") (pinfunction "2_2") (pintype "passive"))
      (node (ref "C25") (pin "2") (pinfunction "2_2") (pintype "passive"))
      (node (ref "C26") (pin "2") (pinfunction "2_2") (pintype "passive"))
      (node (ref "C27") (pin "2") (pinfunction "2_2") (pintype "passive"))
      (node (ref "C28") (pin "2") (pinfunction "2_2") (pintype "passive"))
      (node (ref "C29") (pin "2") (pinfunction "2_2") (pintype "passive"))
      (node (ref "C3") (pin "2") (pinfunction "2_2") (pintype "passive"))
      (node (ref "C30") (pin "2") (pinfunction "2_2") (pintype "passive"))
      (node (ref "C31") (pin "2") (pinfunction "2_2") (pintype "passive"))
      (node (ref "C32") (pin "2") (pinfunction "2_2") (pintype "passive"))
      (node (ref "C33") (pin "2") (pinfunction "2_2") (pintype "passive"))
      (node (ref "C34") (pin "2") (pinfunction "2_2") (pintype "passive"))
      (node (ref "C35") (pin "2") (pinfunction "2_2") (pintype "passive"))
      (node (ref "C36") (pin "2") (pinfunction "2_2") (pintype "passive"))
      (node (ref "C37") (pin "1") (pinfunction "1_1") (pintype "passive"))
      (node (ref "C38") (pin "2") (pinfunction "2_2") (pintype "passive"))
      (node (ref "C39") (pin "2") (pinfunction "2_2") (pintype "passive"))
      (node (ref "C4") (pin "2") (pinfunction "2_2") (pintype "passive"))
      (node (ref "C40") (pin "2") (pinfunction "2_2") (pintype "passive"))
      (node (ref "C41") (pin "2") (pinfunction "2_2") (pintype "passive"))
      (node (ref "C42") (pin "2") (pinfunction "2_2") (pintype "passive"))
      (node (ref "C43") (pin "2") (pinfunction "2_2") (pintype "passive"))
      (node (ref "C44") (pin "2") (pinfunction "2_2") (pintype "passive"))
      (node (ref "C45") (pin "2") (pinfunction "2_2") (pintype "passive"))
      (node (ref "C46") (pin "2") (pinfunction "2_2") (pintype "passive"))
      (node (ref "C47") (pin "2") (pinfunction "2_2") (pintype "passive"))
      (node (ref "C48") (pin "2") (pinfunction "2_2") (pintype "passive"))
      (node (ref "C49") (pin "2") (pinfunction "2_2") (pintype "passive"))
      (node (ref "C5") (pin "2") (pinfunction "2_2") (pintype "passive"))
      (node (ref "C50") (pin "2") (pinfunction "2_2") (pintype "passive"))
      (node (ref "C51") (pin "2") (pinfunction "2_2") (pintype "passive"))
      (node (ref "C52") (pin "2") (pinfunction "2_2") (pintype "passive"))
      (node (ref "C53") (pin "2") (pinfunction "2_2") (pintype "passive"))
      (node (ref "C54") (pin "1") (pinfunction "1_1") (pintype "passive"))
      (node (ref "C55") (pin "2") (pinfunction "2_2") (pintype "passive"))
      (node (ref "C56") (pin "2") (pinfunction "2_2") (pintype "passive"))
      (node (ref "C57") (pin "2") (pinfunction "2_2") (pintype "passive"))
      (node (ref "C58") (pin "2") (pinfunction "2_2") (pintype "passive"))
      (node (ref "C59") (pin "2") (pinfunction "2_2") (pintype "passive"))
      (node (ref "C6") (pin "2") (pinfunction "2_2") (pintype "passive"))
      (node (ref "C60") (pin "2") (pinfunction "2_2") (pintype "passive"))
      (node (ref "C61") (pin "2") (pinfunction "2_2") (pintype "passive"))
      (node (ref "C62") (pin "2") (pinfunction "2_2") (pintype "passive"))
      (node (ref "C63") (pin "2") (pinfunction "2_2") (pintype "passive"))
      (node (ref "C64") (pin "2") (pinfunction "2_2") (pintype "passive"))
      (node (ref "C65") (pin "2") (pinfunction "2_2") (pintype "passive"))
      (node (ref "C66") (pin "2") (pinfunction "2_2") (pintype "passive"))
      (node (ref "C67") (pin "2") (pinfunction "2_2") (pintype "passive"))
      (node (ref "C68") (pin "2") (pinfunction "2_2") (pintype "passive"))
      (node (ref "C69") (pin "2") (pinfunction "2_2") (pintype "passive"))
      (node (ref "C7") (pin "2") (pinfunction "2_2") (pintype "passive"))
      (node (ref "C70") (pin "2") (pinfunction "2_2") (pintype "passive"))
      (node (ref "C71") (pin "2") (pinfunction "2_2") (pintype "passive"))
      (node (ref "C72") (pin "2") (pinfunction "2_2") (pintype "passive"))
      (node (ref "C73") (pin "2") (pinfunction "2_2") (pintype "passive"))
      (node (ref "C74") (pin "2") (pinfunction "2_2") (pintype "passive"))
      (node (ref "C75") (pin "2") (pinfunction "2_2") (pintype "passive"))
      (node (ref "C76") (pin "2") (pinfunction "2_2") (pintype "passive"))
      (node (ref "C77") (pin "2") (pinfunction "2_2") (pintype "passive"))
      (node (ref "C78") (pin "2") (pinfunction "2_2") (pintype "passive"))
      (node (ref "C79") (pin "2") (pinfunction "2_2") (pintype "passive"))
      (node (ref "C8") (pin "2") (pinfunction "2_2") (pintype "passive"))
      (node (ref "C80") (pin "2") (pinfunction "2_2") (pintype "passive"))
      (node (ref "C81") (pin "2") (pinfunction "2_2") (pintype "passive"))
      (node (ref "C82") (pin "2") (pinfunction "2_2") (pintype "passive"))
      (node (ref "C83") (pin "2") (pinfunction "2_2") (pintype "passive"))
      (node (ref "C84") (pin "2") (pinfunction "2_2") (pintype "passive"))
      (node (ref "C85") (pin "2") (pinfunction "2_2") (pintype "passive"))
      (node (ref "C86") (pin "2") (pinfunction "2_2") (pintype "passive"))
      (node (ref "C87") (pin "2") (pinfunction "2_2") (pintype "passive"))
      (node (ref "C88") (pin "2") (pinfunction "2_2") (pintype "passive"))
      (node (ref "C89") (pin "2") (pinfunction "2_2") (pintype "passive"))
      (node (ref "C9") (pin "2") (pinfunction "2_2") (pintype "passive"))
      (node (ref "C90") (pin "2") (pinfunction "2_2") (pintype "passive"))
      (node (ref "C91") (pin "2") (pinfunction "2_2") (pintype "passive"))
      (node (ref "D1") (pin "1") (pinfunction "GND_1") (pintype "bidirectional"))
      (node (ref "D2") (pin "1") (pinfunction "GND_1") (pintype "bidirectional"))
      (node (ref "D3") (pin "1") (pinfunction "GND_1") (pintype "bidirectional"))
      (node (ref "GND") (pin "P$1") (pinfunction "P1_P$1") (pintype "bidirectional"))
      (node (ref "GND49") (pin "P$1") (pinfunction "P1_P$1") (pintype "bidirectional"))
      (node (ref "GND51") (pin "P$1") (pinfunction "P1_P$1") (pintype "bidirectional"))
      (node (ref "GND53") (pin "P$1") (pinfunction "P1_P$1") (pintype "bidirectional"))
      (node (ref "GND55") (pin "P$1") (pinfunction "P1_P$1") (pintype "bidirectional"))
      (node (ref "GND58") (pin "P$1") (pinfunction "P1_P$1") (pintype "bidirectional"))
      (node (ref "GND59") (pin "P$1") (pinfunction "P1_P$1") (pintype "bidirectional"))
      (node (ref "GND62") (pin "P$1") (pinfunction "P1_P$1") (pintype "bidirectional"))
      (node (ref "GND64") (pin "P$1") (pinfunction "P1_P$1") (pintype "bidirectional"))
      (node (ref "GND66") (pin "P$1") (pinfunction "P1_P$1") (pintype "bidirectional"))
      (node (ref "GND70") (pin "P$1") (pinfunction "P1_P$1") (pintype "bidirectional"))
      (node (ref "H1-CONNECTOR1") (pin "19") (pinfunction "19_19") (pintype "bidirectional"))
      (node (ref "H2-CONNECTOR1") (pin "14") (pinfunction "14_14") (pintype "bidirectional"))
      (node (ref "H2-CONNECTOR1") (pin "17") (pinfunction "17_17") (pintype "bidirectional"))
      (node (ref "H2-CONNECTOR1") (pin "21") (pinfunction "21_21") (pintype "bidirectional"))
      (node (ref "H2-CONNECTOR1") (pin "22") (pinfunction "22_22") (pintype "bidirectional"))
      (node (ref "H2-CONNECTOR1") (pin "29") (pinfunction "29_29") (pintype "bidirectional"))
      (node (ref "H2-CONNECTOR1") (pin "30") (pinfunction "30_30") (pintype "bidirectional"))
      (node (ref "H2-CONNECTOR1") (pin "32") (pinfunction "32_32") (pintype "bidirectional"))
      (node (ref "H2-CONNECTOR1") (pin "48") (pinfunction "48_48") (pintype "bidirectional"))
      (node (ref "H2-CONNECTOR1") (pin "9") (pinfunction "9_9") (pintype "bidirectional"))
      (node (ref "IC10") (pin "18") (pinfunction "GND_18") (pintype "power_in"))
      (node (ref "IC10") (pin "21") (pinfunction "GND_21") (pintype "power_in"))
      (node (ref "IC10") (pin "25") (pinfunction "GND_25") (pintype "power_in"))
      (node (ref "IC10") (pin "26") (pinfunction "TEST_26") (pintype "input"))
      (node (ref "IC10") (pin "7") (pinfunction "GND_7") (pintype "power_in"))
      (node (ref "IC3") (pin "18") (pinfunction "GND_18") (pintype "power_in"))
      (node (ref "IC3") (pin "21") (pinfunction "GND_21") (pintype "power_in"))
      (node (ref "IC3") (pin "25") (pinfunction "GND_25") (pintype "power_in"))
      (node (ref "IC3") (pin "26") (pinfunction "TEST_26") (pintype "input"))
      (node (ref "IC3") (pin "7") (pinfunction "GND_7") (pintype "power_in"))
      (node (ref "IC9") (pin "4") (pinfunction "GND_4") (pintype "bidirectional"))
      (node (ref "IR1_3V3") (pin "C") (pinfunction "C_C") (pintype "passive"))
      (node (ref "IR2_3V3") (pin "C") (pinfunction "C_C") (pintype "passive"))
      (node (ref "J1") (pin "5") (pinfunction "GND_5") (pintype "passive"))
      (node (ref "J1") (pin "SHELL") (pinfunction "SHIELD_SHELL") (pintype "passive"))
      (node (ref "J1") (pin "SHELL1") (pinfunction "SHIELD_SHELL1") (pintype "passive"))
      (node (ref "J1") (pin "SHELL2") (pinfunction "SHIELD_SHELL2") (pintype "passive"))
      (node (ref "J1") (pin "SHELL3") (pinfunction "SHIELD_SHELL3") (pintype "passive"))
      (node (ref "J10") (pin "4") (pinfunction "4_4") (pintype "passive"))
      (node (ref "J10") (pin "G1") (pinfunction "SHIELD_G1") (pintype "passive"))
      (node (ref "J10") (pin "G2") (pinfunction "SHIELD_G2") (pintype "passive"))
      (node (ref "J11") (pin "6") (pinfunction "6_6") (pintype "bidirectional"))
      (node (ref "J11") (pin "G1") (pinfunction "G1_G1") (pintype "bidirectional"))
      (node (ref "J11") (pin "G2") (pinfunction "G2_G2") (pintype "bidirectional"))
      (node (ref "J2") (pin "4") (pinfunction "4_4") (pintype "passive"))
      (node (ref "J2") (pin "G1") (pinfunction "SHIELD_G1") (pintype "passive"))
      (node (ref "J2") (pin "G2") (pinfunction "SHIELD_G2") (pintype "passive"))
      (node (ref "J3") (pin "6") (pinfunction "6_6") (pintype "bidirectional"))
      (node (ref "J3") (pin "G1") (pinfunction "G1_G1") (pintype "bidirectional"))
      (node (ref "J3") (pin "G2") (pinfunction "G2_G2") (pintype "bidirectional"))
      (node (ref "J4") (pin "5") (pinfunction "GND_5") (pintype "passive"))
      (node (ref "J4") (pin "SHELL") (pinfunction "SHIELD_SHELL") (pintype "passive"))
      (node (ref "J4") (pin "SHELL1") (pinfunction "SHIELD_SHELL1") (pintype "passive"))
      (node (ref "J4") (pin "SHELL2") (pinfunction "SHIELD_SHELL2") (pintype "passive"))
      (node (ref "J4") (pin "SHELL3") (pinfunction "SHIELD_SHELL3") (pintype "passive"))
      (node (ref "J6") (pin "6") (pinfunction "6_6") (pintype "bidirectional"))
      (node (ref "J6") (pin "G1") (pinfunction "G1_G1") (pintype "bidirectional"))
      (node (ref "J6") (pin "G2") (pinfunction "G2_G2") (pintype "bidirectional"))
      (node (ref "J7") (pin "4") (pinfunction "4_4") (pintype "passive"))
      (node (ref "J7") (pin "G1") (pinfunction "SHIELD_G1") (pintype "passive"))
      (node (ref "J7") (pin "G2") (pinfunction "SHIELD_G2") (pintype "passive"))
      (node (ref "J8") (pin "4") (pinfunction "4_4") (pintype "passive"))
      (node (ref "J8") (pin "G1") (pinfunction "SHIELD_G1") (pintype "passive"))
      (node (ref "J8") (pin "G2") (pinfunction "SHIELD_G2") (pintype "passive"))
      (node (ref "J9") (pin "4") (pinfunction "4_4") (pintype "passive"))
      (node (ref "J9") (pin "G1") (pinfunction "SHIELD_G1") (pintype "passive"))
      (node (ref "J9") (pin "G2") (pinfunction "SHIELD_G2") (pintype "passive"))
      (node (ref "R10") (pin "1") (pinfunction "1_1") (pintype "passive"))
      (node (ref "R17") (pin "1") (pinfunction "1_1") (pintype "passive"))
      (node (ref "R2") (pin "1") (pinfunction "1_1") (pintype "passive"))
      (node (ref "R21") (pin "1") (pinfunction "1_1") (pintype "passive"))
      (node (ref "R22") (pin "1") (pinfunction "1_1") (pintype "passive"))
      (node (ref "R24") (pin "1") (pinfunction "1_1") (pintype "passive"))
      (node (ref "R26") (pin "1") (pinfunction "1_1") (pintype "passive"))
      (node (ref "R37") (pin "1") (pinfunction "1_1") (pintype "passive"))
      (node (ref "R58") (pin "1") (pinfunction "1_1") (pintype "passive"))
      (node (ref "R60") (pin "1") (pinfunction "1_1") (pintype "passive"))
      (node (ref "R77") (pin "1") (pinfunction "1_1") (pintype "passive"))
      (node (ref "R78") (pin "1") (pinfunction "1_1") (pintype "passive"))
      (node (ref "R8") (pin "1") (pinfunction "1_1") (pintype "passive"))
      (node (ref "R81") (pin "1") (pinfunction "1_1") (pintype "passive"))
      (node (ref "R82") (pin "1") (pinfunction "1_1") (pintype "passive"))
      (node (ref "R9") (pin "1") (pinfunction "1_1") (pintype "passive"))
      (node (ref "RPIA_1V8") (pin "C") (pinfunction "C_C") (pintype "passive"))
      (node (ref "RPIA_3V3") (pin "C") (pinfunction "C_C") (pintype "passive"))
      (node (ref "RPIA_RUN") (pin "C") (pinfunction "C_C") (pintype "passive"))
      (node (ref "RPIA_SD_SEL") (pin "C") (pinfunction "C_C") (pintype "passive"))
      (node (ref "RPIB_1V8") (pin "C") (pinfunction "C_C") (pintype "passive"))
      (node (ref "RPIB_3V3") (pin "C") (pinfunction "C_C") (pintype "passive"))
      (node (ref "RPIB_RUN") (pin "C") (pinfunction "C_C") (pintype "passive"))
      (node (ref "RPIB_SD_SEL") (pin "C") (pinfunction "C_C") (pintype "passive"))
      (node (ref "S1") (pin "2") (pinfunction "GND_2") (pintype "bidirectional"))
      (node (ref "S10") (pin "10") (pinfunction "/OE_10") (pintype "bidirectional"))
      (node (ref "S10") (pin "5") (pinfunction "GND_5") (pintype "bidirectional"))
      (node (ref "S2") (pin "2") (pinfunction "GND_2") (pintype "bidirectional"))
      (node (ref "S3") (pin "2") (pinfunction "GND_2") (pintype "bidirectional"))
      (node (ref "S4") (pin "10") (pinfunction "/OE_10") (pintype "bidirectional"))
      (node (ref "S4") (pin "5") (pinfunction "GND_5") (pintype "bidirectional"))
      (node (ref "S5") (pin "10") (pinfunction "/OE_10") (pintype "bidirectional"))
      (node (ref "S5") (pin "5") (pinfunction "GND_5") (pintype "bidirectional"))
      (node (ref "S6") (pin "10") (pinfunction "/OE_10") (pintype "bidirectional"))
      (node (ref "S6") (pin "5") (pinfunction "GND_5") (pintype "bidirectional"))
      (node (ref "S7") (pin "10") (pinfunction "/OE_10") (pintype "bidirectional"))
      (node (ref "S7") (pin "5") (pinfunction "GND_5") (pintype "bidirectional"))
      (node (ref "S8") (pin "10") (pinfunction "/OE_10") (pintype "bidirectional"))
      (node (ref "S8") (pin "5") (pinfunction "GND_5") (pintype "bidirectional"))
      (node (ref "S9") (pin "10") (pinfunction "/OE_10") (pintype "bidirectional"))
      (node (ref "S9") (pin "5") (pinfunction "GND_5") (pintype "bidirectional"))
      (node (ref "U1") (pin "11") (pinfunction "FSYNC_11") (pintype "input"))
      (node (ref "U1") (pin "18") (pinfunction "GND_18") (pintype "power_in"))
      (node (ref "U1") (pin "20") (pinfunction "RESV_20_20") (pintype "passive"))
      (node (ref "U10") (pin "3") (pinfunction "GND_3") (pintype "bidirectional"))
      (node (ref "U11") (pin "2") (pinfunction "/OE_2") (pintype "bidirectional"))
      (node (ref "U11") (pin "7") (pinfunction "GND_7") (pintype "bidirectional"))
      (node (ref "U12") (pin "4") (pinfunction "VSS_4") (pintype "power_in"))
      (node (ref "U13") (pin "2") (pinfunction "/OE_2") (pintype "bidirectional"))
      (node (ref "U13") (pin "7") (pinfunction "GND_7") (pintype "bidirectional"))
      (node (ref "U14") (pin "2") (pinfunction "/OE_2") (pintype "bidirectional"))
      (node (ref "U14") (pin "7") (pinfunction "GND_7") (pintype "bidirectional"))
      (node (ref "U15") (pin "4") (pinfunction "GND_4") (pintype "power_in"))
      (node (ref "U16") (pin "4") (pinfunction "GND_4") (pintype "power_in"))
      (node (ref "U17") (pin "4") (pinfunction "GND_4") (pintype "power_in"))
      (node (ref "U18") (pin "GND1") (pinfunction "GND1_GND1") (pintype "bidirectional"))
      (node (ref "U18") (pin "GND2") (pinfunction "GND2_GND2") (pintype "bidirectional"))
      (node (ref "U19") (pin "3") (pinfunction "GND_3") (pintype "bidirectional"))
      (node (ref "U2") (pin "3") (pinfunction "GND_3") (pintype "bidirectional"))
      (node (ref "U20") (pin "1") (pinfunction "GND_1") (pintype "bidirectional"))
      (node (ref "U20") (pin "103") (pinfunction "GND_103") (pintype "bidirectional"))
      (node (ref "U20") (pin "104") (pinfunction "GND_104") (pintype "bidirectional"))
      (node (ref "U20") (pin "109") (pinfunction "GND_109") (pintype "bidirectional"))
      (node (ref "U20") (pin "110") (pinfunction "GND_110") (pintype "bidirectional"))
      (node (ref "U20") (pin "115") (pinfunction "GND_115") (pintype "bidirectional"))
      (node (ref "U20") (pin "116") (pinfunction "GND_116") (pintype "bidirectional"))
      (node (ref "U20") (pin "121") (pinfunction "GND_121") (pintype "bidirectional"))
      (node (ref "U20") (pin "122") (pinfunction "GND_122") (pintype "bidirectional"))
      (node (ref "U20") (pin "127") (pinfunction "GND_127") (pintype "bidirectional"))
      (node (ref "U20") (pin "13") (pinfunction "GND_13") (pintype "bidirectional"))
      (node (ref "U20") (pin "133") (pinfunction "GND_133") (pintype "bidirectional"))
      (node (ref "U20") (pin "134") (pinfunction "GND_134") (pintype "bidirectional"))
      (node (ref "U20") (pin "139") (pinfunction "GND_139") (pintype "bidirectional"))
      (node (ref "U20") (pin "14") (pinfunction "GND_14") (pintype "bidirectional"))
      (node (ref "U20") (pin "140") (pinfunction "GND_140") (pintype "bidirectional"))
      (node (ref "U20") (pin "145") (pinfunction "GND_145") (pintype "bidirectional"))
      (node (ref "U20") (pin "146") (pinfunction "GND_146") (pintype "bidirectional"))
      (node (ref "U20") (pin "151") (pinfunction "GND_151") (pintype "bidirectional"))
      (node (ref "U20") (pin "152") (pinfunction "GND_152") (pintype "bidirectional"))
      (node (ref "U20") (pin "157") (pinfunction "GND_157") (pintype "bidirectional"))
      (node (ref "U20") (pin "163") (pinfunction "GND_163") (pintype "bidirectional"))
      (node (ref "U20") (pin "164") (pinfunction "GND_164") (pintype "bidirectional"))
      (node (ref "U20") (pin "169") (pinfunction "GND_169") (pintype "bidirectional"))
      (node (ref "U20") (pin "170") (pinfunction "GND_170") (pintype "bidirectional"))
      (node (ref "U20") (pin "181") (pinfunction "GND_181") (pintype "bidirectional"))
      (node (ref "U20") (pin "182") (pinfunction "GND_182") (pintype "bidirectional"))
      (node (ref "U20") (pin "187") (pinfunction "GND_187") (pintype "bidirectional"))
      (node (ref "U20") (pin "188") (pinfunction "GND_188") (pintype "bidirectional"))
      (node (ref "U20") (pin "19") (pinfunction "GND_19") (pintype "bidirectional"))
      (node (ref "U20") (pin "195") (pinfunction "GND_195") (pintype "bidirectional"))
      (node (ref "U20") (pin "196") (pinfunction "GND_196") (pintype "bidirectional"))
      (node (ref "U20") (pin "20") (pinfunction "GND_20") (pintype "bidirectional"))
      (node (ref "U20") (pin "25") (pinfunction "GND_25") (pintype "bidirectional"))
      (node (ref "U20") (pin "26") (pinfunction "GND_26") (pintype "bidirectional"))
      (node (ref "U20") (pin "31") (pinfunction "GND_31") (pintype "bidirectional"))
      (node (ref "U20") (pin "32") (pinfunction "GND_32") (pintype "bidirectional"))
      (node (ref "U20") (pin "37") (pinfunction "GND_37") (pintype "bidirectional"))
      (node (ref "U20") (pin "38") (pinfunction "GND_38") (pintype "bidirectional"))
      (node (ref "U20") (pin "43") (pinfunction "GND_43") (pintype "bidirectional"))
      (node (ref "U20") (pin "44") (pinfunction "GND_44") (pintype "bidirectional"))
      (node (ref "U20") (pin "49") (pinfunction "GND_49") (pintype "bidirectional"))
      (node (ref "U20") (pin "50") (pinfunction "GND_50") (pintype "bidirectional"))
      (node (ref "U20") (pin "55") (pinfunction "GND_55") (pintype "bidirectional"))
      (node (ref "U20") (pin "56") (pinfunction "GND_56") (pintype "bidirectional"))
      (node (ref "U20") (pin "61") (pinfunction "GND_61") (pintype "bidirectional"))
      (node (ref "U20") (pin "62") (pinfunction "GND_62") (pintype "bidirectional"))
      (node (ref "U20") (pin "67") (pinfunction "GND_67") (pintype "bidirectional"))
      (node (ref "U20") (pin "68") (pinfunction "GND_68") (pintype "bidirectional"))
      (node (ref "U20") (pin "7") (pinfunction "GND_7") (pintype "bidirectional"))
      (node (ref "U20") (pin "73") (pinfunction "GND_73") (pintype "bidirectional"))
      (node (ref "U20") (pin "74") (pinfunction "GND_74") (pintype "bidirectional"))
      (node (ref "U20") (pin "79") (pinfunction "GND_79") (pintype "bidirectional"))
      (node (ref "U20") (pin "8") (pinfunction "GND_8") (pintype "bidirectional"))
      (node (ref "U20") (pin "80") (pinfunction "GND_80") (pintype "bidirectional"))
      (node (ref "U20") (pin "85") (pinfunction "GND_85") (pintype "bidirectional"))
      (node (ref "U20") (pin "86") (pinfunction "GND_86") (pintype "bidirectional"))
      (node (ref "U20") (pin "91") (pinfunction "GND_91") (pintype "bidirectional"))
      (node (ref "U20") (pin "92") (pinfunction "GND_92") (pintype "bidirectional"))
      (node (ref "U20") (pin "97") (pinfunction "GND_97") (pintype "bidirectional"))
      (node (ref "U20") (pin "98") (pinfunction "GND_98") (pintype "bidirectional"))
      (node (ref "U21") (pin "1") (pinfunction "GND_1") (pintype "bidirectional"))
      (node (ref "U21") (pin "103") (pinfunction "GND_103") (pintype "bidirectional"))
      (node (ref "U21") (pin "104") (pinfunction "GND_104") (pintype "bidirectional"))
      (node (ref "U21") (pin "109") (pinfunction "GND_109") (pintype "bidirectional"))
      (node (ref "U21") (pin "110") (pinfunction "GND_110") (pintype "bidirectional"))
      (node (ref "U21") (pin "115") (pinfunction "GND_115") (pintype "bidirectional"))
      (node (ref "U21") (pin "116") (pinfunction "GND_116") (pintype "bidirectional"))
      (node (ref "U21") (pin "121") (pinfunction "GND_121") (pintype "bidirectional"))
      (node (ref "U21") (pin "122") (pinfunction "GND_122") (pintype "bidirectional"))
      (node (ref "U21") (pin "127") (pinfunction "GND_127") (pintype "bidirectional"))
      (node (ref "U21") (pin "13") (pinfunction "GND_13") (pintype "bidirectional"))
      (node (ref "U21") (pin "133") (pinfunction "GND_133") (pintype "bidirectional"))
      (node (ref "U21") (pin "134") (pinfunction "GND_134") (pintype "bidirectional"))
      (node (ref "U21") (pin "139") (pinfunction "GND_139") (pintype "bidirectional"))
      (node (ref "U21") (pin "14") (pinfunction "GND_14") (pintype "bidirectional"))
      (node (ref "U21") (pin "140") (pinfunction "GND_140") (pintype "bidirectional"))
      (node (ref "U21") (pin "145") (pinfunction "GND_145") (pintype "bidirectional"))
      (node (ref "U21") (pin "146") (pinfunction "GND_146") (pintype "bidirectional"))
      (node (ref "U21") (pin "151") (pinfunction "GND_151") (pintype "bidirectional"))
      (node (ref "U21") (pin "152") (pinfunction "GND_152") (pintype "bidirectional"))
      (node (ref "U21") (pin "157") (pinfunction "GND_157") (pintype "bidirectional"))
      (node (ref "U21") (pin "163") (pinfunction "GND_163") (pintype "bidirectional"))
      (node (ref "U21") (pin "164") (pinfunction "GND_164") (pintype "bidirectional"))
      (node (ref "U21") (pin "169") (pinfunction "GND_169") (pintype "bidirectional"))
      (node (ref "U21") (pin "170") (pinfunction "GND_170") (pintype "bidirectional"))
      (node (ref "U21") (pin "181") (pinfunction "GND_181") (pintype "bidirectional"))
      (node (ref "U21") (pin "182") (pinfunction "GND_182") (pintype "bidirectional"))
      (node (ref "U21") (pin "187") (pinfunction "GND_187") (pintype "bidirectional"))
      (node (ref "U21") (pin "188") (pinfunction "GND_188") (pintype "bidirectional"))
      (node (ref "U21") (pin "19") (pinfunction "GND_19") (pintype "bidirectional"))
      (node (ref "U21") (pin "195") (pinfunction "GND_195") (pintype "bidirectional"))
      (node (ref "U21") (pin "196") (pinfunction "GND_196") (pintype "bidirectional"))
      (node (ref "U21") (pin "20") (pinfunction "GND_20") (pintype "bidirectional"))
      (node (ref "U21") (pin "25") (pinfunction "GND_25") (pintype "bidirectional"))
      (node (ref "U21") (pin "26") (pinfunction "GND_26") (pintype "bidirectional"))
      (node (ref "U21") (pin "31") (pinfunction "GND_31") (pintype "bidirectional"))
      (node (ref "U21") (pin "32") (pinfunction "GND_32") (pintype "bidirectional"))
      (node (ref "U21") (pin "37") (pinfunction "GND_37") (pintype "bidirectional"))
      (node (ref "U21") (pin "38") (pinfunction "GND_38") (pintype "bidirectional"))
      (node (ref "U21") (pin "43") (pinfunction "GND_43") (pintype "bidirectional"))
      (node (ref "U21") (pin "44") (pinfunction "GND_44") (pintype "bidirectional"))
      (node (ref "U21") (pin "49") (pinfunction "GND_49") (pintype "bidirectional"))
      (node (ref "U21") (pin "50") (pinfunction "GND_50") (pintype "bidirectional"))
      (node (ref "U21") (pin "55") (pinfunction "GND_55") (pintype "bidirectional"))
      (node (ref "U21") (pin "56") (pinfunction "GND_56") (pintype "bidirectional"))
      (node (ref "U21") (pin "61") (pinfunction "GND_61") (pintype "bidirectional"))
      (node (ref "U21") (pin "62") (pinfunction "GND_62") (pintype "bidirectional"))
      (node (ref "U21") (pin "67") (pinfunction "GND_67") (pintype "bidirectional"))
      (node (ref "U21") (pin "68") (pinfunction "GND_68") (pintype "bidirectional"))
      (node (ref "U21") (pin "7") (pinfunction "GND_7") (pintype "bidirectional"))
      (node (ref "U21") (pin "73") (pinfunction "GND_73") (pintype "bidirectional"))
      (node (ref "U21") (pin "74") (pinfunction "GND_74") (pintype "bidirectional"))
      (node (ref "U21") (pin "79") (pinfunction "GND_79") (pintype "bidirectional"))
      (node (ref "U21") (pin "8") (pinfunction "GND_8") (pintype "bidirectional"))
      (node (ref "U21") (pin "80") (pinfunction "GND_80") (pintype "bidirectional"))
      (node (ref "U21") (pin "85") (pinfunction "GND_85") (pintype "bidirectional"))
      (node (ref "U21") (pin "86") (pinfunction "GND_86") (pintype "bidirectional"))
      (node (ref "U21") (pin "91") (pinfunction "GND_91") (pintype "bidirectional"))
      (node (ref "U21") (pin "92") (pinfunction "GND_92") (pintype "bidirectional"))
      (node (ref "U21") (pin "97") (pinfunction "GND_97") (pintype "bidirectional"))
      (node (ref "U21") (pin "98") (pinfunction "GND_98") (pintype "bidirectional"))
      (node (ref "U22") (pin "3") (pinfunction "GND_3") (pintype "bidirectional"))
      (node (ref "U23") (pin "3") (pinfunction "GND_3") (pintype "bidirectional"))
      (node (ref "U24") (pin "3") (pinfunction "GND_3") (pintype "bidirectional"))
      (node (ref "U25") (pin "3") (pinfunction "GND_3") (pintype "bidirectional"))
      (node (ref "U3") (pin "11") (pinfunction "FSYNC_11") (pintype "input"))
      (node (ref "U3") (pin "18") (pinfunction "GND_18") (pintype "power_in"))
      (node (ref "U3") (pin "20") (pinfunction "RESV_20_20") (pintype "passive"))
      (node (ref "U4") (pin "2") (pinfunction "/OE_2") (pintype "bidirectional"))
      (node (ref "U4") (pin "7") (pinfunction "GND_7") (pintype "bidirectional"))
      (node (ref "U5") (pin "2") (pinfunction "GND_2") (pintype "bidirectional"))
      (node (ref "U6") (pin "2") (pinfunction "GND_2") (pintype "bidirectional"))
      (node (ref "U7") (pin "4") (pinfunction "GND_4") (pintype "power_in"))
      (node (ref "U8") (pin "65") (pinfunction "VSS_65") (pintype "power_in"))
      (node (ref "U9") (pin "3") (pinfunction "GND_3") (pintype "bidirectional"))
      (node (ref "USB_F_VBUS") (pin "C") (pinfunction "C_C") (pintype "passive"))
      (node (ref "VIS_5V") (pin "C") (pinfunction "C_C") (pintype "passive"))
      (node (ref "X1") (pin "6") (pinfunction "VSS_6") (pintype "bidirectional"))
      (node (ref "X2") (pin "6") (pinfunction "VSS_6") (pintype "bidirectional"))
      (node (ref "X5") (pin "6") (pinfunction "VSS_6") (pintype "bidirectional"))
      (node (ref "X6") (pin "6") (pinfunction "VSS_6") (pintype "bidirectional"))
    )
    (net (code "28") (name "GPS_RX") (class "Default")
      (node (ref "GPS_3") (pin "TP") (pinfunction "TP_TP") (pintype "input"))
      (node (ref "G_RX") (pin "P$1") (pinfunction "P1_P$1") (pintype "bidirectional"))
      (node (ref "IC10") (pin "1") (pinfunction "TXD_1") (pintype "output"))
      (node (ref "J10") (pin "3") (pinfunction "3_3") (pintype "passive"))
    )
    (net (code "29") (name "GPS_TX") (class "Default")
      (node (ref "GPS_2") (pin "TP") (pinfunction "TP_TP") (pintype "input"))
      (node (ref "G_TX") (pin "P$1") (pinfunction "P1_P$1") (pintype "bidirectional"))
      (node (ref "IC10") (pin "5") (pinfunction "RXD_5") (pintype "input"))
      (node (ref "J10") (pin "2") (pinfunction "2_2") (pintype "passive"))
    )
    (net (code "30") (name "GPS_USB_DM") (class "Default")
      (node (ref "IC10") (pin "16") (pinfunction "USBDM_16") (pintype "bidirectional"))
      (node (ref "U8") (pin "11") (pinfunction "USBDN5_DM/PRT_DIS_M5_11") (pintype "bidirectional"))
    )
    (net (code "31") (name "GPS_USB_DP") (class "Default")
      (node (ref "IC10") (pin "15") (pinfunction "USBDP_15") (pintype "bidirectional"))
      (node (ref "U8") (pin "12") (pinfunction "USBDN5_DP/PRT_DIS_P5_12") (pintype "bidirectional"))
    )
    (net (code "32") (name "H_EN_1") (class "Default")
      (node (ref "H2-CONNECTOR1") (pin "52") (pinfunction "52_52") (pintype "bidirectional"))
      (node (ref "U20") (pin "76") (pinfunction "GPIO42_76") (pintype "bidirectional"))
      (node (ref "U21") (pin "76") (pinfunction "GPIO42_76") (pintype "bidirectional"))
    )
    (net (code "33") (name "H_EN_2") (class "Default")
      (node (ref "H2-CONNECTOR1") (pin "50") (pinfunction "50_50") (pintype "bidirectional"))
      (node (ref "U20") (pin "70") (pinfunction "GPIO40_70") (pintype "bidirectional"))
      (node (ref "U21") (pin "70") (pinfunction "GPIO40_70") (pintype "bidirectional"))
    )
    (net (code "34") (name "H_EN_3") (class "Default")
      (node (ref "H2-CONNECTOR1") (pin "46") (pinfunction "46_46") (pintype "bidirectional"))
      (node (ref "U20") (pin "66") (pinfunction "GPIO39_66") (pintype "bidirectional"))
      (node (ref "U21") (pin "66") (pinfunction "GPIO39_66") (pintype "bidirectional"))
    )
    (net (code "35") (name "H_EN_4") (class "Default")
      (node (ref "H2-CONNECTOR1") (pin "44") (pinfunction "44_44") (pintype "bidirectional"))
      (node (ref "U20") (pin "64") (pinfunction "GPIO38_64") (pintype "bidirectional"))
      (node (ref "U21") (pin "64") (pinfunction "GPIO38_64") (pintype "bidirectional"))
    )
    (net (code "36") (name "H_EN_5") (class "Default")
      (node (ref "H2-CONNECTOR1") (pin "42") (pinfunction "42_42") (pintype "bidirectional"))
      (node (ref "U20") (pin "60") (pinfunction "GPIO37_60") (pintype "bidirectional"))
      (node (ref "U21") (pin "60") (pinfunction "GPIO37_60") (pintype "bidirectional"))
    )
    (net (code "37") (name "I2C_0_SCL") (class "Default")
      (node (ref "H1-CONNECTOR1") (pin "43") (pinfunction "43_43") (pintype "bidirectional"))
      (node (ref "I2C_0_C") (pin "TP") (pinfunction "TP_TP") (pintype "input"))
      (node (ref "R83") (pin "1") (pinfunction "1_1") (pintype "passive"))
      (node (ref "S8") (pin "4") (pinfunction "D-_4") (pintype "bidirectional"))
    )
    (net (code "38") (name "I2C_0_SDA") (class "Default")
      (node (ref "H1-CONNECTOR1") (pin "41") (pinfunction "41_41") (pintype "bidirectional"))
      (node (ref "I2C_0_D") (pin "TP") (pinfunction "TP_TP") (pintype "input"))
      (node (ref "R84") (pin "1") (pinfunction "1_1") (pintype "passive"))
      (node (ref "S8") (pin "3") (pinfunction "D+_3") (pintype "bidirectional"))
    )
    (net (code "39") (name "I2C_1_SCL") (class "Default")
      (node (ref "ANT_3") (pin "TP") (pinfunction "TP_TP") (pintype "input"))
      (node (ref "H1-CONNECTOR1") (pin "21") (pinfunction "21_21") (pintype "bidirectional"))
      (node (ref "I2C_1_C") (pin "TP") (pinfunction "TP_TP") (pintype "input"))
      (node (ref "J9") (pin "3") (pinfunction "3_3") (pintype "passive"))
      (node (ref "R85") (pin "2") (pinfunction "2_2") (pintype "passive"))
      (node (ref "S9") (pin "4") (pinfunction "D-_4") (pintype "bidirectional"))
      (node (ref "U12") (pin "6") (pinfunction "SCL_6") (pintype "passive"))
    )
    (net (code "40") (name "I2C_1_SDA") (class "Default")
      (node (ref "ANT_2") (pin "TP") (pinfunction "TP_TP") (pintype "input"))
      (node (ref "H1-CONNECTOR1") (pin "23") (pinfunction "23_23") (pintype "bidirectional"))
      (node (ref "I2C_1_D") (pin "TP") (pinfunction "TP_TP") (pintype "input"))
      (node (ref "J9") (pin "2") (pinfunction "2_2") (pintype "passive"))
      (node (ref "R86") (pin "1") (pinfunction "1_1") (pintype "passive"))
      (node (ref "S9") (pin "3") (pinfunction "D+_3") (pintype "bidirectional"))
      (node (ref "U12") (pin "5") (pinfunction "SDA_5") (pintype "bidirectional"))
    )
    (net (code "41") (name "IR1_VCC_3V3") (class "Default")
      (node (ref "C5") (pin "1") (pinfunction "1_1") (pintype "passive"))
      (node (ref "IR1_1") (pin "TP") (pinfunction "TP_TP") (pintype "input"))
      (node (ref "J7") (pin "1") (pinfunction "1_1") (pintype "passive"))
      (node (ref "R61") (pin "1") (pinfunction "1_1") (pintype "passive"))
      (node (ref "S2") (pin "1") (pinfunction "OUT_1") (pintype "bidirectional"))
    )
    (net (code "42") (name "IR2_VCC_3V3") (class "Default")
      (node (ref "C7") (pin "1") (pinfunction "1_1") (pintype "passive"))
      (node (ref "IR2_1") (pin "TP") (pinfunction "TP_TP") (pintype "input"))
      (node (ref "J8") (pin "1") (pinfunction "1_1") (pintype "passive"))
      (node (ref "R70") (pin "1") (pinfunction "1_1") (pintype "passive"))
      (node (ref "S3") (pin "1") (pinfunction "OUT_1") (pintype "bidirectional"))
    )
    (net (code "43") (name "LST_CST") (class "Default")
      (node (ref "J3") (pin "5") (pinfunction "5_5") (pintype "bidirectional"))
      (node (ref "LST_5") (pin "TP") (pinfunction "TP_TP") (pintype "input"))
    )
    (net (code "44") (name "LST_RX") (class "Default")
      (node (ref "J3") (pin "3") (pinfunction "3_3") (pintype "bidirectional"))
      (node (ref "LST_3") (pin "TP") (pinfunction "TP_TP") (pintype "input"))
      (node (ref "LST_RX") (pin "P$1") (pinfunction "P1_P$1") (pintype "bidirectional"))
      (node (ref "S6") (pin "3") (pinfunction "D+_3") (pintype "bidirectional"))
    )
    (net (code "45") (name "LST_TX") (class "Default")
      (node (ref "J3") (pin "2") (pinfunction "2_2") (pintype "bidirectional"))
      (node (ref "LST_2") (pin "TP") (pinfunction "TP_TP") (pintype "input"))
      (node (ref "LST_TX") (pin "P$1") (pinfunction "P1_P$1") (pintype "bidirectional"))
      (node (ref "S6") (pin "4") (pinfunction "D-_4") (pintype "bidirectional"))
    )
    (net (code "46") (name "Net-(BB_TX_SHIFT-P1)") (class "Default")
      (node (ref "BB_TX_SHIFT") (pin "P$1") (pinfunction "P1_P$1") (pintype "bidirectional"))
      (node (ref "S7") (pin "4") (pinfunction "D-_4") (pintype "bidirectional"))
      (node (ref "U9") (pin "4") (pinfunction "Y_4") (pintype "bidirectional"))
    )
    (net (code "47") (name "Net-(DEBUG-PadA)") (class "Default")
      (node (ref "DEBUG") (pin "A") (pinfunction "A_A") (pintype "passive"))
      (node (ref "R79") (pin "1") (pinfunction "1_1") (pintype "passive"))
    )
    (net (code "48") (name "Net-(GPS-PadA)") (class "Default")
      (node (ref "GPS") (pin "A") (pinfunction "A_A") (pintype "passive"))
      (node (ref "R75") (pin "1") (pinfunction "1_1") (pintype "passive"))
    )
    (net (code "49") (name "Net-(GPS_RX-PadA)") (class "Default")
      (node (ref "GPS_RX") (pin "A") (pinfunction "A_A") (pintype "passive"))
      (node (ref "R33") (pin "2") (pinfunction "2_2") (pintype "passive"))
    )
    (net (code "50") (name "Net-(GPS_TX-PadA)") (class "Default")
      (node (ref "GPS_TX") (pin "A") (pinfunction "A_A") (pintype "passive"))
      (node (ref "R32") (pin "2") (pinfunction "2_2") (pintype "passive"))
    )
    (net (code "51") (name "Net-(IC3-3V3OUT)") (class "Default")
      (node (ref "C9") (pin "1") (pinfunction "1_1") (pintype "passive"))
      (node (ref "IC3") (pin "17") (pinfunction "3V3OUT_17") (pintype "output"))
    )
    (net (code "52") (name "Net-(IC3-CBUS0)") (class "Default")
      (node (ref "IC3") (pin "23") (pinfunction "CBUS0_23") (pintype "bidirectional"))
      (node (ref "TILE_TX") (pin "C") (pinfunction "C_C") (pintype "passive"))
    )
    (net (code "53") (name "Net-(IC3-CBUS1)") (class "Default")
      (node (ref "IC3") (pin "22") (pinfunction "CBUS1_22") (pintype "bidirectional"))
      (node (ref "TILE_RX") (pin "C") (pinfunction "C_C") (pintype "passive"))
    )
    (net (code "54") (name "Net-(IC3-~{RESET})") (class "Default")
      (node (ref "IC3") (pin "19") (pinfunction "~{RESET}_19") (pintype "input"))
      (node (ref "R11") (pin "2") (pinfunction "2_2") (pintype "passive"))
    )
    (net (code "55") (name "Net-(IC4A-I1)") (class "Default")
      (node (ref "IC4") (pin "2") (pinfunction "I1_2") (pintype "input"))
      (node (ref "IC7") (pin "1") (pinfunction "CLK_1") (pintype "input"))
      (node (ref "R13") (pin "2") (pinfunction "2_2") (pintype "passive"))
      (node (ref "R4") (pin "1") (pinfunction "1_1") (pintype "passive"))
      (node (ref "WD_RES_A") (pin "TP") (pinfunction "TP_TP") (pintype "input"))
      (node (ref "W_RES_A") (pin "P$1") (pinfunction "P1_P$1") (pintype "bidirectional"))
    )
    (net (code "56") (name "Net-(IC5A-I0)") (class "Default")
      (node (ref "IC5") (pin "1") (pinfunction "I0_1") (pintype "input"))
      (node (ref "IC6") (pin "4") (pinfunction "O_4") (pintype "output"))
      (node (ref "R89") (pin "1") (pinfunction "1_1") (pintype "passive"))
      (node (ref "R91") (pin "2") (pinfunction "2_2") (pintype "passive"))
    )
    (net (code "57") (name "Net-(IC5A-I1)") (class "Default")
      (node (ref "IC5") (pin "2") (pinfunction "I1_2") (pintype "input"))
      (node (ref "IC7") (pin "13") (pinfunction "CLK_13") (pintype "input"))
      (node (ref "R14") (pin "2") (pinfunction "2_2") (pintype "passive"))
      (node (ref "R6") (pin "1") (pinfunction "1_1") (pintype "passive"))
      (node (ref "WD_RES_B") (pin "TP") (pinfunction "TP_TP") (pintype "input"))
      (node (ref "W_RES_B") (pin "P$1") (pinfunction "P1_P$1") (pintype "bidirectional"))
    )
    (net (code "58") (name "Net-(IC7A-J)") (class "Default")
      (node (ref "IC7") (pin "2") (pinfunction "K_2") (pintype "input"))
      (node (ref "IC7") (pin "3") (pinfunction "J_3") (pintype "input"))
      (node (ref "R3") (pin "2") (pinfunction "2_2") (pintype "passive"))
    )
    (net (code "59") (name "Net-(IC7B-J)") (class "Default")
      (node (ref "IC7") (pin "11") (pinfunction "J_11") (pintype "input"))
      (node (ref "IC7") (pin "12") (pinfunction "K_12") (pintype "input"))
      (node (ref "R91") (pin "1") (pinfunction "1_1") (pintype "passive"))
    )
    (net (code "60") (name "Net-(IC9-A)") (class "Default")
      (node (ref "IC9") (pin "8") (pinfunction "A_8") (pintype "input"))
      (node (ref "R16") (pin "1") (pinfunction "1_1") (pintype "passive"))
      (node (ref "TX_A") (pin "2") (pinfunction "2_2") (pintype "passive"))
    )
    (net (code "61") (name "Net-(IC9-B)") (class "Default")
      (node (ref "IC9") (pin "7") (pinfunction "B_7") (pintype "input"))
      (node (ref "R16") (pin "2") (pinfunction "2_2") (pintype "passive"))
      (node (ref "TX_B") (pin "2") (pinfunction "2_2") (pintype "passive"))
    )
    (net (code "62") (name "Net-(IC9-Y)") (class "Default")
      (node (ref "IC9") (pin "5") (pinfunction "Y_5") (pintype "output"))
      (node (ref "R15") (pin "1") (pinfunction "1_1") (pintype "passive"))
      (node (ref "RX_Y") (pin "2") (pinfunction "2_2") (pintype "passive"))
    )
    (net (code "63") (name "Net-(IC9-Z)") (class "Default")
      (node (ref "IC9") (pin "6") (pinfunction "Z_6") (pintype "output"))
      (node (ref "R15") (pin "2") (pinfunction "2_2") (pintype "passive"))
      (node (ref "RX_Z") (pin "2") (pinfunction "2_2") (pintype "passive"))
    )
    (net (code "64") (name "Net-(IC10-3V3OUT)") (class "Default")
      (node (ref "C49") (pin "1") (pinfunction "1_1") (pintype "passive"))
      (node (ref "IC10") (pin "17") (pinfunction "3V3OUT_17") (pintype "output"))
      (node (ref "IC10") (pin "4") (pinfunction "VCCIO_4") (pintype "power_in"))
    )
    (net (code "65") (name "Net-(IC10-CBUS0)") (class "Default")
      (node (ref "GPS_TX") (pin "C") (pinfunction "C_C") (pintype "passive"))
      (node (ref "IC10") (pin "23") (pinfunction "CBUS0_23") (pintype "bidirectional"))
    )
    (net (code "66") (name "Net-(IC10-CBUS1)") (class "Default")
      (node (ref "GPS_RX") (pin "C") (pinfunction "C_C") (pintype "passive"))
      (node (ref "IC10") (pin "22") (pinfunction "CBUS1_22") (pintype "bidirectional"))
    )
    (net (code "67") (name "Net-(IC10-~{RESET})") (class "Default")
      (node (ref "IC10") (pin "19") (pinfunction "~{RESET}_19") (pintype "input"))
      (node (ref "R31") (pin "2") (pinfunction "2_2") (pintype "passive"))
    )
    (net (code "68") (name "Net-(IR1-PadA)") (class "Default")
      (node (ref "IR1") (pin "A") (pinfunction "A_A") (pintype "passive"))
      (node (ref "R39") (pin "1") (pinfunction "1_1") (pintype "passive"))
    )
    (net (code "69") (name "Net-(IR1_3V3-PadA)") (class "Default")
      (node (ref "IR1_3V3") (pin "A") (pinfunction "A_A") (pintype "passive"))
      (node (ref "R61") (pin "2") (pinfunction "2_2") (pintype "passive"))
    )
    (net (code "70") (name "Net-(IR2-PadA)") (class "Default")
      (node (ref "IR2") (pin "A") (pinfunction "A_A") (pintype "passive"))
      (node (ref "R40") (pin "1") (pinfunction "1_1") (pintype "passive"))
    )
    (net (code "71") (name "Net-(IR2_3V3-PadA)") (class "Default")
      (node (ref "IR2_3V3") (pin "A") (pinfunction "A_A") (pintype "passive"))
      (node (ref "R70") (pin "2") (pinfunction "2_2") (pintype "passive"))
    )
    (net (code "72") (name "Net-(J1-ID)") (class "Default")
      (node (ref "ID_F") (pin "TP") (pinfunction "TP_TP") (pintype "input"))
      (node (ref "J1") (pin "4") (pinfunction "ID_4") (pintype "passive"))
    )
    (net (code "73") (name "Net-(J4-ID)") (class "Default")
      (node (ref "J4") (pin "4") (pinfunction "ID_4") (pintype "passive"))
      (node (ref "R37") (pin "2") (pinfunction "2_2") (pintype "passive"))
    )
    (net (code "74") (name "Net-(R12-Pad2)") (class "Default")
      (node (ref "R12") (pin "2") (pinfunction "2_2") (pintype "passive"))
      (node (ref "TILE_TX") (pin "A") (pinfunction "A_A") (pintype "passive"))
    )
    (net (code "75") (name "Net-(R30-Pad2)") (class "Default")
      (node (ref "R30") (pin "2") (pinfunction "2_2") (pintype "passive"))
      (node (ref "TILE_RX") (pin "A") (pinfunction "A_A") (pintype "passive"))
    )
    (net (code "76") (name "Net-(R38-Pad2)") (class "Default")
      (node (ref "R38") (pin "2") (pinfunction "2_2") (pintype "passive"))
      (node (ref "USB_F_VBUS") (pin "A") (pinfunction "A_A") (pintype "passive"))
    )
    (net (code "77") (name "Net-(R59-Pad2)") (class "Default")
      (node (ref "R59") (pin "2") (pinfunction "2_2") (pintype "passive"))
      (node (ref "VIS_5V") (pin "A") (pinfunction "A_A") (pintype "passive"))
    )
    (net (code "78") (name "Net-(R62-Pad1)") (class "Default")
      (node (ref "R62") (pin "1") (pinfunction "1_1") (pintype "passive"))
      (node (ref "RPIB_3V3") (pin "A") (pinfunction "A_A") (pintype "passive"))
    )
    (net (code "79") (name "Net-(R63-Pad1)") (class "Default")
      (node (ref "R63") (pin "1") (pinfunction "1_1") (pintype "passive"))
      (node (ref "RPIA_3V3") (pin "A") (pinfunction "A_A") (pintype "passive"))
    )
    (net (code "80") (name "Net-(R64-Pad1)") (class "Default")
      (node (ref "R64") (pin "1") (pinfunction "1_1") (pintype "passive"))
      (node (ref "RPIA_1V8") (pin "A") (pinfunction "A_A") (pintype "passive"))
    )
    (net (code "81") (name "Net-(R65-Pad1)") (class "Default")
      (node (ref "R65") (pin "1") (pinfunction "1_1") (pintype "passive"))
      (node (ref "RPIB_1V8") (pin "A") (pinfunction "A_A") (pintype "passive"))
    )
    (net (code "82") (name "Net-(R68-Pad2)") (class "Default")
      (node (ref "R68") (pin "2") (pinfunction "2_2") (pintype "passive"))
      (node (ref "RPIA_SD_SEL") (pin "A") (pinfunction "A_A") (pintype "passive"))
    )
    (net (code "83") (name "Net-(R69-Pad2)") (class "Default")
      (node (ref "R69") (pin "2") (pinfunction "2_2") (pintype "passive"))
      (node (ref "RPIB_SD_SEL") (pin "A") (pinfunction "A_A") (pintype "passive"))
    )
    (net (code "84") (name "Net-(R71-Pad1)") (class "Default")
      (node (ref "R71") (pin "1") (pinfunction "1_1") (pintype "passive"))
      (node (ref "VIS") (pin "A") (pinfunction "A_A") (pintype "passive"))
    )
    (net (code "85") (name "Net-(R72-Pad1)") (class "Default")
      (node (ref "R72") (pin "1") (pinfunction "1_1") (pintype "passive"))
      (node (ref "TILE") (pin "A") (pinfunction "A_A") (pintype "passive"))
    )
    (net (code "86") (name "Net-(R73-Pad2)") (class "Default")
      (node (ref "R73") (pin "2") (pinfunction "2_2") (pintype "passive"))
      (node (ref "RPIA_RUN") (pin "A") (pinfunction "A_A") (pintype "passive"))
    )
    (net (code "87") (name "Net-(R74-Pad2)") (class "Default")
      (node (ref "R74") (pin "2") (pinfunction "2_2") (pintype "passive"))
      (node (ref "RPIB_RUN") (pin "A") (pinfunction "A_A") (pintype "passive"))
    )
    (net (code "88") (name "Net-(S1-SET)") (class "Default")
      (node (ref "R8") (pin "2") (pinfunction "2_2") (pintype "passive"))
      (node (ref "S1") (pin "3") (pinfunction "SET_3") (pintype "bidirectional"))
    )
    (net (code "89") (name "Net-(S2-SET)") (class "Default")
      (node (ref "R9") (pin "2") (pinfunction "2_2") (pintype "passive"))
      (node (ref "S2") (pin "3") (pinfunction "SET_3") (pintype "bidirectional"))
    )
    (net (code "90") (name "Net-(S3-SET)") (class "Default")
      (node (ref "R10") (pin "2") (pinfunction "2_2") (pintype "passive"))
      (node (ref "S3") (pin "3") (pinfunction "SET_3") (pintype "bidirectional"))
    )
    (net (code "91") (name "Net-(S4-D+)") (class "Default")
      (node (ref "S4") (pin "3") (pinfunction "D+_3") (pintype "bidirectional"))
      (node (ref "S5") (pin "3") (pinfunction "D+_3") (pintype "bidirectional"))
    )
    (net (code "92") (name "Net-(S4-D-)") (class "Default")
      (node (ref "S4") (pin "4") (pinfunction "D-_4") (pintype "bidirectional"))
      (node (ref "S5") (pin "4") (pinfunction "D-_4") (pintype "bidirectional"))
    )
    (net (code "93") (name "Net-(S5-HSD1+)") (class "Default")
      (node (ref "S5") (pin "7") (pinfunction "HSD1+_7") (pintype "bidirectional"))
      (node (ref "U8") (pin "59") (pinfunction "USBUP_DP_59") (pintype "bidirectional"))
    )
    (net (code "94") (name "Net-(S5-HSD1-)") (class "Default")
      (node (ref "S5") (pin "6") (pinfunction "HSD1-_6") (pintype "bidirectional"))
      (node (ref "U8") (pin "58") (pinfunction "USBUP_DM_58") (pintype "bidirectional"))
    )
    (net (code "95") (name "Net-(S5-SEL)") (class "Default")
      (node (ref "R87") (pin "2") (pinfunction "2_2") (pintype "passive"))
      (node (ref "S5") (pin "2") (pinfunction "SEL_2") (pintype "bidirectional"))
      (node (ref "S_USB_F") (pin "P$1") (pinfunction "P1_P$1") (pintype "bidirectional"))
    )
    (net (code "96") (name "Net-(S7-D+)") (class "Default")
      (node (ref "S7") (pin "3") (pinfunction "D+_3") (pintype "bidirectional"))
      (node (ref "U10") (pin "2") (pinfunction "A_2") (pintype "bidirectional"))
    )
    (net (code "97") (name "Net-(U1-NCS)") (class "Default")
      (node (ref "U1") (pin "22") (pinfunction "NCS_22") (pintype "input"))
      (node (ref "U25") (pin "4") (pinfunction "Y_4") (pintype "bidirectional"))
    )
    (net (code "98") (name "Net-(U1-REGOUT)") (class "Default")
      (node (ref "C87") (pin "1") (pinfunction "1_1") (pintype "passive"))
      (node (ref "U1") (pin "10") (pinfunction "REGOUT_10") (pintype "output"))
    )
    (net (code "99") (name "Net-(U1-SCL{slash}SCLK)") (class "Default")
      (node (ref "U1") (pin "23") (pinfunction "SCL/SCLK_23") (pintype "input"))
      (node (ref "U23") (pin "4") (pinfunction "Y_4") (pintype "bidirectional"))
    )
    (net (code "100") (name "Net-(U1-SDA{slash}SDI)") (class "Default")
      (node (ref "U1") (pin "24") (pinfunction "SDA/SDI_24") (pintype "bidirectional"))
      (node (ref "U24") (pin "4") (pinfunction "Y_4") (pintype "bidirectional"))
    )
    (net (code "101") (name "Net-(U2-Y)") (class "Default")
      (node (ref "U2") (pin "4") (pinfunction "Y_4") (pintype "bidirectional"))
      (node (ref "U3") (pin "23") (pinfunction "SCL/SCLK_23") (pintype "input"))
    )
    (net (code "102") (name "Net-(U3-REGOUT)") (class "Default")
      (node (ref "C30") (pin "1") (pinfunction "1_1") (pintype "passive"))
      (node (ref "U3") (pin "10") (pinfunction "REGOUT_10") (pintype "output"))
    )
    (net (code "103") (name "Net-(U5-~{MR})") (class "Default")
      (node (ref "R88") (pin "2") (pinfunction "2_2") (pintype "passive"))
      (node (ref "U5") (pin "3") (pinfunction "~{MR}_3") (pintype "bidirectional"))
      (node (ref "WD_A_MR") (pin "TP") (pinfunction "TP_TP") (pintype "input"))
    )
    (net (code "104") (name "Net-(U5-~{RESET})") (class "Default")
      (node (ref "R13") (pin "1") (pinfunction "1_1") (pintype "passive"))
      (node (ref "U5") (pin "1") (pinfunction "~{RESET}_1") (pintype "bidirectional"))
    )
    (net (code "105") (name "Net-(U6-~{MR})") (class "Default")
      (node (ref "R89") (pin "2") (pinfunction "2_2") (pintype "passive"))
      (node (ref "U6") (pin "3") (pinfunction "~{MR}_3") (pintype "bidirectional"))
      (node (ref "WD_B_MR") (pin "TP") (pinfunction "TP_TP") (pintype "input"))
    )
    (net (code "106") (name "Net-(U6-~{RESET})") (class "Default")
      (node (ref "R14") (pin "1") (pinfunction "1_1") (pintype "passive"))
      (node (ref "U6") (pin "1") (pinfunction "~{RESET}_1") (pintype "bidirectional"))
    )
    (net (code "107") (name "Net-(U7-COMP_FSET)") (class "Default")
      (node (ref "R58") (pin "2") (pinfunction "2_2") (pintype "passive"))
      (node (ref "U7") (pin "7") (pinfunction "COMP_FSET_7") (pintype "input"))
    )
    (net (code "108") (name "Net-(U7-SS_TR)") (class "Default")
      (node (ref "C11") (pin "1") (pinfunction "1_1") (pintype "passive"))
      (node (ref "U7") (pin "6") (pinfunction "SS_TR_6") (pintype "input"))
    )
    (net (code "109") (name "Net-(U7-SW)") (class "Default")
      (node (ref "L1") (pin "1") (pinfunction "1_1") (pintype "passive"))
      (node (ref "U7") (pin "3") (pinfunction "SW_3") (pintype "power_in"))
    )
    (net (code "110") (name "Net-(U8-CFG_SEL2)") (class "Default")
      (node (ref "R24") (pin "2") (pinfunction "2_2") (pintype "passive"))
      (node (ref "R25") (pin "1") (pinfunction "1_1") (pintype "passive"))
      (node (ref "U8") (pin "13") (pinfunction "CFG_SEL2_13") (pintype "input"))
    )
    (net (code "111") (name "Net-(U8-HS_IND{slash}CFG_SEL1)") (class "Default")
      (node (ref "R22") (pin "2") (pinfunction "2_2") (pintype "passive"))
      (node (ref "R23") (pin "1") (pinfunction "1_1") (pintype "passive"))
      (node (ref "U8") (pin "42") (pinfunction "HS_IND/CFG_SEL1_42") (pintype "bidirectional"))
    )
    (net (code "112") (name "Net-(U8-LED_A1_N{slash}PRT_SWP1)") (class "Default")
      (node (ref "IR1") (pin "C") (pinfunction "C_C") (pintype "passive"))
      (node (ref "U8") (pin "51") (pinfunction "LED_A1_N/PRT_SWP1_51") (pintype "bidirectional"))
    )
    (net (code "113") (name "Net-(U8-LED_A2_N{slash}PRT_SWP2)") (class "Default")
      (node (ref "IR2") (pin "C") (pinfunction "C_C") (pintype "passive"))
      (node (ref "U8") (pin "49") (pinfunction "LED_A2_N/PRT_SWP2_49") (pintype "bidirectional"))
    )
    (net (code "114") (name "Net-(U8-LED_A3_N{slash}PRT_SWP3)") (class "Default")
      (node (ref "U8") (pin "47") (pinfunction "LED_A3_N/PRT_SWP3_47") (pintype "bidirectional"))
      (node (ref "VIS") (pin "C") (pinfunction "C_C") (pintype "passive"))
    )
    (net (code "115") (name "Net-(U8-LED_A4_N{slash}PRT_SWP4)") (class "Default")
      (node (ref "TILE") (pin "C") (pinfunction "C_C") (pintype "passive"))
      (node (ref "U8") (pin "33") (pinfunction "LED_A4_N/PRT_SWP4_33") (pintype "bidirectional"))
    )
    (net (code "116") (name "Net-(U8-LED_A5_N{slash}PRT_SWP5)") (class "Default")
      (node (ref "GPS") (pin "C") (pinfunction "C_C") (pintype "passive"))
      (node (ref "U8") (pin "31") (pinfunction "LED_A5_N/PRT_SWP5_31") (pintype "bidirectional"))
    )
    (net (code "117") (name "Net-(U8-LED_A6_N{slash}PRT_SWP6)") (class "Default")
      (node (ref "DEBUG") (pin "C") (pinfunction "C_C") (pintype "passive"))
      (node (ref "U8") (pin "17") (pinfunction "LED_A6_N/PRT_SWP6_17") (pintype "bidirectional"))
    )
    (net (code "118") (name "Net-(U8-RBIAS)") (class "Default")
      (node (ref "R21") (pin "2") (pinfunction "2_2") (pintype "passive"))
      (node (ref "U8") (pin "63") (pinfunction "RBIAS_63") (pintype "input"))
    )
    (net (code "119") (name "Net-(U8-RESET_N)") (class "Default")
      (node (ref "R29") (pin "1") (pinfunction "1_1") (pintype "passive"))
      (node (ref "U8") (pin "43") (pinfunction "RESET_N_43") (pintype "input"))
    )
    (net (code "120") (name "Net-(U8-SCL{slash}SMBCLK{slash}CFG_SEL0)") (class "Default")
      (node (ref "R26") (pin "2") (pinfunction "2_2") (pintype "passive"))
      (node (ref "R27") (pin "1") (pinfunction "1_1") (pintype "passive"))
      (node (ref "U8") (pin "41") (pinfunction "SCL/SMBCLK/CFG_SEL0_41") (pintype "bidirectional"))
    )
    (net (code "121") (name "Net-(U8-SDA{slash}SMBDATA{slash}NON_REM1)") (class "Default")
      (node (ref "R1") (pin "1") (pinfunction "1_1") (pintype "passive"))
      (node (ref "U8") (pin "40") (pinfunction "SDA/SMBDATA/NON_REM1_40") (pintype "bidirectional"))
    )
    (net (code "122") (name "Net-(U8-SUSP_IND{slash}LOCAL_PWR{slash}NON_REM0)") (class "Default")
      (node (ref "R2") (pin "2") (pinfunction "2_2") (pintype "passive"))
      (node (ref "U8") (pin "45") (pinfunction "SUSP_IND/LOCAL_PWR/NON_REM0_45") (pintype "bidirectional"))
      (node (ref "USB_SUSP_IND") (pin "TP") (pinfunction "TP_TP") (pintype "input"))
    )
    (net (code "123") (name "Net-(U8-USBDN7_DM{slash}PRT_DIS_M7)") (class "Default")
      (node (ref "R19") (pin "1") (pinfunction "1_1") (pintype "passive"))
      (node (ref "U8") (pin "55") (pinfunction "USBDN7_DM/PRT_DIS_M7_55") (pintype "bidirectional"))
    )
    (net (code "124") (name "Net-(U8-USBDN7_DP{slash}PRT_DIS_P7)") (class "Default")
      (node (ref "R20") (pin "1") (pinfunction "1_1") (pintype "passive"))
      (node (ref "U8") (pin "56") (pinfunction "USBDN7_DP/PRT_DIS_P7_56") (pintype "bidirectional"))
    )
    (net (code "125") (name "Net-(U8-VDD18)") (class "Default")
      (node (ref "C38") (pin "1") (pinfunction "1_1") (pintype "passive"))
      (node (ref "U8") (pin "25") (pinfunction "VDD18_25") (pintype "power_in"))
    )
    (net (code "126") (name "Net-(U8-VDD18PLL)") (class "Default")
      (node (ref "C39") (pin "1") (pinfunction "1_1") (pintype "passive"))
      (node (ref "U8") (pin "62") (pinfunction "VDD18PLL_62") (pintype "power_in"))
    )
    (net (code "127") (name "Net-(U8-XTAL1{slash}CLKIN)") (class "Default")
      (node (ref "C36") (pin "1") (pinfunction "1_1") (pintype "passive"))
      (node (ref "R28") (pin "2") (pinfunction "2_2") (pintype "passive"))
      (node (ref "U18") (pin "IN") (pinfunction "IN_IN") (pintype "bidirectional"))
      (node (ref "U8") (pin "61") (pinfunction "XTAL1/CLKIN_61") (pintype "input"))
    )
    (net (code "128") (name "Net-(U8-XTAL2)") (class "Default")
      (node (ref "C37") (pin "2") (pinfunction "2_2") (pintype "passive"))
      (node (ref "R28") (pin "1") (pinfunction "1_1") (pintype "passive"))
      (node (ref "U18") (pin "OUT") (pinfunction "OUT_OUT") (pintype "bidirectional"))
      (node (ref "U8") (pin "60") (pinfunction "XTAL2_60") (pintype "output"))
    )
    (net (code "129") (name "Net-(U11-1CLK)") (class "Default")
      (node (ref "U11") (pin "21") (pinfunction "1CLK_21") (pintype "bidirectional"))
      (node (ref "U14") (pin "14") (pinfunction "2CLK_14") (pintype "bidirectional"))
      (node (ref "X1") (pin "5") (pinfunction "CLK_5") (pintype "bidirectional"))
    )
    (net (code "130") (name "Net-(U11-1CMD)") (class "Default")
      (node (ref "R36") (pin "1") (pinfunction "1_1") (pintype "passive"))
      (node (ref "U11") (pin "23") (pinfunction "1CMD_23") (pintype "bidirectional"))
      (node (ref "U14") (pin "16") (pinfunction "2CMD_16") (pintype "bidirectional"))
      (node (ref "X1") (pin "3") (pinfunction "CMD_3") (pintype "bidirectional"))
    )
    (net (code "131") (name "Net-(U11-1DAT[0])") (class "Default")
      (node (ref "R41") (pin "1") (pinfunction "1_1") (pintype "passive"))
      (node (ref "U11") (pin "20") (pinfunction "1DAT[0]_20") (pintype "bidirectional"))
      (node (ref "U14") (pin "13") (pinfunction "2DAT[0]_13") (pintype "bidirectional"))
      (node (ref "X1") (pin "7") (pinfunction "DAT0_7") (pintype "bidirectional"))
    )
    (net (code "132") (name "Net-(U11-1DAT[1])") (class "Default")
      (node (ref "R42") (pin "1") (pinfunction "1_1") (pintype "passive"))
      (node (ref "U11") (pin "19") (pinfunction "1DAT[1]_19") (pintype "bidirectional"))
      (node (ref "U14") (pin "12") (pinfunction "2DAT[1]_12") (pintype "bidirectional"))
      (node (ref "X1") (pin "8") (pinfunction "DAT1_8") (pintype "bidirectional"))
    )
    (net (code "133") (name "Net-(U11-1DAT[2])") (class "Default")
      (node (ref "R34") (pin "1") (pinfunction "1_1") (pintype "passive"))
      (node (ref "U11") (pin "1") (pinfunction "1DAT[2]_1") (pintype "bidirectional"))
      (node (ref "U14") (pin "18") (pinfunction "2DAT[2]_18") (pintype "bidirectional"))
      (node (ref "X1") (pin "1") (pinfunction "DAT2_1") (pintype "bidirectional"))
    )
    (net (code "134") (name "Net-(U11-1DAT[3])") (class "Default")
      (node (ref "R35") (pin "1") (pinfunction "1_1") (pintype "passive"))
      (node (ref "U11") (pin "24") (pinfunction "1DAT[3]_24") (pintype "bidirectional"))
      (node (ref "U14") (pin "17") (pinfunction "2DAT[3]_17") (pintype "bidirectional"))
      (node (ref "X1") (pin "2") (pinfunction "CD/DAT3_2") (pintype "bidirectional"))
    )
    (net (code "135") (name "Net-(U11-2CLK)") (class "Default")
      (node (ref "U11") (pin "14") (pinfunction "2CLK_14") (pintype "bidirectional"))
      (node (ref "U14") (pin "21") (pinfunction "1CLK_21") (pintype "bidirectional"))
      (node (ref "X2") (pin "5") (pinfunction "CLK_5") (pintype "bidirectional"))
    )
    (net (code "136") (name "Net-(U11-2CMD)") (class "Default")
      (node (ref "R50") (pin "1") (pinfunction "1_1") (pintype "passive"))
      (node (ref "U11") (pin "16") (pinfunction "2CMD_16") (pintype "bidirectional"))
      (node (ref "U14") (pin "23") (pinfunction "1CMD_23") (pintype "bidirectional"))
      (node (ref "X2") (pin "3") (pinfunction "CMD_3") (pintype "bidirectional"))
    )
    (net (code "137") (name "Net-(U11-2DAT[0])") (class "Default")
      (node (ref "R51") (pin "1") (pinfunction "1_1") (pintype "passive"))
      (node (ref "U11") (pin "13") (pinfunction "2DAT[0]_13") (pintype "bidirectional"))
      (node (ref "U14") (pin "20") (pinfunction "1DAT[0]_20") (pintype "bidirectional"))
      (node (ref "X2") (pin "7") (pinfunction "DAT0_7") (pintype "bidirectional"))
    )
    (net (code "138") (name "Net-(U11-2DAT[1])") (class "Default")
      (node (ref "R52") (pin "1") (pinfunction "1_1") (pintype "passive"))
      (node (ref "U11") (pin "12") (pinfunction "2DAT[1]_12") (pintype "bidirectional"))
      (node (ref "U14") (pin "19") (pinfunction "1DAT[1]_19") (pintype "bidirectional"))
      (node (ref "X2") (pin "8") (pinfunction "DAT1_8") (pintype "bidirectional"))
    )
    (net (code "139") (name "Net-(U11-2DAT[2])") (class "Default")
      (node (ref "R49") (pin "1") (pinfunction "1_1") (pintype "passive"))
      (node (ref "U11") (pin "18") (pinfunction "2DAT[2]_18") (pintype "bidirectional"))
      (node (ref "U14") (pin "1") (pinfunction "1DAT[2]_1") (pintype "bidirectional"))
      (node (ref "X2") (pin "1") (pinfunction "DAT2_1") (pintype "bidirectional"))
    )
    (net (code "140") (name "Net-(U11-2DAT[3])") (class "Default")
      (node (ref "R48") (pin "1") (pinfunction "1_1") (pintype "passive"))
      (node (ref "U11") (pin "17") (pinfunction "2DAT[3]_17") (pintype "bidirectional"))
      (node (ref "U14") (pin "24") (pinfunction "1DAT[3]_24") (pintype "bidirectional"))
      (node (ref "X2") (pin "2") (pinfunction "CD/DAT3_2") (pintype "bidirectional"))
    )
    (net (code "141") (name "Net-(U12-X1)") (class "Default")
      (node (ref "C53") (pin "1") (pinfunction "1_1") (pintype "passive"))
      (node (ref "U12") (pin "1") (pinfunction "X1_1") (pintype "input"))
      (node (ref "X4") (pin "2") (pinfunction "P2_2") (pintype "bidirectional"))
    )
    (net (code "142") (name "Net-(U12-X2)") (class "Default")
      (node (ref "C54") (pin "2") (pinfunction "2_2") (pintype "passive"))
      (node (ref "U12") (pin "2") (pinfunction "X2_2") (pintype "output"))
      (node (ref "X4") (pin "1") (pinfunction "P1_1") (pintype "bidirectional"))
    )
    (net (code "143") (name "Net-(U13-1CLK)") (class "Default")
      (node (ref "U13") (pin "21") (pinfunction "1CLK_21") (pintype "bidirectional"))
      (node (ref "U4") (pin "14") (pinfunction "2CLK_14") (pintype "bidirectional"))
      (node (ref "X5") (pin "5") (pinfunction "CLK_5") (pintype "bidirectional"))
    )
    (net (code "144") (name "Net-(U13-1CMD)") (class "Default")
      (node (ref "R45") (pin "1") (pinfunction "1_1") (pintype "passive"))
      (node (ref "U13") (pin "23") (pinfunction "1CMD_23") (pintype "bidirectional"))
      (node (ref "U4") (pin "16") (pinfunction "2CMD_16") (pintype "bidirectional"))
      (node (ref "X5") (pin "3") (pinfunction "CMD_3") (pintype "bidirectional"))
    )
    (net (code "145") (name "Net-(U13-1DAT[0])") (class "Default")
      (node (ref "R46") (pin "1") (pinfunction "1_1") (pintype "passive"))
      (node (ref "U13") (pin "20") (pinfunction "1DAT[0]_20") (pintype "bidirectional"))
      (node (ref "U4") (pin "13") (pinfunction "2DAT[0]_13") (pintype "bidirectional"))
      (node (ref "X5") (pin "7") (pinfunction "DAT0_7") (pintype "bidirectional"))
    )
    (net (code "146") (name "Net-(U13-1DAT[1])") (class "Default")
      (node (ref "R47") (pin "1") (pinfunction "1_1") (pintype "passive"))
      (node (ref "U13") (pin "19") (pinfunction "1DAT[1]_19") (pintype "bidirectional"))
      (node (ref "U4") (pin "12") (pinfunction "2DAT[1]_12") (pintype "bidirectional"))
      (node (ref "X5") (pin "8") (pinfunction "DAT1_8") (pintype "bidirectional"))
    )
    (net (code "147") (name "Net-(U13-1DAT[2])") (class "Default")
      (node (ref "R44") (pin "1") (pinfunction "1_1") (pintype "passive"))
      (node (ref "U13") (pin "1") (pinfunction "1DAT[2]_1") (pintype "bidirectional"))
      (node (ref "U4") (pin "18") (pinfunction "2DAT[2]_18") (pintype "bidirectional"))
      (node (ref "X5") (pin "1") (pinfunction "DAT2_1") (pintype "bidirectional"))
    )
    (net (code "148") (name "Net-(U13-1DAT[3])") (class "Default")
      (node (ref "R43") (pin "1") (pinfunction "1_1") (pintype "passive"))
      (node (ref "U13") (pin "24") (pinfunction "1DAT[3]_24") (pintype "bidirectional"))
      (node (ref "U4") (pin "17") (pinfunction "2DAT[3]_17") (pintype "bidirectional"))
      (node (ref "X5") (pin "2") (pinfunction "CD/DAT3_2") (pintype "bidirectional"))
    )
    (net (code "149") (name "Net-(U13-2CLK)") (class "Default")
      (node (ref "U13") (pin "14") (pinfunction "2CLK_14") (pintype "bidirectional"))
      (node (ref "U4") (pin "21") (pinfunction "1CLK_21") (pintype "bidirectional"))
      (node (ref "X6") (pin "5") (pinfunction "CLK_5") (pintype "bidirectional"))
    )
    (net (code "150") (name "Net-(U13-2CMD)") (class "Default")
      (node (ref "R55") (pin "1") (pinfunction "1_1") (pintype "passive"))
      (node (ref "U13") (pin "16") (pinfunction "2CMD_16") (pintype "bidirectional"))
      (node (ref "U4") (pin "23") (pinfunction "1CMD_23") (pintype "bidirectional"))
      (node (ref "X6") (pin "3") (pinfunction "CMD_3") (pintype "bidirectional"))
    )
    (net (code "151") (name "Net-(U13-2DAT[0])") (class "Default")
      (node (ref "R56") (pin "1") (pinfunction "1_1") (pintype "passive"))
      (node (ref "U13") (pin "13") (pinfunction "2DAT[0]_13") (pintype "bidirectional"))
      (node (ref "U4") (pin "20") (pinfunction "1DAT[0]_20") (pintype "bidirectional"))
      (node (ref "X6") (pin "7") (pinfunction "DAT0_7") (pintype "bidirectional"))
    )
    (net (code "152") (name "Net-(U13-2DAT[1])") (class "Default")
      (node (ref "R57") (pin "1") (pinfunction "1_1") (pintype "passive"))
      (node (ref "U13") (pin "12") (pinfunction "2DAT[1]_12") (pintype "bidirectional"))
      (node (ref "U4") (pin "19") (pinfunction "1DAT[1]_19") (pintype "bidirectional"))
      (node (ref "X6") (pin "8") (pinfunction "DAT1_8") (pintype "bidirectional"))
    )
    (net (code "153") (name "Net-(U13-2DAT[2])") (class "Default")
      (node (ref "R54") (pin "1") (pinfunction "1_1") (pintype "passive"))
      (node (ref "U13") (pin "18") (pinfunction "2DAT[2]_18") (pintype "bidirectional"))
      (node (ref "U4") (pin "1") (pinfunction "1DAT[2]_1") (pintype "bidirectional"))
      (node (ref "X6") (pin "1") (pinfunction "DAT2_1") (pintype "bidirectional"))
    )
    (net (code "154") (name "Net-(U13-2DAT[3])") (class "Default")
      (node (ref "R53") (pin "1") (pinfunction "1_1") (pintype "passive"))
      (node (ref "U13") (pin "17") (pinfunction "2DAT[3]_17") (pintype "bidirectional"))
      (node (ref "U4") (pin "24") (pinfunction "1DAT[3]_24") (pintype "bidirectional"))
      (node (ref "X6") (pin "2") (pinfunction "CD/DAT3_2") (pintype "bidirectional"))
    )
    (net (code "155") (name "Net-(U15-COMP_FSET)") (class "Default")
      (node (ref "R60") (pin "2") (pinfunction "2_2") (pintype "passive"))
      (node (ref "U15") (pin "7") (pinfunction "COMP_FSET_7") (pintype "input"))
    )
    (net (code "156") (name "Net-(U15-SS_TR)") (class "Default")
      (node (ref "C14") (pin "1") (pinfunction "1_1") (pintype "passive"))
      (node (ref "U15") (pin "6") (pinfunction "SS_TR_6") (pintype "input"))
    )
    (net (code "157") (name "Net-(U15-SW)") (class "Default")
      (node (ref "L2") (pin "1") (pinfunction "1_1") (pintype "passive"))
      (node (ref "U15") (pin "3") (pinfunction "SW_3") (pintype "power_in"))
    )
    (net (code "158") (name "Net-(U16-COMP_FSET)") (class "Default")
      (node (ref "R78") (pin "2") (pinfunction "2_2") (pintype "passive"))
      (node (ref "U16") (pin "7") (pinfunction "COMP_FSET_7") (pintype "input"))
    )
    (net (code "159") (name "Net-(U16-FB)") (class "Default")
      (node (ref "C16") (pin "2") (pinfunction "2_2") (pintype "passive"))
      (node (ref "R76") (pin "1") (pinfunction "1_1") (pintype "passive"))
      (node (ref "R77") (pin "2") (pinfunction "2_2") (pintype "passive"))
      (node (ref "U16") (pin "5") (pinfunction "FB_5") (pintype "input"))
    )
    (net (code "160") (name "Net-(U16-SS_TR)") (class "Default")
      (node (ref "C19") (pin "1") (pinfunction "1_1") (pintype "passive"))
      (node (ref "U16") (pin "6") (pinfunction "SS_TR_6") (pintype "input"))
    )
    (net (code "161") (name "Net-(U16-SW)") (class "Default")
      (node (ref "L4") (pin "1") (pinfunction "1_1") (pintype "passive"))
      (node (ref "U16") (pin "3") (pinfunction "SW_3") (pintype "power_in"))
    )
    (net (code "162") (name "Net-(U17-COMP_FSET)") (class "Default")
      (node (ref "R82") (pin "2") (pinfunction "2_2") (pintype "passive"))
      (node (ref "U17") (pin "7") (pinfunction "COMP_FSET_7") (pintype "input"))
    )
    (net (code "163") (name "Net-(U17-FB)") (class "Default")
      (node (ref "C24") (pin "2") (pinfunction "2_2") (pintype "passive"))
      (node (ref "R80") (pin "1") (pinfunction "1_1") (pintype "passive"))
      (node (ref "R81") (pin "2") (pinfunction "2_2") (pintype "passive"))
      (node (ref "U17") (pin "5") (pinfunction "FB_5") (pintype "input"))
    )
    (net (code "164") (name "Net-(U17-SS_TR)") (class "Default")
      (node (ref "C63") (pin "1") (pinfunction "1_1") (pintype "passive"))
      (node (ref "U17") (pin "6") (pinfunction "SS_TR_6") (pintype "input"))
    )
    (net (code "165") (name "Net-(U17-SW)") (class "Default")
      (node (ref "L3") (pin "1") (pinfunction "1_1") (pintype "passive"))
      (node (ref "U17") (pin "3") (pinfunction "SW_3") (pintype "power_in"))
    )
    (net (code "166") (name "Net-(U19-Y)") (class "Default")
      (node (ref "U19") (pin "4") (pinfunction "Y_4") (pintype "bidirectional"))
      (node (ref "U3") (pin "24") (pinfunction "SDA/SDI_24") (pintype "bidirectional"))
    )
    (net (code "167") (name "Net-(U22-Y)") (class "Default")
      (node (ref "U22") (pin "4") (pinfunction "Y_4") (pintype "bidirectional"))
      (node (ref "U3") (pin "22") (pinfunction "NCS_22") (pintype "input"))
    )
    (net (code "168") (name "RPIA_BB_BUSY") (class "Default")
      (node (ref "S10") (pin "9") (pinfunction "HSD2+_9") (pintype "bidirectional"))
      (node (ref "U20") (pin "28") (pinfunction "GPIO28_28") (pintype "bidirectional"))
    )
    (net (code "169") (name "RPIA_BB_WDG") (class "Default")
      (node (ref "S10") (pin "8") (pinfunction "HSD2-_8") (pintype "bidirectional"))
      (node (ref "U20") (pin "30") (pinfunction "GPIO29_30") (pintype "bidirectional"))
    )
    (net (code "170") (name "RPIA_I2C_0_SCL") (class "Default")
      (node (ref "PIA_I2C_0_C") (pin "TP") (pinfunction "TP_TP") (pintype "input"))
      (node (ref "S8") (pin "8") (pinfunction "HSD2-_8") (pintype "bidirectional"))
      (node (ref "U20") (pin "5") (pinfunction "GPIO1_5") (pintype "bidirectional"))
    )
    (net (code "171") (name "RPIA_I2C_0_SDA") (class "Default")
      (node (ref "PIA_I2C_0_D") (pin "TP") (pinfunction "TP_TP") (pintype "input"))
      (node (ref "S8") (pin "9") (pinfunction "HSD2+_9") (pintype "bidirectional"))
      (node (ref "U20") (pin "3") (pinfunction "GPIO0_3") (pintype "bidirectional"))
    )
    (net (code "172") (name "RPIA_I2C_1_SCL") (class "Default")
      (node (ref "PIA_I2C_1_C") (pin "TP") (pinfunction "TP_TP") (pintype "input"))
      (node (ref "S9") (pin "8") (pinfunction "HSD2-_8") (pintype "bidirectional"))
      (node (ref "U20") (pin "11") (pinfunction "GPIO3_11") (pintype "bidirectional"))
    )
    (net (code "173") (name "RPIA_I2C_1_SDA") (class "Default")
      (node (ref "PIA_I2C_1_D") (pin "TP") (pinfunction "TP_TP") (pintype "input"))
      (node (ref "S9") (pin "9") (pinfunction "HSD2+_9") (pintype "bidirectional"))
      (node (ref "U20") (pin "9") (pinfunction "GPIO2_9") (pintype "bidirectional"))
    )
    (net (code "174") (name "RPIA_MUX1_SD_CLK") (class "Default")
      (node (ref "U14") (pin "8") (pinfunction "CLK_8") (pintype "bidirectional"))
      (node (ref "U20") (pin "10") (pinfunction "SDX_CLK_10") (pintype "bidirectional"))
    )
    (net (code "175") (name "RPIA_MUX1_SD_CMD") (class "Default")
      (node (ref "U14") (pin "5") (pinfunction "CMD_5") (pintype "bidirectional"))
      (node (ref "U20") (pin "12") (pinfunction "SDX_CMD_12") (pintype "bidirectional"))
    )
    (net (code "176") (name "RPIA_MUX1_SD_D0") (class "Default")
      (node (ref "U14") (pin "9") (pinfunction "DAT[0]_9") (pintype "bidirectional"))
      (node (ref "U20") (pin "16") (pinfunction "SDX_D0_16") (pintype "bidirectional"))
    )
    (net (code "177") (name "RPIA_MUX1_SD_D1") (class "Default")
      (node (ref "U14") (pin "10") (pinfunction "DAT[1]_10") (pintype "bidirectional"))
      (node (ref "U20") (pin "18") (pinfunction "SDX_D1_18") (pintype "bidirectional"))
    )
    (net (code "178") (name "RPIA_MUX1_SD_D2") (class "Default")
      (node (ref "U14") (pin "3") (pinfunction "DAT[2]_3") (pintype "bidirectional"))
      (node (ref "U20") (pin "22") (pinfunction "SDX_D2_22") (pintype "bidirectional"))
    )
    (net (code "179") (name "RPIA_MUX1_SD_D3") (class "Default")
      (node (ref "U14") (pin "4") (pinfunction "DAT[3]_4") (pintype "bidirectional"))
      (node (ref "U20") (pin "24") (pinfunction "SDX_D3_24") (pintype "bidirectional"))
    )
    (net (code "180") (name "RPIA_MUX2_SD_CLK") (class "Default")
      (node (ref "U11") (pin "8") (pinfunction "CLK_8") (pintype "bidirectional"))
      (node (ref "U20") (pin "75") (pinfunction "GPIO22_75") (pintype "bidirectional"))
    )
    (net (code "181") (name "RPIA_MUX2_SD_CMD") (class "Default")
      (node (ref "U11") (pin "5") (pinfunction "CMD_5") (pintype "bidirectional"))
      (node (ref "U20") (pin "77") (pinfunction "GPIO23_77") (pintype "bidirectional"))
    )
    (net (code "182") (name "RPIA_MUX2_SD_D0") (class "Default")
      (node (ref "U11") (pin "9") (pinfunction "DAT[0]_9") (pintype "bidirectional"))
      (node (ref "U20") (pin "81") (pinfunction "GPIO24_81") (pintype "bidirectional"))
    )
    (net (code "183") (name "RPIA_MUX2_SD_D1") (class "Default")
      (node (ref "U11") (pin "10") (pinfunction "DAT[1]_10") (pintype "bidirectional"))
      (node (ref "U20") (pin "83") (pinfunction "GPIO25_83") (pintype "bidirectional"))
    )
    (net (code "184") (name "RPIA_MUX2_SD_D2") (class "Default")
      (node (ref "U11") (pin "3") (pinfunction "DAT[2]_3") (pintype "bidirectional"))
      (node (ref "U20") (pin "87") (pinfunction "GPIO26_87") (pintype "bidirectional"))
    )
    (net (code "185") (name "RPIA_MUX2_SD_D3") (class "Default")
      (node (ref "U11") (pin "4") (pinfunction "DAT[3]_4") (pintype "bidirectional"))
      (node (ref "U20") (pin "89") (pinfunction "GPIO27_89") (pintype "bidirectional"))
    )
    (net (code "186") (name "RPIA_RUN") (class "Default")
      (node (ref "C2") (pin "1") (pinfunction "1_1") (pintype "passive"))
      (node (ref "IC4") (pin "4") (pinfunction "O_4") (pintype "output"))
      (node (ref "LST_SEL") (pin "TP") (pinfunction "TP_TP") (pintype "input"))
      (node (ref "PIA_RUN") (pin "P$1") (pinfunction "P1_P$1") (pintype "bidirectional"))
      (node (ref "R73") (pin "1") (pinfunction "1_1") (pintype "passive"))
      (node (ref "S10") (pin "2") (pinfunction "SEL_2") (pintype "bidirectional"))
      (node (ref "S4") (pin "2") (pinfunction "SEL_2") (pintype "bidirectional"))
      (node (ref "S6") (pin "2") (pinfunction "SEL_2") (pintype "bidirectional"))
      (node (ref "S7") (pin "2") (pinfunction "SEL_2") (pintype "bidirectional"))
      (node (ref "S8") (pin "2") (pinfunction "SEL_2") (pintype "bidirectional"))
      (node (ref "S9") (pin "2") (pinfunction "SEL_2") (pintype "bidirectional"))
      (node (ref "S_USB_RPI") (pin "P$1") (pinfunction "P1_P$1") (pintype "bidirectional"))
      (node (ref "U20") (pin "177") (pinfunction "RUN_177") (pintype "bidirectional"))
    )
    (net (code "187") (name "RPIA_SD_SEL") (class "Default")
      (node (ref "IC7") (pin "5") (pinfunction "Q_5") (pintype "output"))
      (node (ref "PIA_SD_SEL") (pin "P$1") (pinfunction "P1_P$1") (pintype "bidirectional"))
      (node (ref "R66") (pin "1") (pinfunction "1_1") (pintype "passive"))
      (node (ref "R68") (pin "1") (pinfunction "1_1") (pintype "passive"))
      (node (ref "U11") (pin "11") (pinfunction "S_11") (pintype "bidirectional"))
      (node (ref "U14") (pin "11") (pinfunction "S_11") (pintype "bidirectional"))
    )
    (net (code "188") (name "RPIA_SPI0_CS_IMU") (class "Default")
      (node (ref "U20") (pin "27") (pinfunction "GPIO8_27") (pintype "bidirectional"))
      (node (ref "U22") (pin "2") (pinfunction "A_2") (pintype "bidirectional"))
    )
    (net (code "189") (name "RPIA_SPI0_SCLK") (class "Default")
      (node (ref "U2") (pin "2") (pinfunction "A_2") (pintype "bidirectional"))
      (node (ref "U20") (pin "35") (pinfunction "GPIO11_35") (pintype "bidirectional"))
    )
    (net (code "190") (name "RPIA_SPI0_SDI") (class "Default")
      (node (ref "U19") (pin "2") (pinfunction "A_2") (pintype "bidirectional"))
      (node (ref "U20") (pin "33") (pinfunction "GPIO10_33") (pintype "bidirectional"))
    )
    (net (code "191") (name "RPIA_SPI0_SDO") (class "Default")
      (node (ref "U20") (pin "29") (pinfunction "GPIO9_29") (pintype "bidirectional"))
      (node (ref "U3") (pin "9") (pinfunction "AD0/SDO_9") (pintype "output"))
    )
    (net (code "192") (name "RPIA_UART_RX_0") (class "Default")
      (node (ref "RPIA_RX_LST") (pin "P$1") (pinfunction "P1_P$1") (pintype "bidirectional"))
      (node (ref "S6") (pin "8") (pinfunction "HSD2-_8") (pintype "bidirectional"))
      (node (ref "U20") (pin "53") (pinfunction "GPIO15_53") (pintype "bidirectional"))
    )
    (net (code "193") (name "RPIA_UART_RX_1") (class "Default")
      (node (ref "S7") (pin "8") (pinfunction "HSD2-_8") (pintype "bidirectional"))
      (node (ref "U20") (pin "48") (pinfunction "GPIO33_48") (pintype "bidirectional"))
    )
    (net (code "194") (name "RPIA_UART_TX_0") (class "Default")
      (node (ref "RPIA_TX_LST") (pin "P$1") (pinfunction "P1_P$1") (pintype "bidirectional"))
      (node (ref "S6") (pin "9") (pinfunction "HSD2+_9") (pintype "bidirectional"))
      (node (ref "U20") (pin "51") (pinfunction "GPIO14_51") (pintype "bidirectional"))
    )
    (net (code "195") (name "RPIA_UART_TX_1") (class "Default")
      (node (ref "S7") (pin "9") (pinfunction "HSD2+_9") (pintype "bidirectional"))
      (node (ref "U20") (pin "46") (pinfunction "GPIO32_46") (pintype "bidirectional"))
    )
    (net (code "196") (name "RPIA_USB_MUX_D_N") (class "Default")
      (node (ref "RPIA_USB_N") (pin "TP") (pinfunction "TP_TP") (pintype "input"))
      (node (ref "S4") (pin "8") (pinfunction "HSD2-_8") (pintype "bidirectional"))
      (node (ref "U20") (pin "82") (pinfunction "GPIO44_82") (pintype "bidirectional"))
    )
    (net (code "197") (name "RPIA_USB_MUX_D_P") (class "Default")
      (node (ref "RPIA_USB_P") (pin "TP") (pinfunction "TP_TP") (pintype "input"))
      (node (ref "S4") (pin "9") (pinfunction "HSD2+_9") (pintype "bidirectional"))
      (node (ref "U20") (pin "84") (pinfunction "GPIO45_84") (pintype "bidirectional"))
    )
    (net (code "198") (name "RPIB_BB_BUSY") (class "Default")
      (node (ref "S10") (pin "7") (pinfunction "HSD1+_7") (pintype "bidirectional"))
      (node (ref "U21") (pin "28") (pinfunction "GPIO28_28") (pintype "bidirectional"))
    )
    (net (code "199") (name "RPIB_BB_WDG") (class "Default")
      (node (ref "S10") (pin "6") (pinfunction "HSD1-_6") (pintype "bidirectional"))
      (node (ref "U21") (pin "30") (pinfunction "GPIO29_30") (pintype "bidirectional"))
    )
    (net (code "200") (name "RPIB_I2C_0_SCL") (class "Default")
      (node (ref "PIB_I2C_0_C") (pin "P$1") (pinfunction "P1_P$1") (pintype "bidirectional"))
      (node (ref "S8") (pin "6") (pinfunction "HSD1-_6") (pintype "bidirectional"))
      (node (ref "U21") (pin "5") (pinfunction "GPIO1_5") (pintype "bidirectional"))
    )
    (net (code "201") (name "RPIB_I2C_0_SDA") (class "Default")
      (node (ref "PIB_I2C_0_D") (pin "P$1") (pinfunction "P1_P$1") (pintype "bidirectional"))
      (node (ref "S8") (pin "7") (pinfunction "HSD1+_7") (pintype "bidirectional"))
      (node (ref "U21") (pin "3") (pinfunction "GPIO0_3") (pintype "bidirectional"))
    )
    (net (code "202") (name "RPIB_I2C_1_SCL") (class "Default")
      (node (ref "S9") (pin "6") (pinfunction "HSD1-_6") (pintype "bidirectional"))
      (node (ref "U21") (pin "11") (pinfunction "GPIO3_11") (pintype "bidirectional"))
    )
    (net (code "203") (name "RPIB_I2C_1_SDA") (class "Default")
      (node (ref "S9") (pin "7") (pinfunction "HSD1+_7") (pintype "bidirectional"))
      (node (ref "U21") (pin "9") (pinfunction "GPIO2_9") (pintype "bidirectional"))
    )
    (net (code "204") (name "RPIB_MUX1_SD_CLK") (class "Default")
      (node (ref "U21") (pin "10") (pinfunction "SDX_CLK_10") (pintype "bidirectional"))
      (node (ref "U4") (pin "8") (pinfunction "CLK_8") (pintype "bidirectional"))
    )
    (net (code "205") (name "RPIB_MUX1_SD_CMD") (class "Default")
      (node (ref "U21") (pin "12") (pinfunction "SDX_CMD_12") (pintype "bidirectional"))
      (node (ref "U4") (pin "5") (pinfunction "CMD_5") (pintype "bidirectional"))
    )
    (net (code "206") (name "RPIB_MUX1_SD_D0") (class "Default")
      (node (ref "U21") (pin "16") (pinfunction "SDX_D0_16") (pintype "bidirectional"))
      (node (ref "U4") (pin "9") (pinfunction "DAT[0]_9") (pintype "bidirectional"))
    )
    (net (code "207") (name "RPIB_MUX1_SD_D1") (class "Default")
      (node (ref "U21") (pin "18") (pinfunction "SDX_D1_18") (pintype "bidirectional"))
      (node (ref "U4") (pin "10") (pinfunction "DAT[1]_10") (pintype "bidirectional"))
    )
    (net (code "208") (name "RPIB_MUX1_SD_D2") (class "Default")
      (node (ref "U21") (pin "22") (pinfunction "SDX_D2_22") (pintype "bidirectional"))
      (node (ref "U4") (pin "3") (pinfunction "DAT[2]_3") (pintype "bidirectional"))
    )
    (net (code "209") (name "RPIB_MUX1_SD_D3") (class "Default")
      (node (ref "U21") (pin "24") (pinfunction "SDX_D3_24") (pintype "bidirectional"))
      (node (ref "U4") (pin "4") (pinfunction "DAT[3]_4") (pintype "bidirectional"))
    )
    (net (code "210") (name "RPIB_MUX2_SD_CLK") (class "Default")
      (node (ref "U13") (pin "8") (pinfunction "CLK_8") (pintype "bidirectional"))
      (node (ref "U21") (pin "75") (pinfunction "GPIO22_75") (pintype "bidirectional"))
    )
    (net (code "211") (name "RPIB_MUX2_SD_CMD") (class "Default")
      (node (ref "U13") (pin "5") (pinfunction "CMD_5") (pintype "bidirectional"))
      (node (ref "U21") (pin "77") (pinfunction "GPIO23_77") (pintype "bidirectional"))
    )
    (net (code "212") (name "RPIB_MUX2_SD_D0") (class "Default")
      (node (ref "U13") (pin "9") (pinfunction "DAT[0]_9") (pintype "bidirectional"))
      (node (ref "U21") (pin "81") (pinfunction "GPIO24_81") (pintype "bidirectional"))
    )
    (net (code "213") (name "RPIB_MUX2_SD_D1") (class "Default")
      (node (ref "U13") (pin "10") (pinfunction "DAT[1]_10") (pintype "bidirectional"))
      (node (ref "U21") (pin "83") (pinfunction "GPIO25_83") (pintype "bidirectional"))
    )
    (net (code "214") (name "RPIB_MUX2_SD_D2") (class "Default")
      (node (ref "U13") (pin "3") (pinfunction "DAT[2]_3") (pintype "bidirectional"))
      (node (ref "U21") (pin "87") (pinfunction "GPIO26_87") (pintype "bidirectional"))
    )
    (net (code "215") (name "RPIB_MUX2_SD_D3") (class "Default")
      (node (ref "U13") (pin "4") (pinfunction "DAT[3]_4") (pintype "bidirectional"))
      (node (ref "U21") (pin "89") (pinfunction "GPIO27_89") (pintype "bidirectional"))
    )
    (net (code "216") (name "RPIB_RUN") (class "Default")
      (node (ref "C1") (pin "1") (pinfunction "1_1") (pintype "passive"))
      (node (ref "IC5") (pin "4") (pinfunction "O_4") (pintype "output"))
      (node (ref "PIB_RUN") (pin "P$1") (pinfunction "P1_P$1") (pintype "bidirectional"))
      (node (ref "R74") (pin "1") (pinfunction "1_1") (pintype "passive"))
      (node (ref "U21") (pin "177") (pinfunction "RUN_177") (pintype "bidirectional"))
    )
    (net (code "217") (name "RPIB_SD_SEL") (class "Default")
      (node (ref "IC7") (pin "9") (pinfunction "Q_9") (pintype "output"))
      (node (ref "PIB_SD_SEL") (pin "P$1") (pinfunction "P1_P$1") (pintype "bidirectional"))
      (node (ref "R67") (pin "1") (pinfunction "1_1") (pintype "passive"))
      (node (ref "R69") (pin "1") (pinfunction "1_1") (pintype "passive"))
      (node (ref "U13") (pin "11") (pinfunction "S_11") (pintype "bidirectional"))
      (node (ref "U4") (pin "11") (pinfunction "S_11") (pintype "bidirectional"))
    )
    (net (code "218") (name "RPIB_SPI0_CS_IMU") (class "Default")
      (node (ref "U21") (pin "27") (pinfunction "GPIO8_27") (pintype "bidirectional"))
      (node (ref "U25") (pin "2") (pinfunction "A_2") (pintype "bidirectional"))
    )
    (net (code "219") (name "RPIB_SPI0_SCLK") (class "Default")
      (node (ref "U21") (pin "35") (pinfunction "GPIO11_35") (pintype "bidirectional"))
      (node (ref "U23") (pin "2") (pinfunction "A_2") (pintype "bidirectional"))
    )
    (net (code "220") (name "RPIB_SPI0_SDI") (class "Default")
      (node (ref "U21") (pin "33") (pinfunction "GPIO10_33") (pintype "bidirectional"))
      (node (ref "U24") (pin "2") (pinfunction "A_2") (pintype "bidirectional"))
    )
    (net (code "221") (name "RPIB_SPI0_SDO") (class "Default")
      (node (ref "U1") (pin "9") (pinfunction "AD0/SDO_9") (pintype "output"))
      (node (ref "U21") (pin "29") (pinfunction "GPIO9_29") (pintype "bidirectional"))
    )
    (net (code "222") (name "RPIB_UART_RX_0") (class "Default")
      (node (ref "S6") (pin "6") (pinfunction "HSD1-_6") (pintype "bidirectional"))
      (node (ref "U21") (pin "53") (pinfunction "GPIO15_53") (pintype "bidirectional"))
    )
    (net (code "223") (name "RPIB_UART_RX_1") (class "Default")
      (node (ref "S7") (pin "6") (pinfunction "HSD1-_6") (pintype "bidirectional"))
      (node (ref "U21") (pin "48") (pinfunction "GPIO33_48") (pintype "bidirectional"))
    )
    (net (code "224") (name "RPIB_UART_TX_0") (class "Default")
      (node (ref "S6") (pin "7") (pinfunction "HSD1+_7") (pintype "bidirectional"))
      (node (ref "U21") (pin "51") (pinfunction "GPIO14_51") (pintype "bidirectional"))
    )
    (net (code "225") (name "RPIB_UART_TX_1") (class "Default")
      (node (ref "S7") (pin "7") (pinfunction "HSD1+_7") (pintype "bidirectional"))
      (node (ref "U21") (pin "46") (pinfunction "GPIO32_46") (pintype "bidirectional"))
    )
    (net (code "226") (name "RPIB_USB_MUX_D_N") (class "Default")
      (node (ref "RPIB_USB_N") (pin "TP") (pinfunction "TP_TP") (pintype "input"))
      (node (ref "S4") (pin "6") (pinfunction "HSD1-_6") (pintype "bidirectional"))
      (node (ref "U21") (pin "82") (pinfunction "GPIO44_82") (pintype "bidirectional"))
    )
    (net (code "227") (name "RPIB_USB_MUX_D_P") (class "Default")
      (node (ref "RPIB_USB_P") (pin "TP") (pinfunction "TP_TP") (pintype "input"))
      (node (ref "S4") (pin "7") (pinfunction "HSD1+_7") (pintype "bidirectional"))
      (node (ref "U21") (pin "84") (pinfunction "GPIO45_84") (pintype "bidirectional"))
    )
    (net (code "228") (name "RPI_PWR_SEL") (class "Default")
      (node (ref "IC4") (pin "1") (pinfunction "I0_1") (pintype "input"))
      (node (ref "IC6") (pin "2") (pinfunction "I_2") (pintype "input"))
      (node (ref "J3") (pin "4") (pinfunction "4_4") (pintype "bidirectional"))
      (node (ref "LST_4") (pin "TP") (pinfunction "TP_TP") (pintype "input"))
      (node (ref "PI_PWR_SEL") (pin "P$1") (pinfunction "P1_P$1") (pintype "bidirectional"))
      (node (ref "R3") (pin "1") (pinfunction "1_1") (pintype "passive"))
      (node (ref "R5") (pin "1") (pinfunction "1_1") (pintype "passive"))
      (node (ref "R7") (pin "1") (pinfunction "1_1") (pintype "passive"))
      (node (ref "R88") (pin "1") (pinfunction "1_1") (pintype "passive"))
    )
    (net (code "229") (name "SPI1_CS_RTD1") (class "Default")
      (node (ref "H1-CONNECTOR1") (pin "1") (pinfunction "1_1") (pintype "bidirectional"))
      (node (ref "U20") (pin "57") (pinfunction "GPIO16_57") (pintype "bidirectional"))
      (node (ref "U21") (pin "57") (pinfunction "GPIO16_57") (pintype "bidirectional"))
    )
    (net (code "230") (name "SPI1_CS_RTD2") (class "Default")
      (node (ref "H1-CONNECTOR1") (pin "3") (pinfunction "3_3") (pintype "bidirectional"))
      (node (ref "U20") (pin "59") (pinfunction "GPIO17_59") (pintype "bidirectional"))
      (node (ref "U21") (pin "59") (pinfunction "GPIO17_59") (pintype "bidirectional"))
    )
    (net (code "231") (name "SPI1_CS_RTD3") (class "Default")
      (node (ref "H1-CONNECTOR1") (pin "5") (pinfunction "5_5") (pintype "bidirectional"))
      (node (ref "U20") (pin "63") (pinfunction "GPIO18_63") (pintype "bidirectional"))
      (node (ref "U21") (pin "63") (pinfunction "GPIO18_63") (pintype "bidirectional"))
    )
    (net (code "232") (name "SPI1_CS_RTD4") (class "Default")
      (node (ref "H1-CONNECTOR1") (pin "7") (pinfunction "7_7") (pintype "bidirectional"))
      (node (ref "U20") (pin "52") (pinfunction "GPIO34_52") (pintype "bidirectional"))
      (node (ref "U21") (pin "52") (pinfunction "GPIO34_52") (pintype "bidirectional"))
    )
    (net (code "233") (name "SPI1_CS_RTD5") (class "Default")
      (node (ref "H1-CONNECTOR1") (pin "9") (pinfunction "9_9") (pintype "bidirectional"))
      (node (ref "U20") (pin "54") (pinfunction "GPIO35_54") (pintype "bidirectional"))
      (node (ref "U21") (pin "54") (pinfunction "GPIO35_54") (pintype "bidirectional"))
    )
    (net (code "234") (name "SPI1_SCLK") (class "Default")
      (node (ref "H1-CONNECTOR1") (pin "17") (pinfunction "17_17") (pintype "bidirectional"))
      (node (ref "U20") (pin "71") (pinfunction "GPIO21_71") (pintype "bidirectional"))
      (node (ref "U21") (pin "71") (pinfunction "GPIO21_71") (pintype "bidirectional"))
    )
    (net (code "235") (name "SPI1_SDI") (class "Default")
      (node (ref "H1-CONNECTOR1") (pin "13") (pinfunction "13_13") (pintype "bidirectional"))
      (node (ref "U20") (pin "65") (pinfunction "GPIO19_65") (pintype "bidirectional"))
      (node (ref "U21") (pin "65") (pinfunction "GPIO19_65") (pintype "bidirectional"))
    )
    (net (code "236") (name "SPI1_SDO") (class "Default")
      (node (ref "H1-CONNECTOR1") (pin "15") (pinfunction "15_15") (pintype "bidirectional"))
      (node (ref "U20") (pin "69") (pinfunction "GPIO20_69") (pintype "bidirectional"))
      (node (ref "U21") (pin "69") (pinfunction "GPIO20_69") (pintype "bidirectional"))
    )
    (net (code "237") (name "THERM_ADC_CS") (class "Default")
      (node (ref "H1-CONNECTOR1") (pin "16") (pinfunction "16_16") (pintype "bidirectional"))
      (node (ref "U20") (pin "78") (pinfunction "GPIO43_78") (pintype "bidirectional"))
      (node (ref "U21") (pin "78") (pinfunction "GPIO43_78") (pintype "bidirectional"))
    )
    (net (code "238") (name "TILE_RX-TTL") (class "Default")
      (node (ref "IC3") (pin "1") (pinfunction "TXD_1") (pintype "output"))
      (node (ref "IC9") (pin "3") (pinfunction "DI_3") (pintype "input"))
      (node (ref "T_RX") (pin "P$1") (pinfunction "P1_P$1") (pintype "bidirectional"))
    )
    (net (code "239") (name "TILE_RX_N") (class "Default")
      (node (ref "J6") (pin "2") (pinfunction "2_2") (pintype "bidirectional"))
      (node (ref "RX_Y") (pin "1") (pinfunction "1_1") (pintype "passive"))
      (node (ref "RX_Z") (pin "3") (pinfunction "3_3") (pintype "passive"))
      (node (ref "TILE_2") (pin "TP") (pinfunction "TP_TP") (pintype "input"))
    )
    (net (code "240") (name "TILE_RX_P") (class "Default")
      (node (ref "J6") (pin "3") (pinfunction "3_3") (pintype "bidirectional"))
      (node (ref "RX_Y") (pin "3") (pinfunction "3_3") (pintype "passive"))
      (node (ref "RX_Z") (pin "1") (pinfunction "1_1") (pintype "passive"))
      (node (ref "TILE_3") (pin "TP") (pinfunction "TP_TP") (pintype "input"))
    )
    (net (code "241") (name "TILE_TX_N") (class "Default")
      (node (ref "J6") (pin "4") (pinfunction "4_4") (pintype "bidirectional"))
      (node (ref "TILE_4") (pin "TP") (pinfunction "TP_TP") (pintype "input"))
      (node (ref "TX_A") (pin "1") (pinfunction "1_1") (pintype "passive"))
      (node (ref "TX_B") (pin "3") (pinfunction "3_3") (pintype "passive"))
    )
    (net (code "242") (name "TILE_TX_P") (class "Default")
      (node (ref "J6") (pin "5") (pinfunction "5_5") (pintype "bidirectional"))
      (node (ref "TILE_5") (pin "TP") (pinfunction "TP_TP") (pintype "input"))
      (node (ref "TX_A") (pin "3") (pinfunction "3_3") (pintype "passive"))
      (node (ref "TX_B") (pin "1") (pinfunction "1_1") (pintype "passive"))
    )
    (net (code "243") (name "TILE_TX_TTL") (class "Default")
      (node (ref "IC3") (pin "5") (pinfunction "RXD_5") (pintype "input"))
      (node (ref "IC9") (pin "2") (pinfunction "RO_2") (pintype "output"))
      (node (ref "T_TX") (pin "P$1") (pinfunction "P1_P$1") (pintype "bidirectional"))
    )
    (net (code "244") (name "TILE_USB_DM") (class "Default")
      (node (ref "IC3") (pin "16") (pinfunction "USBDM_16") (pintype "bidirectional"))
      (node (ref "U8") (pin "8") (pinfunction "USBDN4_DM/PRT_DIS_M4_8") (pintype "bidirectional"))
    )
    (net (code "245") (name "TILE_USB_DP") (class "Default")
      (node (ref "IC3") (pin "15") (pinfunction "USBDP_15") (pintype "bidirectional"))
      (node (ref "U8") (pin "9") (pinfunction "USBDN4_DP/PRT_DIS_P4_9") (pintype "bidirectional"))
    )
    (net (code "246") (name "USB_D_N_IR1") (class "Default")
      (node (ref "D3") (pin "2") (pinfunction "I/O1_2") (pintype "bidirectional"))
      (node (ref "IR1_3") (pin "TP") (pinfunction "TP_TP") (pintype "input"))
      (node (ref "J7") (pin "3") (pinfunction "3_3") (pintype "passive"))
      (node (ref "U8") (pin "1") (pinfunction "USBDN1_DM/PRT_DIS_M1_1") (pintype "bidirectional"))
    )
    (net (code "247") (name "USB_D_N_IR2") (class "Default")
      (node (ref "D2") (pin "2") (pinfunction "I/O1_2") (pintype "bidirectional"))
      (node (ref "IR2_3") (pin "TP") (pinfunction "TP_TP") (pintype "input"))
      (node (ref "J8") (pin "3") (pinfunction "3_3") (pintype "passive"))
      (node (ref "U8") (pin "3") (pinfunction "USBDN2_DM/PRT_DIS_M2_3") (pintype "bidirectional"))
    )
    (net (code "248") (name "USB_D_N_VIS") (class "Default")
      (node (ref "D1") (pin "2") (pinfunction "I/O1_2") (pintype "bidirectional"))
      (node (ref "J2") (pin "3") (pinfunction "3_3") (pintype "passive"))
      (node (ref "U8") (pin "6") (pinfunction "USBDN3_DM/PRT_DIS_M3_6") (pintype "bidirectional"))
      (node (ref "VIS_3") (pin "TP") (pinfunction "TP_TP") (pintype "input"))
    )
    (net (code "249") (name "USB_D_P_IR1") (class "Default")
      (node (ref "D3") (pin "3") (pinfunction "I/O2_3") (pintype "bidirectional"))
      (node (ref "IR1_2") (pin "TP") (pinfunction "TP_TP") (pintype "input"))
      (node (ref "J7") (pin "2") (pinfunction "2_2") (pintype "passive"))
      (node (ref "U8") (pin "2") (pinfunction "USBDN1_DP/PRT_DIS_P1_2") (pintype "bidirectional"))
    )
    (net (code "250") (name "USB_D_P_IR2") (class "Default")
      (node (ref "D2") (pin "3") (pinfunction "I/O2_3") (pintype "bidirectional"))
      (node (ref "IR2_2") (pin "TP") (pinfunction "TP_TP") (pintype "input"))
      (node (ref "J8") (pin "2") (pinfunction "2_2") (pintype "passive"))
      (node (ref "U8") (pin "4") (pinfunction "USBDN2_DP/PRT_DIS_P2_4") (pintype "bidirectional"))
    )
    (net (code "251") (name "USB_D_P_VIS") (class "Default")
      (node (ref "D1") (pin "3") (pinfunction "I/O2_3") (pintype "bidirectional"))
      (node (ref "J2") (pin "2") (pinfunction "2_2") (pintype "passive"))
      (node (ref "U8") (pin "7") (pinfunction "USBDN3_DP/PRT_DIS_P3_7") (pintype "bidirectional"))
      (node (ref "VIS_2") (pin "TP") (pinfunction "TP_TP") (pintype "input"))
    )
    (net (code "252") (name "VBAT") (class "Default")
      (node (ref "U12") (pin "3") (pinfunction "VBAT_3") (pintype "power_in"))
    )
    (net (code "253") (name "VBAT_SW_1") (class "Default")
      (node (ref "H2-CONNECTOR1") (pin "11") (pinfunction "11_11") (pintype "bidirectional"))
    )
    (net (code "254") (name "VBAT_SW_2") (class "Default")
      (node (ref "H2-CONNECTOR1") (pin "12") (pinfunction "12_12") (pintype "bidirectional"))
    )
    (net (code "255") (name "VBUS_DEBUG") (class "Default")
      (node (ref "J4") (pin "1") (pinfunction "VBUS_1") (pintype "passive"))
    )
    (net (code "256") (name "VBUS_FLASH") (class "Default")
      (node (ref "J1") (pin "1") (pinfunction "VBUS_1") (pintype "passive"))
      (node (ref "R18") (pin "2") (pinfunction "2_2") (pintype "passive"))
    )
    (net (code "257") (name "VIS_VCC_5V") (class "Default")
      (node (ref "C3") (pin "1") (pinfunction "1_1") (pintype "passive"))
      (node (ref "J2") (pin "1") (pinfunction "1_1") (pintype "passive"))
      (node (ref "R59") (pin "1") (pinfunction "1_1") (pintype "passive"))
      (node (ref "S1") (pin "1") (pinfunction "OUT_1") (pintype "bidirectional"))
      (node (ref "VIS_1") (pin "TP") (pinfunction "TP_TP") (pintype "input"))
    )
    (net (code "258") (name "V_FLASH") (class "Default")
      (node (ref "R17") (pin "2") (pinfunction "2_2") (pintype "passive"))
      (node (ref "R18") (pin "1") (pinfunction "1_1") (pintype "passive"))
      (node (ref "R38") (pin "1") (pinfunction "1_1") (pintype "passive"))
      (node (ref "R87") (pin "1") (pinfunction "1_1") (pintype "passive"))
      (node (ref "RPI_OTG") (pin "TP") (pinfunction "TP_TP") (pintype "input"))
      (node (ref "U20") (pin "168") (pinfunction "USB_OTGID_168") (pintype "bidirectional"))
      (node (ref "U21") (pin "168") (pinfunction "USB_OTGID_168") (pintype "bidirectional"))
    )
    (net (code "259") (name "WD_A_WDI") (class "Default")
      (node (ref "U20") (pin "58") (pinfunction "GPIO36_58") (pintype "bidirectional"))
      (node (ref "U5") (pin "4") (pinfunction "WDI_4") (pintype "bidirectional"))
      (node (ref "WD_A_WDI") (pin "TP") (pinfunction "TP_TP") (pintype "input"))
    )
    (net (code "260") (name "WD_B_WDI") (class "Default")
      (node (ref "U21") (pin "58") (pinfunction "GPIO36_58") (pintype "bidirectional"))
      (node (ref "U6") (pin "4") (pinfunction "WDI_4") (pintype "bidirectional"))
      (node (ref "WD_B_WDI") (pin "TP") (pinfunction "TP_TP") (pintype "input"))
    )
    (net (code "261") (name "unconnected-(H1-CONNECTOR1-Pad2)") (class "Default")
      (node (ref "H1-CONNECTOR1") (pin "2") (pinfunction "2_2") (pintype "bidirectional"))
    )
    (net (code "262") (name "unconnected-(H1-CONNECTOR1-Pad4)") (class "Default")
      (node (ref "H1-CONNECTOR1") (pin "4") (pinfunction "4_4") (pintype "bidirectional"))
    )
    (net (code "263") (name "unconnected-(H1-CONNECTOR1-Pad6)") (class "Default")
      (node (ref "H1-CONNECTOR1") (pin "6") (pinfunction "6_6") (pintype "bidirectional"))
    )
    (net (code "264") (name "unconnected-(H1-CONNECTOR1-Pad8)") (class "Default")
      (node (ref "H1-CONNECTOR1") (pin "8") (pinfunction "8_8") (pintype "bidirectional"))
    )
    (net (code "265") (name "unconnected-(H1-CONNECTOR1-Pad10)") (class "Default")
      (node (ref "H1-CONNECTOR1") (pin "10") (pinfunction "10_10") (pintype "bidirectional"))
    )
    (net (code "266") (name "unconnected-(H1-CONNECTOR1-Pad11)") (class "Default")
      (node (ref "H1-CONNECTOR1") (pin "11") (pinfunction "11_11") (pintype "bidirectional"))
    )
    (net (code "267") (name "unconnected-(H1-CONNECTOR1-Pad12)") (class "Default")
      (node (ref "H1-CONNECTOR1") (pin "12") (pinfunction "12_12") (pintype "bidirectional"))
    )
    (net (code "268") (name "unconnected-(H1-CONNECTOR1-Pad14)") (class "Default")
      (node (ref "H1-CONNECTOR1") (pin "14") (pinfunction "14_14") (pintype "bidirectional"))
    )
    (net (code "269") (name "unconnected-(H1-CONNECTOR1-Pad18)") (class "Default")
      (node (ref "H1-CONNECTOR1") (pin "18") (pinfunction "18_18") (pintype "bidirectional"))
    )
    (net (code "270") (name "unconnected-(H1-CONNECTOR1-Pad20)") (class "Default")
      (node (ref "H1-CONNECTOR1") (pin "20") (pinfunction "20_20") (pintype "bidirectional"))
    )
    (net (code "271") (name "unconnected-(H1-CONNECTOR1-Pad22)") (class "Default")
      (node (ref "H1-CONNECTOR1") (pin "22") (pinfunction "22_22") (pintype "bidirectional"))
    )
    (net (code "272") (name "unconnected-(H1-CONNECTOR1-Pad24)") (class "Default")
      (node (ref "H1-CONNECTOR1") (pin "24") (pinfunction "24_24") (pintype "bidirectional"))
    )
    (net (code "273") (name "unconnected-(H1-CONNECTOR1-Pad25)") (class "Default")
      (node (ref "H1-CONNECTOR1") (pin "25") (pinfunction "25_25") (pintype "bidirectional"))
    )
    (net (code "274") (name "unconnected-(H1-CONNECTOR1-Pad26)") (class "Default")
      (node (ref "H1-CONNECTOR1") (pin "26") (pinfunction "26_26") (pintype "bidirectional"))
    )
    (net (code "275") (name "unconnected-(H1-CONNECTOR1-Pad27)") (class "Default")
      (node (ref "H1-CONNECTOR1") (pin "27") (pinfunction "27_27") (pintype "bidirectional"))
    )
    (net (code "276") (name "unconnected-(H1-CONNECTOR1-Pad28)") (class "Default")
      (node (ref "H1-CONNECTOR1") (pin "28") (pinfunction "28_28") (pintype "bidirectional"))
    )
    (net (code "277") (name "unconnected-(H1-CONNECTOR1-Pad29)") (class "Default")
      (node (ref "H1-CONNECTOR1") (pin "29") (pinfunction "29_29") (pintype "bidirectional"))
    )
    (net (code "278") (name "unconnected-(H1-CONNECTOR1-Pad30)") (class "Default")
      (node (ref "H1-CONNECTOR1") (pin "30") (pinfunction "30_30") (pintype "bidirectional"))
    )
    (net (code "279") (name "unconnected-(H1-CONNECTOR1-Pad31)") (class "Default")
      (node (ref "H1-CONNECTOR1") (pin "31") (pinfunction "31_31") (pintype "bidirectional"))
    )
    (net (code "280") (name "unconnected-(H1-CONNECTOR1-Pad33)") (class "Default")
      (node (ref "H1-CONNECTOR1") (pin "33") (pinfunction "33_33") (pintype "bidirectional"))
    )
    (net (code "281") (name "unconnected-(H1-CONNECTOR1-Pad34)") (class "Default")
      (node (ref "H1-CONNECTOR1") (pin "34") (pinfunction "34_34") (pintype "bidirectional"))
    )
    (net (code "282") (name "unconnected-(H1-CONNECTOR1-Pad35)") (class "Default")
      (node (ref "H1-CONNECTOR1") (pin "35") (pinfunction "35_35") (pintype "bidirectional"))
    )
    (net (code "283") (name "unconnected-(H1-CONNECTOR1-Pad36)") (class "Default")
      (node (ref "H1-CONNECTOR1") (pin "36") (pinfunction "36_36") (pintype "bidirectional"))
    )
    (net (code "284") (name "unconnected-(H1-CONNECTOR1-Pad37)") (class "Default")
      (node (ref "H1-CONNECTOR1") (pin "37") (pinfunction "37_37") (pintype "bidirectional"))
    )
    (net (code "285") (name "unconnected-(H1-CONNECTOR1-Pad38)") (class "Default")
      (node (ref "H1-CONNECTOR1") (pin "38") (pinfunction "38_38") (pintype "bidirectional"))
    )
    (net (code "286") (name "unconnected-(H1-CONNECTOR1-Pad39)") (class "Default")
      (node (ref "H1-CONNECTOR1") (pin "39") (pinfunction "39_39") (pintype "bidirectional"))
    )
    (net (code "287") (name "unconnected-(H1-CONNECTOR1-Pad40)") (class "Default")
      (node (ref "H1-CONNECTOR1") (pin "40") (pinfunction "40_40") (pintype "bidirectional"))
    )
    (net (code "288") (name "unconnected-(H1-CONNECTOR1-Pad42)") (class "Default")
      (node (ref "H1-CONNECTOR1") (pin "42") (pinfunction "42_42") (pintype "bidirectional"))
    )
    (net (code "289") (name "unconnected-(H1-CONNECTOR1-Pad44)") (class "Default")
      (node (ref "H1-CONNECTOR1") (pin "44") (pinfunction "44_44") (pintype "bidirectional"))
    )
    (net (code "290") (name "unconnected-(H1-CONNECTOR1-Pad45)") (class "Default")
      (node (ref "H1-CONNECTOR1") (pin "45") (pinfunction "45_45") (pintype "bidirectional"))
    )
    (net (code "291") (name "unconnected-(H1-CONNECTOR1-Pad46)") (class "Default")
      (node (ref "H1-CONNECTOR1") (pin "46") (pinfunction "46_46") (pintype "bidirectional"))
    )
    (net (code "292") (name "unconnected-(H1-CONNECTOR1-Pad47)") (class "Default")
      (node (ref "H1-CONNECTOR1") (pin "47") (pinfunction "47_47") (pintype "bidirectional"))
    )
    (net (code "293") (name "unconnected-(H1-CONNECTOR1-Pad48)") (class "Default")
      (node (ref "H1-CONNECTOR1") (pin "48") (pinfunction "48_48") (pintype "bidirectional"))
    )
    (net (code "294") (name "unconnected-(H1-CONNECTOR1-Pad49)") (class "Default")
      (node (ref "H1-CONNECTOR1") (pin "49") (pinfunction "49_49") (pintype "bidirectional"))
    )
    (net (code "295") (name "unconnected-(H1-CONNECTOR1-Pad50)") (class "Default")
      (node (ref "H1-CONNECTOR1") (pin "50") (pinfunction "50_50") (pintype "bidirectional"))
    )
    (net (code "296") (name "unconnected-(H1-CONNECTOR1-Pad51)") (class "Default")
      (node (ref "H1-CONNECTOR1") (pin "51") (pinfunction "51_51") (pintype "bidirectional"))
    )
    (net (code "297") (name "unconnected-(H1-CONNECTOR1-Pad52)") (class "Default")
      (node (ref "H1-CONNECTOR1") (pin "52") (pinfunction "52_52") (pintype "bidirectional"))
    )
    (net (code "298") (name "unconnected-(H2-CONNECTOR1-Pad1)") (class "Default")
      (node (ref "H2-CONNECTOR1") (pin "1") (pinfunction "1_1") (pintype "bidirectional"))
    )
    (net (code "299") (name "unconnected-(H2-CONNECTOR1-Pad2)") (class "Default")
      (node (ref "H2-CONNECTOR1") (pin "2") (pinfunction "2_2") (pintype "bidirectional"))
    )
    (net (code "300") (name "unconnected-(H2-CONNECTOR1-Pad3)") (class "Default")
      (node (ref "H2-CONNECTOR1") (pin "3") (pinfunction "3_3") (pintype "bidirectional"))
    )
    (net (code "301") (name "unconnected-(H2-CONNECTOR1-Pad4)") (class "Default")
      (node (ref "H2-CONNECTOR1") (pin "4") (pinfunction "4_4") (pintype "bidirectional"))
    )
    (net (code "302") (name "unconnected-(H2-CONNECTOR1-Pad5)") (class "Default")
      (node (ref "H2-CONNECTOR1") (pin "5") (pinfunction "5_5") (pintype "bidirectional"))
    )
    (net (code "303") (name "unconnected-(H2-CONNECTOR1-Pad6)") (class "Default")
      (node (ref "H2-CONNECTOR1") (pin "6") (pinfunction "6_6") (pintype "bidirectional"))
    )
    (net (code "304") (name "unconnected-(H2-CONNECTOR1-Pad7)") (class "Default")
      (node (ref "H2-CONNECTOR1") (pin "7") (pinfunction "7_7") (pintype "bidirectional"))
    )
    (net (code "305") (name "unconnected-(H2-CONNECTOR1-Pad31)") (class "Default")
      (node (ref "H2-CONNECTOR1") (pin "31") (pinfunction "31_31") (pintype "bidirectional"))
    )
    (net (code "306") (name "unconnected-(H2-CONNECTOR1-Pad33)") (class "Default")
      (node (ref "H2-CONNECTOR1") (pin "33") (pinfunction "33_33") (pintype "bidirectional"))
    )
    (net (code "307") (name "unconnected-(H2-CONNECTOR1-Pad34)") (class "Default")
      (node (ref "H2-CONNECTOR1") (pin "34") (pinfunction "34_34") (pintype "bidirectional"))
    )
    (net (code "308") (name "unconnected-(H2-CONNECTOR1-Pad35)") (class "Default")
      (node (ref "H2-CONNECTOR1") (pin "35") (pinfunction "35_35") (pintype "bidirectional"))
    )
    (net (code "309") (name "unconnected-(H2-CONNECTOR1-Pad36)") (class "Default")
      (node (ref "H2-CONNECTOR1") (pin "36") (pinfunction "36_36") (pintype "bidirectional"))
    )
    (net (code "310") (name "unconnected-(H2-CONNECTOR1-Pad37)") (class "Default")
      (node (ref "H2-CONNECTOR1") (pin "37") (pinfunction "37_37") (pintype "bidirectional"))
    )
    (net (code "311") (name "unconnected-(H2-CONNECTOR1-Pad38)") (class "Default")
      (node (ref "H2-CONNECTOR1") (pin "38") (pinfunction "38_38") (pintype "bidirectional"))
    )
    (net (code "312") (name "unconnected-(H2-CONNECTOR1-Pad39)") (class "Default")
      (node (ref "H2-CONNECTOR1") (pin "39") (pinfunction "39_39") (pintype "bidirectional"))
    )
    (net (code "313") (name "unconnected-(H2-CONNECTOR1-Pad40)") (class "Default")
      (node (ref "H2-CONNECTOR1") (pin "40") (pinfunction "40_40") (pintype "bidirectional"))
    )
    (net (code "314") (name "unconnected-(H2-CONNECTOR1-Pad41)") (class "Default")
      (node (ref "H2-CONNECTOR1") (pin "41") (pinfunction "41_41") (pintype "bidirectional"))
    )
    (net (code "315") (name "unconnected-(H2-CONNECTOR1-Pad43)") (class "Default")
      (node (ref "H2-CONNECTOR1") (pin "43") (pinfunction "43_43") (pintype "bidirectional"))
    )
    (net (code "316") (name "unconnected-(H2-CONNECTOR1-Pad45)") (class "Default")
      (node (ref "H2-CONNECTOR1") (pin "45") (pinfunction "45_45") (pintype "bidirectional"))
    )
    (net (code "317") (name "unconnected-(H2-CONNECTOR1-Pad47)") (class "Default")
      (node (ref "H2-CONNECTOR1") (pin "47") (pinfunction "47_47") (pintype "bidirectional"))
    )
    (net (code "318") (name "unconnected-(H2-CONNECTOR1-Pad49)") (class "Default")
      (node (ref "H2-CONNECTOR1") (pin "49") (pinfunction "49_49") (pintype "bidirectional"))
    )
    (net (code "319") (name "unconnected-(H2-CONNECTOR1-Pad51)") (class "Default")
      (node (ref "H2-CONNECTOR1") (pin "51") (pinfunction "51_51") (pintype "bidirectional"))
    )
    (net (code "320") (name "unconnected-(IC3-CBUS2-Pad13)") (class "Default")
      (node (ref "IC3") (pin "13") (pinfunction "CBUS2_13") (pintype "bidirectional"))
    )
    (net (code "321") (name "unconnected-(IC3-CBUS3-Pad14)") (class "Default")
      (node (ref "IC3") (pin "14") (pinfunction "CBUS3_14") (pintype "bidirectional"))
    )
    (net (code "322") (name "unconnected-(IC3-CBUS4-Pad12)") (class "Default")
      (node (ref "IC3") (pin "12") (pinfunction "CBUS4_12") (pintype "bidirectional"))
    )
    (net (code "323") (name "unconnected-(IC3-OSCI-Pad27)") (class "Default")
      (node (ref "IC3") (pin "27") (pinfunction "OSCI_27") (pintype "input"))
    )
    (net (code "324") (name "unconnected-(IC3-OSCO-Pad28)") (class "Default")
      (node (ref "IC3") (pin "28") (pinfunction "OSCO_28") (pintype "output"))
    )
    (net (code "325") (name "unconnected-(IC3-~{CTS}-Pad11)") (class "Default")
      (node (ref "IC3") (pin "11") (pinfunction "~{CTS}_11") (pintype "input"))
    )
    (net (code "326") (name "unconnected-(IC3-~{DCD}-Pad10)") (class "Default")
      (node (ref "IC3") (pin "10") (pinfunction "~{DCD}_10") (pintype "input"))
    )
    (net (code "327") (name "unconnected-(IC3-~{DSR}-Pad9)") (class "Default")
      (node (ref "IC3") (pin "9") (pinfunction "~{DSR}_9") (pintype "input"))
    )
    (net (code "328") (name "unconnected-(IC3-~{DTR}-Pad2)") (class "Default")
      (node (ref "IC3") (pin "2") (pinfunction "~{DTR}_2") (pintype "output"))
    )
    (net (code "329") (name "unconnected-(IC3-~{RI}-Pad6)") (class "Default")
      (node (ref "IC3") (pin "6") (pinfunction "~{RI}_6") (pintype "input"))
    )
    (net (code "330") (name "unconnected-(IC3-~{RTS}-Pad3)") (class "Default")
      (node (ref "IC3") (pin "3") (pinfunction "~{RTS}_3") (pintype "output"))
    )
    (net (code "331") (name "unconnected-(IC7A-~{Q}-Pad6)") (class "Default")
      (node (ref "IC7") (pin "6") (pinfunction "~{Q}_6") (pintype "output"))
    )
    (net (code "332") (name "unconnected-(IC7B-~{Q}-Pad7)") (class "Default")
      (node (ref "IC7") (pin "7") (pinfunction "~{Q}_7") (pintype "output"))
    )
    (net (code "333") (name "unconnected-(IC10-CBUS2-Pad13)") (class "Default")
      (node (ref "IC10") (pin "13") (pinfunction "CBUS2_13") (pintype "bidirectional"))
    )
    (net (code "334") (name "unconnected-(IC10-CBUS3-Pad14)") (class "Default")
      (node (ref "IC10") (pin "14") (pinfunction "CBUS3_14") (pintype "bidirectional"))
    )
    (net (code "335") (name "unconnected-(IC10-CBUS4-Pad12)") (class "Default")
      (node (ref "IC10") (pin "12") (pinfunction "CBUS4_12") (pintype "bidirectional"))
    )
    (net (code "336") (name "unconnected-(IC10-OSCI-Pad27)") (class "Default")
      (node (ref "IC10") (pin "27") (pinfunction "OSCI_27") (pintype "input"))
    )
    (net (code "337") (name "unconnected-(IC10-OSCO-Pad28)") (class "Default")
      (node (ref "IC10") (pin "28") (pinfunction "OSCO_28") (pintype "output"))
    )
    (net (code "338") (name "unconnected-(IC10-~{CTS}-Pad11)") (class "Default")
      (node (ref "IC10") (pin "11") (pinfunction "~{CTS}_11") (pintype "input"))
    )
    (net (code "339") (name "unconnected-(IC10-~{DCD}-Pad10)") (class "Default")
      (node (ref "IC10") (pin "10") (pinfunction "~{DCD}_10") (pintype "input"))
    )
    (net (code "340") (name "unconnected-(IC10-~{DSR}-Pad9)") (class "Default")
      (node (ref "IC10") (pin "9") (pinfunction "~{DSR}_9") (pintype "input"))
    )
    (net (code "341") (name "unconnected-(IC10-~{DTR}-Pad2)") (class "Default")
      (node (ref "IC10") (pin "2") (pinfunction "~{DTR}_2") (pintype "output"))
    )
    (net (code "342") (name "unconnected-(IC10-~{RI}-Pad6)") (class "Default")
      (node (ref "IC10") (pin "6") (pinfunction "~{RI}_6") (pintype "input"))
    )
    (net (code "343") (name "unconnected-(IC10-~{RTS}-Pad3)") (class "Default")
      (node (ref "IC10") (pin "3") (pinfunction "~{RTS}_3") (pintype "output"))
    )
    (net (code "344") (name "unconnected-(U1-AUX_CL-Pad7)") (class "Default")
      (node (ref "U1") (pin "7") (pinfunction "AUX_CL_7") (pintype "input"))
    )
    (net (code "345") (name "unconnected-(U1-AUX_DA-Pad21)") (class "Default")
      (node (ref "U1") (pin "21") (pinfunction "AUX_DA_21") (pintype "input"))
    )
    (net (code "346") (name "unconnected-(U1-INT1-Pad12)") (class "Default")
      (node (ref "U1") (pin "12") (pinfunction "INT1_12") (pintype "output"))
    )
    (net (code "347") (name "unconnected-(U1-RESV_19-Pad19)") (class "Default")
      (node (ref "U1") (pin "19") (pinfunction "RESV_19_19") (pintype "passive"))
    )
    (net (code "348") (name "unconnected-(U2-NC-Pad1)") (class "Default")
      (node (ref "U2") (pin "1") (pinfunction "NC_1") (pintype "bidirectional"))
    )
    (net (code "349") (name "unconnected-(U3-AUX_CL-Pad7)") (class "Default")
      (node (ref "U3") (pin "7") (pinfunction "AUX_CL_7") (pintype "input"))
    )
    (net (code "350") (name "unconnected-(U3-AUX_DA-Pad21)") (class "Default")
      (node (ref "U3") (pin "21") (pinfunction "AUX_DA_21") (pintype "input"))
    )
    (net (code "351") (name "unconnected-(U3-INT1-Pad12)") (class "Default")
      (node (ref "U3") (pin "12") (pinfunction "INT1_12") (pintype "output"))
    )
    (net (code "352") (name "unconnected-(U3-RESV_19-Pad19)") (class "Default")
      (node (ref "U3") (pin "19") (pinfunction "RESV_19_19") (pintype "passive"))
    )
    (net (code "353") (name "unconnected-(U7-PG-Pad9)") (class "Default")
      (node (ref "U7") (pin "9") (pinfunction "PG_9") (pintype "open_collector"))
    )
    (net (code "354") (name "unconnected-(U8-LED_A7_N{slash}PRT_SWP7-Pad15)") (class "Default")
      (node (ref "U8") (pin "15") (pinfunction "LED_A7_N/PRT_SWP7_15") (pintype "bidirectional"))
    )
    (net (code "355") (name "unconnected-(U8-LED_B1_N{slash}BOOST0-Pad50)") (class "Default")
      (node (ref "U8") (pin "50") (pinfunction "LED_B1_N/BOOST0_50") (pintype "bidirectional"))
    )
    (net (code "356") (name "unconnected-(U8-LED_B2_N{slash}BOOST1-Pad48)") (class "Default")
      (node (ref "U8") (pin "48") (pinfunction "LED_B2_N/BOOST1_48") (pintype "bidirectional"))
    )
    (net (code "357") (name "unconnected-(U8-LED_B3_N{slash}GANG_EN-Pad34)") (class "Default")
      (node (ref "U8") (pin "34") (pinfunction "LED_B3_N/GANG_EN_34") (pintype "bidirectional"))
    )
    (net (code "358") (name "unconnected-(U8-LED_B4_N-Pad32)") (class "Default")
      (node (ref "U8") (pin "32") (pinfunction "LED_B4_N_32") (pintype "bidirectional"))
    )
    (net (code "359") (name "unconnected-(U8-LED_B5_N-Pad18)") (class "Default")
      (node (ref "U8") (pin "18") (pinfunction "LED_B5_N_18") (pintype "bidirectional"))
    )
    (net (code "360") (name "unconnected-(U8-LED_B6_N-Pad16)") (class "Default")
      (node (ref "U8") (pin "16") (pinfunction "LED_B6_N_16") (pintype "bidirectional"))
    )
    (net (code "361") (name "unconnected-(U8-LED_B7_N-Pad14)") (class "Default")
      (node (ref "U8") (pin "14") (pinfunction "LED_B7_N_14") (pintype "bidirectional"))
    )
    (net (code "362") (name "unconnected-(U8-OCS1_N-Pad28)") (class "Default")
      (node (ref "U8") (pin "28") (pinfunction "OCS1_N_28") (pintype "input"))
    )
    (net (code "363") (name "unconnected-(U8-OCS2_N-Pad27)") (class "Default")
      (node (ref "U8") (pin "27") (pinfunction "OCS2_N_27") (pintype "input"))
    )
    (net (code "364") (name "unconnected-(U8-OCS3_N-Pad22)") (class "Default")
      (node (ref "U8") (pin "22") (pinfunction "OCS3_N_22") (pintype "input"))
    )
    (net (code "365") (name "unconnected-(U8-OCS4_N-Pad21)") (class "Default")
      (node (ref "U8") (pin "21") (pinfunction "OCS4_N_21") (pintype "input"))
    )
    (net (code "366") (name "unconnected-(U8-OCS5_N-Pad35)") (class "Default")
      (node (ref "U8") (pin "35") (pinfunction "OCS5_N_35") (pintype "input"))
    )
    (net (code "367") (name "unconnected-(U8-OCS6_N-Pad38)") (class "Default")
      (node (ref "U8") (pin "38") (pinfunction "OCS6_N_38") (pintype "input"))
    )
    (net (code "368") (name "unconnected-(U8-OCS7_N-Pad37)") (class "Default")
      (node (ref "U8") (pin "37") (pinfunction "OCS7_N_37") (pintype "input"))
    )
    (net (code "369") (name "unconnected-(U8-PRTPWR1-Pad29)") (class "Default")
      (node (ref "U8") (pin "29") (pinfunction "PRTPWR1_29") (pintype "output"))
    )
    (net (code "370") (name "unconnected-(U8-PRTPWR2-Pad26)") (class "Default")
      (node (ref "U8") (pin "26") (pinfunction "PRTPWR2_26") (pintype "output"))
    )
    (net (code "371") (name "unconnected-(U8-PRTPWR3-Pad23)") (class "Default")
      (node (ref "U8") (pin "23") (pinfunction "PRTPWR3_23") (pintype "output"))
    )
    (net (code "372") (name "unconnected-(U8-PRTPWR4-Pad20)") (class "Default")
      (node (ref "U8") (pin "20") (pinfunction "PRTPWR4_20") (pintype "output"))
    )
    (net (code "373") (name "unconnected-(U8-PRTPWR5-Pad30)") (class "Default")
      (node (ref "U8") (pin "30") (pinfunction "PRTPWR5_30") (pintype "output"))
    )
    (net (code "374") (name "unconnected-(U8-PRTPWR6-Pad39)") (class "Default")
      (node (ref "U8") (pin "39") (pinfunction "PRTPWR6_39") (pintype "output"))
    )
    (net (code "375") (name "unconnected-(U8-PRTPWR7-Pad36)") (class "Default")
      (node (ref "U8") (pin "36") (pinfunction "PRTPWR7_36") (pintype "output"))
    )
    (net (code "376") (name "unconnected-(U8-TEST-Pad19)") (class "Default")
      (node (ref "U8") (pin "19") (pinfunction "TEST_19") (pintype "input"))
    )
    (net (code "377") (name "unconnected-(U9-NC-Pad1)") (class "Default")
      (node (ref "U9") (pin "1") (pinfunction "NC_1") (pintype "bidirectional"))
    )
    (net (code "378") (name "unconnected-(U10-NC-Pad1)") (class "Default")
      (node (ref "U10") (pin "1") (pinfunction "NC_1") (pintype "bidirectional"))
    )
    (net (code "379") (name "unconnected-(U12-MFP-Pad7)") (class "Default")
      (node (ref "U12") (pin "7") (pinfunction "MFP_7") (pintype "passive"))
    )
    (net (code "380") (name "unconnected-(U15-PG-Pad9)") (class "Default")
      (node (ref "U15") (pin "9") (pinfunction "PG_9") (pintype "open_collector"))
    )
    (net (code "381") (name "unconnected-(U16-PG-Pad9)") (class "Default")
      (node (ref "U16") (pin "9") (pinfunction "PG_9") (pintype "open_collector"))
    )
    (net (code "382") (name "unconnected-(U17-PG-Pad9)") (class "Default")
      (node (ref "U17") (pin "9") (pinfunction "PG_9") (pintype "open_collector"))
    )
    (net (code "383") (name "unconnected-(U19-NC-Pad1)") (class "Default")
      (node (ref "U19") (pin "1") (pinfunction "NC_1") (pintype "bidirectional"))
    )
    (net (code "384") (name "unconnected-(U20-CAM0_CN-Pad144)") (class "Default")
      (node (ref "U20") (pin "144") (pinfunction "CAM0_CN_144") (pintype "bidirectional"))
    )
    (net (code "385") (name "unconnected-(U20-CAM0_CP-Pad142)") (class "Default")
      (node (ref "U20") (pin "142") (pinfunction "CAM0_CP_142") (pintype "bidirectional"))
    )
    (net (code "386") (name "unconnected-(U20-CAM0_DN0-Pad138)") (class "Default")
      (node (ref "U20") (pin "138") (pinfunction "CAM0_DN0_138") (pintype "bidirectional"))
    )
    (net (code "387") (name "unconnected-(U20-CAM0_DN1-Pad150)") (class "Default")
      (node (ref "U20") (pin "150") (pinfunction "CAM0_DN1_150") (pintype "bidirectional"))
    )
    (net (code "388") (name "unconnected-(U20-CAM0_DP0-Pad136)") (class "Default")
      (node (ref "U20") (pin "136") (pinfunction "CAM0_DP0_136") (pintype "bidirectional"))
    )
    (net (code "389") (name "unconnected-(U20-CAM0_DP1-Pad148)") (class "Default")
      (node (ref "U20") (pin "148") (pinfunction "CAM0_DP1_148") (pintype "bidirectional"))
    )
    (net (code "390") (name "unconnected-(U20-CAM1_CN-Pad149)") (class "Default")
      (node (ref "U20") (pin "149") (pinfunction "CAM1_CN_149") (pintype "bidirectional"))
    )
    (net (code "391") (name "unconnected-(U20-CAM1_CP-Pad147)") (class "Default")
      (node (ref "U20") (pin "147") (pinfunction "CAM1_CP_147") (pintype "bidirectional"))
    )
    (net (code "392") (name "unconnected-(U20-CAM1_DN0-Pad161)") (class "Default")
      (node (ref "U20") (pin "161") (pinfunction "CAM1_DN0_161") (pintype "bidirectional"))
    )
    (net (code "393") (name "unconnected-(U20-CAM1_DN1-Pad155)") (class "Default")
      (node (ref "U20") (pin "155") (pinfunction "CAM1_DN1_155") (pintype "bidirectional"))
    )
    (net (code "394") (name "unconnected-(U20-CAM1_DN2-Pad143)") (class "Default")
      (node (ref "U20") (pin "143") (pinfunction "CAM1_DN2_143") (pintype "bidirectional"))
    )
    (net (code "395") (name "unconnected-(U20-CAM1_DN3-Pad137)") (class "Default")
      (node (ref "U20") (pin "137") (pinfunction "CAM1_DN3_137") (pintype "bidirectional"))
    )
    (net (code "396") (name "unconnected-(U20-CAM1_DP0-Pad159)") (class "Default")
      (node (ref "U20") (pin "159") (pinfunction "CAM1_DP0_159") (pintype "bidirectional"))
    )
    (net (code "397") (name "unconnected-(U20-CAM1_DP1-Pad153)") (class "Default")
      (node (ref "U20") (pin "153") (pinfunction "CAM1_DP1_153") (pintype "bidirectional"))
    )
    (net (code "398") (name "unconnected-(U20-CAM1_DP2-Pad141)") (class "Default")
      (node (ref "U20") (pin "141") (pinfunction "CAM1_DP2_141") (pintype "bidirectional"))
    )
    (net (code "399") (name "unconnected-(U20-CAM1_DP3-Pad135)") (class "Default")
      (node (ref "U20") (pin "135") (pinfunction "CAM1_DP3_135") (pintype "bidirectional"))
    )
    (net (code "400") (name "unconnected-(U20-DSI0_CN-Pad105)") (class "Default")
      (node (ref "U20") (pin "105") (pinfunction "DSI0_CN_105") (pintype "bidirectional"))
    )
    (net (code "401") (name "unconnected-(U20-DSI0_CP-Pad107)") (class "Default")
      (node (ref "U20") (pin "107") (pinfunction "DSI0_CP_107") (pintype "bidirectional"))
    )
    (net (code "402") (name "unconnected-(U20-DSI0_DN0-Pad99)") (class "Default")
      (node (ref "U20") (pin "99") (pinfunction "DSI0_DN0_99") (pintype "bidirectional"))
    )
    (net (code "403") (name "unconnected-(U20-DSI0_DN1-Pad93)") (class "Default")
      (node (ref "U20") (pin "93") (pinfunction "DSI0_DN1_93") (pintype "bidirectional"))
    )
    (net (code "404") (name "unconnected-(U20-DSI0_DP0-Pad101)") (class "Default")
      (node (ref "U20") (pin "101") (pinfunction "DSI0_DP0_101") (pintype "bidirectional"))
    )
    (net (code "405") (name "unconnected-(U20-DSI0_DP1-Pad95)") (class "Default")
      (node (ref "U20") (pin "95") (pinfunction "DSI0_DP1_95") (pintype "bidirectional"))
    )
    (net (code "406") (name "unconnected-(U20-DSI1_CN-Pad102)") (class "Default")
      (node (ref "U20") (pin "102") (pinfunction "DSI1_CN_102") (pintype "bidirectional"))
    )
    (net (code "407") (name "unconnected-(U20-DSI1_CP-Pad100)") (class "Default")
      (node (ref "U20") (pin "100") (pinfunction "DSI1_CP_100") (pintype "bidirectional"))
    )
    (net (code "408") (name "unconnected-(U20-DSI1_DN0-Pad96)") (class "Default")
      (node (ref "U20") (pin "96") (pinfunction "DSI1_DN0_96") (pintype "bidirectional"))
    )
    (net (code "409") (name "unconnected-(U20-DSI1_DN1-Pad120)") (class "Default")
      (node (ref "U20") (pin "120") (pinfunction "DSI1_DN1_120") (pintype "bidirectional"))
    )
    (net (code "410") (name "unconnected-(U20-DSI1_DN2-Pad114)") (class "Default")
      (node (ref "U20") (pin "114") (pinfunction "DSI1_DN2_114") (pintype "bidirectional"))
    )
    (net (code "411") (name "unconnected-(U20-DSI1_DN3-Pad108)") (class "Default")
      (node (ref "U20") (pin "108") (pinfunction "DSI1_DN3_108") (pintype "bidirectional"))
    )
    (net (code "412") (name "unconnected-(U20-DSI1_DP0-Pad94)") (class "Default")
      (node (ref "U20") (pin "94") (pinfunction "DSI1_DP0_94") (pintype "bidirectional"))
    )
    (net (code "413") (name "unconnected-(U20-DSI1_DP1-Pad118)") (class "Default")
      (node (ref "U20") (pin "118") (pinfunction "DSI1_DP1_118") (pintype "bidirectional"))
    )
    (net (code "414") (name "unconnected-(U20-DSI1_DP2-Pad112)") (class "Default")
      (node (ref "U20") (pin "112") (pinfunction "DSI1_DP2_112") (pintype "bidirectional"))
    )
    (net (code "415") (name "unconnected-(U20-DSI1_DP3-Pad106)") (class "Default")
      (node (ref "U20") (pin "106") (pinfunction "DSI1_DP3_106") (pintype "bidirectional"))
    )
    (net (code "416") (name "unconnected-(U20-GPIO4-Pad15)") (class "Default")
      (node (ref "U20") (pin "15") (pinfunction "GPIO4_15") (pintype "bidirectional"))
    )
    (net (code "417") (name "unconnected-(U20-GPIO5-Pad17)") (class "Default")
      (node (ref "U20") (pin "17") (pinfunction "GPIO5_17") (pintype "bidirectional"))
    )
    (net (code "418") (name "unconnected-(U20-GPIO6-Pad21)") (class "Default")
      (node (ref "U20") (pin "21") (pinfunction "GPIO6_21") (pintype "bidirectional"))
    )
    (net (code "419") (name "unconnected-(U20-GPIO7-Pad23)") (class "Default")
      (node (ref "U20") (pin "23") (pinfunction "GPIO7_23") (pintype "bidirectional"))
    )
    (net (code "420") (name "unconnected-(U20-GPIO12-Pad45)") (class "Default")
      (node (ref "U20") (pin "45") (pinfunction "GPIO12_45") (pintype "bidirectional"))
    )
    (net (code "421") (name "unconnected-(U20-GPIO13-Pad47)") (class "Default")
      (node (ref "U20") (pin "47") (pinfunction "GPIO13_47") (pintype "bidirectional"))
    )
    (net (code "422") (name "unconnected-(U20-GPIO30-Pad34)") (class "Default")
      (node (ref "U20") (pin "34") (pinfunction "GPIO30_34") (pintype "bidirectional"))
    )
    (net (code "423") (name "unconnected-(U20-GPIO31-Pad36)") (class "Default")
      (node (ref "U20") (pin "36") (pinfunction "GPIO31_36") (pintype "bidirectional"))
    )
    (net (code "424") (name "unconnected-(U20-GPIO46_1V8-Pad88)") (class "Default")
      (node (ref "U20") (pin "88") (pinfunction "GPIO46_1V8_88") (pintype "bidirectional"))
    )
    (net (code "425") (name "unconnected-(U20-GPIO47_1V8-Pad90)") (class "Default")
      (node (ref "U20") (pin "90") (pinfunction "GPIO47_1V8_90") (pintype "bidirectional"))
    )
    (net (code "426") (name "unconnected-(U20-HDMI_CEC-Pad171)") (class "Default")
      (node (ref "U20") (pin "171") (pinfunction "HDMI_CEC_171") (pintype "bidirectional"))
    )
    (net (code "427") (name "unconnected-(U20-HDMI_CK_N-Pad111)") (class "Default")
      (node (ref "U20") (pin "111") (pinfunction "HDMI_CK_N_111") (pintype "bidirectional"))
    )
    (net (code "428") (name "unconnected-(U20-HDMI_CK_P-Pad113)") (class "Default")
      (node (ref "U20") (pin "113") (pinfunction "HDMI_CK_P_113") (pintype "bidirectional"))
    )
    (net (code "429") (name "unconnected-(U20-HDMI_D0_N-Pad117)") (class "Default")
      (node (ref "U20") (pin "117") (pinfunction "HDMI_D0_N_117") (pintype "bidirectional"))
    )
    (net (code "430") (name "unconnected-(U20-HDMI_D0_P-Pad119)") (class "Default")
      (node (ref "U20") (pin "119") (pinfunction "HDMI_D0_P_119") (pintype "bidirectional"))
    )
    (net (code "431") (name "unconnected-(U20-HDMI_D1_N-Pad123)") (class "Default")
      (node (ref "U20") (pin "123") (pinfunction "HDMI_D1_N_123") (pintype "bidirectional"))
    )
    (net (code "432") (name "unconnected-(U20-HDMI_D1_P-Pad125)") (class "Default")
      (node (ref "U20") (pin "125") (pinfunction "HDMI_D1_P_125") (pintype "bidirectional"))
    )
    (net (code "433") (name "unconnected-(U20-HDMI_D2_N-Pad129)") (class "Default")
      (node (ref "U20") (pin "129") (pinfunction "HDMI_D2_N_129") (pintype "bidirectional"))
    )
    (net (code "434") (name "unconnected-(U20-HDMI_D2_P-Pad131)") (class "Default")
      (node (ref "U20") (pin "131") (pinfunction "HDMI_D2_P_131") (pintype "bidirectional"))
    )
    (net (code "435") (name "unconnected-(U20-HDMI_SCL-Pad175)") (class "Default")
      (node (ref "U20") (pin "175") (pinfunction "HDMI_SCL_175") (pintype "bidirectional"))
    )
    (net (code "436") (name "unconnected-(U20-HDMI_SDA-Pad173)") (class "Default")
      (node (ref "U20") (pin "173") (pinfunction "HDMI_SDA_173") (pintype "bidirectional"))
    )
    (net (code "437") (name "unconnected-(U20-NC-Pad124)") (class "Default")
      (node (ref "U20") (pin "124") (pinfunction "NC_124") (pintype "bidirectional"))
    )
    (net (code "438") (name "unconnected-(U20-NC-Pad126)") (class "Default")
      (node (ref "U20") (pin "126") (pinfunction "NC_126") (pintype "bidirectional"))
    )
    (net (code "439") (name "unconnected-(U20-NC-Pad128)") (class "Default")
      (node (ref "U20") (pin "128") (pinfunction "NC_128") (pintype "bidirectional"))
    )
    (net (code "440") (name "unconnected-(U20-NC-Pad130)") (class "Default")
      (node (ref "U20") (pin "130") (pinfunction "NC_130") (pintype "bidirectional"))
    )
    (net (code "441") (name "unconnected-(U20-NC-Pad132)") (class "Default")
      (node (ref "U20") (pin "132") (pinfunction "NC_132") (pintype "bidirectional"))
    )
    (net (code "442") (name "unconnected-(U20-NC-Pad154)") (class "Default")
      (node (ref "U20") (pin "154") (pinfunction "NC_154") (pintype "bidirectional"))
    )
    (net (code "443") (name "unconnected-(U20-NC-Pad156)") (class "Default")
      (node (ref "U20") (pin "156") (pinfunction "NC_156") (pintype "bidirectional"))
    )
    (net (code "444") (name "unconnected-(U20-NC-Pad158)") (class "Default")
      (node (ref "U20") (pin "158") (pinfunction "NC_158") (pintype "bidirectional"))
    )
    (net (code "445") (name "unconnected-(U20-NC-Pad160)") (class "Default")
      (node (ref "U20") (pin "160") (pinfunction "NC_160") (pintype "bidirectional"))
    )
    (net (code "446") (name "unconnected-(U20-NC-Pad162)") (class "Default")
      (node (ref "U20") (pin "162") (pinfunction "NC_162") (pintype "bidirectional"))
    )
    (net (code "447") (name "unconnected-(U20-PadG1)") (class "Default")
      (node (ref "U20") (pin "G1") (pinfunction "G1_G1") (pintype "bidirectional"))
    )
    (net (code "448") (name "unconnected-(U20-PadG2)") (class "Default")
      (node (ref "U20") (pin "G2") (pinfunction "G2_G2") (pintype "bidirectional"))
    )
    (net (code "449") (name "unconnected-(U20-SDX_VDD-Pad6)") (class "Default")
      (node (ref "U20") (pin "6") (pinfunction "SDX_VDD_6") (pintype "bidirectional"))
    )
    (net (code "450") (name "unconnected-(U20-TVDAC-Pad166)") (class "Default")
      (node (ref "U20") (pin "166") (pinfunction "TVDAC_166") (pintype "bidirectional"))
    )
    (net (code "451") (name "unconnected-(U20-USB_DM-Pad167)") (class "Default")
      (node (ref "U20") (pin "167") (pinfunction "USB_DM_167") (pintype "bidirectional"))
    )
    (net (code "452") (name "unconnected-(U20-USB_DP-Pad165)") (class "Default")
      (node (ref "U20") (pin "165") (pinfunction "USB_DP_165") (pintype "bidirectional"))
    )
    (net (code "453") (name "unconnected-(U20-VC_TCK-Pad180)") (class "Default")
      (node (ref "U20") (pin "180") (pinfunction "VC_TCK_180") (pintype "bidirectional"))
    )
    (net (code "454") (name "unconnected-(U20-VC_TDI-Pad174)") (class "Default")
      (node (ref "U20") (pin "174") (pinfunction "VC_TDI_174") (pintype "bidirectional"))
    )
    (net (code "455") (name "unconnected-(U20-VC_TDO-Pad178)") (class "Default")
      (node (ref "U20") (pin "178") (pinfunction "VC_TDO_178") (pintype "bidirectional"))
    )
    (net (code "456") (name "unconnected-(U20-VC_TMS-Pad176)") (class "Default")
      (node (ref "U20") (pin "176") (pinfunction "VC_TMS_176") (pintype "bidirectional"))
    )
    (net (code "457") (name "unconnected-(U20-VC_TRST_N-Pad172)") (class "Default")
      (node (ref "U20") (pin "172") (pinfunction "VC_TRST_N_172") (pintype "bidirectional"))
    )
    (net (code "458") (name "unconnected-(U20-VDAC-Pad189)") (class "Default")
      (node (ref "U20") (pin "189") (pinfunction "VDAC_189") (pintype "bidirectional"))
    )
    (net (code "459") (name "unconnected-(U20-VDAC-Pad190)") (class "Default")
      (node (ref "U20") (pin "190") (pinfunction "VDAC_190") (pintype "bidirectional"))
    )
    (net (code "460") (name "unconnected-(U20-VDD_CORE-Pad179)") (class "Default")
      (node (ref "U20") (pin "179") (pinfunction "VDD_CORE_179") (pintype "bidirectional"))
    )
    (net (code "461") (name "unconnected-(U21-CAM0_CN-Pad144)") (class "Default")
      (node (ref "U21") (pin "144") (pinfunction "CAM0_CN_144") (pintype "bidirectional"))
    )
    (net (code "462") (name "unconnected-(U21-CAM0_CP-Pad142)") (class "Default")
      (node (ref "U21") (pin "142") (pinfunction "CAM0_CP_142") (pintype "bidirectional"))
    )
    (net (code "463") (name "unconnected-(U21-CAM0_DN0-Pad138)") (class "Default")
      (node (ref "U21") (pin "138") (pinfunction "CAM0_DN0_138") (pintype "bidirectional"))
    )
    (net (code "464") (name "unconnected-(U21-CAM0_DN1-Pad150)") (class "Default")
      (node (ref "U21") (pin "150") (pinfunction "CAM0_DN1_150") (pintype "bidirectional"))
    )
    (net (code "465") (name "unconnected-(U21-CAM0_DP0-Pad136)") (class "Default")
      (node (ref "U21") (pin "136") (pinfunction "CAM0_DP0_136") (pintype "bidirectional"))
    )
    (net (code "466") (name "unconnected-(U21-CAM0_DP1-Pad148)") (class "Default")
      (node (ref "U21") (pin "148") (pinfunction "CAM0_DP1_148") (pintype "bidirectional"))
    )
    (net (code "467") (name "unconnected-(U21-CAM1_CN-Pad149)") (class "Default")
      (node (ref "U21") (pin "149") (pinfunction "CAM1_CN_149") (pintype "bidirectional"))
    )
    (net (code "468") (name "unconnected-(U21-CAM1_CP-Pad147)") (class "Default")
      (node (ref "U21") (pin "147") (pinfunction "CAM1_CP_147") (pintype "bidirectional"))
    )
    (net (code "469") (name "unconnected-(U21-CAM1_DN0-Pad161)") (class "Default")
      (node (ref "U21") (pin "161") (pinfunction "CAM1_DN0_161") (pintype "bidirectional"))
    )
    (net (code "470") (name "unconnected-(U21-CAM1_DN1-Pad155)") (class "Default")
      (node (ref "U21") (pin "155") (pinfunction "CAM1_DN1_155") (pintype "bidirectional"))
    )
    (net (code "471") (name "unconnected-(U21-CAM1_DN2-Pad143)") (class "Default")
      (node (ref "U21") (pin "143") (pinfunction "CAM1_DN2_143") (pintype "bidirectional"))
    )
    (net (code "472") (name "unconnected-(U21-CAM1_DN3-Pad137)") (class "Default")
      (node (ref "U21") (pin "137") (pinfunction "CAM1_DN3_137") (pintype "bidirectional"))
    )
    (net (code "473") (name "unconnected-(U21-CAM1_DP0-Pad159)") (class "Default")
      (node (ref "U21") (pin "159") (pinfunction "CAM1_DP0_159") (pintype "bidirectional"))
    )
    (net (code "474") (name "unconnected-(U21-CAM1_DP1-Pad153)") (class "Default")
      (node (ref "U21") (pin "153") (pinfunction "CAM1_DP1_153") (pintype "bidirectional"))
    )
    (net (code "475") (name "unconnected-(U21-CAM1_DP2-Pad141)") (class "Default")
      (node (ref "U21") (pin "141") (pinfunction "CAM1_DP2_141") (pintype "bidirectional"))
    )
    (net (code "476") (name "unconnected-(U21-CAM1_DP3-Pad135)") (class "Default")
      (node (ref "U21") (pin "135") (pinfunction "CAM1_DP3_135") (pintype "bidirectional"))
    )
    (net (code "477") (name "unconnected-(U21-DSI0_CN-Pad105)") (class "Default")
      (node (ref "U21") (pin "105") (pinfunction "DSI0_CN_105") (pintype "bidirectional"))
    )
    (net (code "478") (name "unconnected-(U21-DSI0_CP-Pad107)") (class "Default")
      (node (ref "U21") (pin "107") (pinfunction "DSI0_CP_107") (pintype "bidirectional"))
    )
    (net (code "479") (name "unconnected-(U21-DSI0_DN0-Pad99)") (class "Default")
      (node (ref "U21") (pin "99") (pinfunction "DSI0_DN0_99") (pintype "bidirectional"))
    )
    (net (code "480") (name "unconnected-(U21-DSI0_DN1-Pad93)") (class "Default")
      (node (ref "U21") (pin "93") (pinfunction "DSI0_DN1_93") (pintype "bidirectional"))
    )
    (net (code "481") (name "unconnected-(U21-DSI0_DP0-Pad101)") (class "Default")
      (node (ref "U21") (pin "101") (pinfunction "DSI0_DP0_101") (pintype "bidirectional"))
    )
    (net (code "482") (name "unconnected-(U21-DSI0_DP1-Pad95)") (class "Default")
      (node (ref "U21") (pin "95") (pinfunction "DSI0_DP1_95") (pintype "bidirectional"))
    )
    (net (code "483") (name "unconnected-(U21-DSI1_CN-Pad102)") (class "Default")
      (node (ref "U21") (pin "102") (pinfunction "DSI1_CN_102") (pintype "bidirectional"))
    )
    (net (code "484") (name "unconnected-(U21-DSI1_CP-Pad100)") (class "Default")
      (node (ref "U21") (pin "100") (pinfunction "DSI1_CP_100") (pintype "bidirectional"))
    )
    (net (code "485") (name "unconnected-(U21-DSI1_DN0-Pad96)") (class "Default")
      (node (ref "U21") (pin "96") (pinfunction "DSI1_DN0_96") (pintype "bidirectional"))
    )
    (net (code "486") (name "unconnected-(U21-DSI1_DN1-Pad120)") (class "Default")
      (node (ref "U21") (pin "120") (pinfunction "DSI1_DN1_120") (pintype "bidirectional"))
    )
    (net (code "487") (name "unconnected-(U21-DSI1_DN2-Pad114)") (class "Default")
      (node (ref "U21") (pin "114") (pinfunction "DSI1_DN2_114") (pintype "bidirectional"))
    )
    (net (code "488") (name "unconnected-(U21-DSI1_DN3-Pad108)") (class "Default")
      (node (ref "U21") (pin "108") (pinfunction "DSI1_DN3_108") (pintype "bidirectional"))
    )
    (net (code "489") (name "unconnected-(U21-DSI1_DP0-Pad94)") (class "Default")
      (node (ref "U21") (pin "94") (pinfunction "DSI1_DP0_94") (pintype "bidirectional"))
    )
    (net (code "490") (name "unconnected-(U21-DSI1_DP1-Pad118)") (class "Default")
      (node (ref "U21") (pin "118") (pinfunction "DSI1_DP1_118") (pintype "bidirectional"))
    )
    (net (code "491") (name "unconnected-(U21-DSI1_DP2-Pad112)") (class "Default")
      (node (ref "U21") (pin "112") (pinfunction "DSI1_DP2_112") (pintype "bidirectional"))
    )
    (net (code "492") (name "unconnected-(U21-DSI1_DP3-Pad106)") (class "Default")
      (node (ref "U21") (pin "106") (pinfunction "DSI1_DP3_106") (pintype "bidirectional"))
    )
    (net (code "493") (name "unconnected-(U21-GPIO4-Pad15)") (class "Default")
      (node (ref "U21") (pin "15") (pinfunction "GPIO4_15") (pintype "bidirectional"))
    )
    (net (code "494") (name "unconnected-(U21-GPIO5-Pad17)") (class "Default")
      (node (ref "U21") (pin "17") (pinfunction "GPIO5_17") (pintype "bidirectional"))
    )
    (net (code "495") (name "unconnected-(U21-GPIO6-Pad21)") (class "Default")
      (node (ref "U21") (pin "21") (pinfunction "GPIO6_21") (pintype "bidirectional"))
    )
    (net (code "496") (name "unconnected-(U21-GPIO7-Pad23)") (class "Default")
      (node (ref "U21") (pin "23") (pinfunction "GPIO7_23") (pintype "bidirectional"))
    )
    (net (code "497") (name "unconnected-(U21-GPIO12-Pad45)") (class "Default")
      (node (ref "U21") (pin "45") (pinfunction "GPIO12_45") (pintype "bidirectional"))
    )
    (net (code "498") (name "unconnected-(U21-GPIO13-Pad47)") (class "Default")
      (node (ref "U21") (pin "47") (pinfunction "GPIO13_47") (pintype "bidirectional"))
    )
    (net (code "499") (name "unconnected-(U21-GPIO30-Pad34)") (class "Default")
      (node (ref "U21") (pin "34") (pinfunction "GPIO30_34") (pintype "bidirectional"))
    )
    (net (code "500") (name "unconnected-(U21-GPIO31-Pad36)") (class "Default")
      (node (ref "U21") (pin "36") (pinfunction "GPIO31_36") (pintype "bidirectional"))
    )
    (net (code "501") (name "unconnected-(U21-GPIO46_1V8-Pad88)") (class "Default")
      (node (ref "U21") (pin "88") (pinfunction "GPIO46_1V8_88") (pintype "bidirectional"))
    )
    (net (code "502") (name "unconnected-(U21-GPIO47_1V8-Pad90)") (class "Default")
      (node (ref "U21") (pin "90") (pinfunction "GPIO47_1V8_90") (pintype "bidirectional"))
    )
    (net (code "503") (name "unconnected-(U21-HDMI_CEC-Pad171)") (class "Default")
      (node (ref "U21") (pin "171") (pinfunction "HDMI_CEC_171") (pintype "bidirectional"))
    )
    (net (code "504") (name "unconnected-(U21-HDMI_CK_N-Pad111)") (class "Default")
      (node (ref "U21") (pin "111") (pinfunction "HDMI_CK_N_111") (pintype "bidirectional"))
    )
    (net (code "505") (name "unconnected-(U21-HDMI_CK_P-Pad113)") (class "Default")
      (node (ref "U21") (pin "113") (pinfunction "HDMI_CK_P_113") (pintype "bidirectional"))
    )
    (net (code "506") (name "unconnected-(U21-HDMI_D0_N-Pad117)") (class "Default")
      (node (ref "U21") (pin "117") (pinfunction "HDMI_D0_N_117") (pintype "bidirectional"))
    )
    (net (code "507") (name "unconnected-(U21-HDMI_D0_P-Pad119)") (class "Default")
      (node (ref "U21") (pin "119") (pinfunction "HDMI_D0_P_119") (pintype "bidirectional"))
    )
    (net (code "508") (name "unconnected-(U21-HDMI_D1_N-Pad123)") (class "Default")
      (node (ref "U21") (pin "123") (pinfunction "HDMI_D1_N_123") (pintype "bidirectional"))
    )
    (net (code "509") (name "unconnected-(U21-HDMI_D1_P-Pad125)") (class "Default")
      (node (ref "U21") (pin "125") (pinfunction "HDMI_D1_P_125") (pintype "bidirectional"))
    )
    (net (code "510") (name "unconnected-(U21-HDMI_D2_N-Pad129)") (class "Default")
      (node (ref "U21") (pin "129") (pinfunction "HDMI_D2_N_129") (pintype "bidirectional"))
    )
    (net (code "511") (name "unconnected-(U21-HDMI_D2_P-Pad131)") (class "Default")
      (node (ref "U21") (pin "131") (pinfunction "HDMI_D2_P_131") (pintype "bidirectional"))
    )
    (net (code "512") (name "unconnected-(U21-HDMI_SCL-Pad175)") (class "Default")
      (node (ref "U21") (pin "175") (pinfunction "HDMI_SCL_175") (pintype "bidirectional"))
    )
    (net (code "513") (name "unconnected-(U21-HDMI_SDA-Pad173)") (class "Default")
      (node (ref "U21") (pin "173") (pinfunction "HDMI_SDA_173") (pintype "bidirectional"))
    )
    (net (code "514") (name "unconnected-(U21-NC-Pad124)") (class "Default")
      (node (ref "U21") (pin "124") (pinfunction "NC_124") (pintype "bidirectional"))
    )
    (net (code "515") (name "unconnected-(U21-NC-Pad126)") (class "Default")
      (node (ref "U21") (pin "126") (pinfunction "NC_126") (pintype "bidirectional"))
    )
    (net (code "516") (name "unconnected-(U21-NC-Pad128)") (class "Default")
      (node (ref "U21") (pin "128") (pinfunction "NC_128") (pintype "bidirectional"))
    )
    (net (code "517") (name "unconnected-(U21-NC-Pad130)") (class "Default")
      (node (ref "U21") (pin "130") (pinfunction "NC_130") (pintype "bidirectional"))
    )
    (net (code "518") (name "unconnected-(U21-NC-Pad132)") (class "Default")
      (node (ref "U21") (pin "132") (pinfunction "NC_132") (pintype "bidirectional"))
    )
    (net (code "519") (name "unconnected-(U21-NC-Pad154)") (class "Default")
      (node (ref "U21") (pin "154") (pinfunction "NC_154") (pintype "bidirectional"))
    )
    (net (code "520") (name "unconnected-(U21-NC-Pad156)") (class "Default")
      (node (ref "U21") (pin "156") (pinfunction "NC_156") (pintype "bidirectional"))
    )
    (net (code "521") (name "unconnected-(U21-NC-Pad158)") (class "Default")
      (node (ref "U21") (pin "158") (pinfunction "NC_158") (pintype "bidirectional"))
    )
    (net (code "522") (name "unconnected-(U21-NC-Pad160)") (class "Default")
      (node (ref "U21") (pin "160") (pinfunction "NC_160") (pintype "bidirectional"))
    )
    (net (code "523") (name "unconnected-(U21-NC-Pad162)") (class "Default")
      (node (ref "U21") (pin "162") (pinfunction "NC_162") (pintype "bidirectional"))
    )
    (net (code "524") (name "unconnected-(U21-PadG1)") (class "Default")
      (node (ref "U21") (pin "G1") (pinfunction "G1_G1") (pintype "bidirectional"))
    )
    (net (code "525") (name "unconnected-(U21-PadG2)") (class "Default")
      (node (ref "U21") (pin "G2") (pinfunction "G2_G2") (pintype "bidirectional"))
    )
    (net (code "526") (name "unconnected-(U21-SDX_VDD-Pad6)") (class "Default")
      (node (ref "U21") (pin "6") (pinfunction "SDX_VDD_6") (pintype "bidirectional"))
    )
    (net (code "527") (name "unconnected-(U21-TVDAC-Pad166)") (class "Default")
      (node (ref "U21") (pin "166") (pinfunction "TVDAC_166") (pintype "bidirectional"))
    )
    (net (code "528") (name "unconnected-(U21-USB_DM-Pad167)") (class "Default")
      (node (ref "U21") (pin "167") (pinfunction "USB_DM_167") (pintype "bidirectional"))
    )
    (net (code "529") (name "unconnected-(U21-USB_DP-Pad165)") (class "Default")
      (node (ref "U21") (pin "165") (pinfunction "USB_DP_165") (pintype "bidirectional"))
    )
    (net (code "530") (name "unconnected-(U21-VC_TCK-Pad180)") (class "Default")
      (node (ref "U21") (pin "180") (pinfunction "VC_TCK_180") (pintype "bidirectional"))
    )
    (net (code "531") (name "unconnected-(U21-VC_TDI-Pad174)") (class "Default")
      (node (ref "U21") (pin "174") (pinfunction "VC_TDI_174") (pintype "bidirectional"))
    )
    (net (code "532") (name "unconnected-(U21-VC_TDO-Pad178)") (class "Default")
      (node (ref "U21") (pin "178") (pinfunction "VC_TDO_178") (pintype "bidirectional"))
    )
    (net (code "533") (name "unconnected-(U21-VC_TMS-Pad176)") (class "Default")
      (node (ref "U21") (pin "176") (pinfunction "VC_TMS_176") (pintype "bidirectional"))
    )
    (net (code "534") (name "unconnected-(U21-VC_TRST_N-Pad172)") (class "Default")
      (node (ref "U21") (pin "172") (pinfunction "VC_TRST_N_172") (pintype "bidirectional"))
    )
    (net (code "535") (name "unconnected-(U21-VDAC-Pad189)") (class "Default")
      (node (ref "U21") (pin "189") (pinfunction "VDAC_189") (pintype "bidirectional"))
    )
    (net (code "536") (name "unconnected-(U21-VDAC-Pad190)") (class "Default")
      (node (ref "U21") (pin "190") (pinfunction "VDAC_190") (pintype "bidirectional"))
    )
    (net (code "537") (name "unconnected-(U21-VDD_CORE-Pad179)") (class "Default")
      (node (ref "U21") (pin "179") (pinfunction "VDD_CORE_179") (pintype "bidirectional"))
    )
    (net (code "538") (name "unconnected-(U22-NC-Pad1)") (class "Default")
      (node (ref "U22") (pin "1") (pinfunction "NC_1") (pintype "bidirectional"))
    )
    (net (code "539") (name "unconnected-(U23-NC-Pad1)") (class "Default")
      (node (ref "U23") (pin "1") (pinfunction "NC_1") (pintype "bidirectional"))
    )
    (net (code "540") (name "unconnected-(U24-NC-Pad1)") (class "Default")
      (node (ref "U24") (pin "1") (pinfunction "NC_1") (pintype "bidirectional"))
    )
    (net (code "541") (name "unconnected-(U25-NC-Pad1)") (class "Default")
      (node (ref "U25") (pin "1") (pinfunction "NC_1") (pintype "bidirectional"))
    )
    (net (code "542") (name "unconnected-(X1-DETECT+-Pad12)") (class "Default")
      (node (ref "X1") (pin "12") (pinfunction "DETECT+_12") (pintype "bidirectional"))
    )
    (net (code "543") (name "unconnected-(X1-DETECT--Pad11)") (class "Default")
      (node (ref "X1") (pin "11") (pinfunction "DETECT-_11") (pintype "bidirectional"))
    )
    (net (code "544") (name "unconnected-(X2-DETECT+-Pad12)") (class "Default")
      (node (ref "X2") (pin "12") (pinfunction "DETECT+_12") (pintype "bidirectional"))
    )
    (net (code "545") (name "unconnected-(X2-DETECT--Pad11)") (class "Default")
      (node (ref "X2") (pin "11") (pinfunction "DETECT-_11") (pintype "bidirectional"))
    )
    (net (code "546") (name "unconnected-(X5-DETECT+-Pad12)") (class "Default")
      (node (ref "X5") (pin "12") (pinfunction "DETECT+_12") (pintype "bidirectional"))
    )
    (net (code "547") (name "unconnected-(X5-DETECT--Pad11)") (class "Default")
      (node (ref "X5") (pin "11") (pinfunction "DETECT-_11") (pintype "bidirectional"))
    )
    (net (code "548") (name "unconnected-(X6-DETECT+-Pad12)") (class "Default")
      (node (ref "X6") (pin "12") (pinfunction "DETECT+_12") (pintype "bidirectional"))
    )
    (net (code "549") (name "unconnected-(X6-DETECT--Pad11)") (class "Default")
      (node (ref "X6") (pin "11") (pinfunction "DETECT-_11") (pintype "bidirectional"))
    )
  )
)
